# 1_5KW.net
KiCad netlist of a schematic drawn in Altium Designer
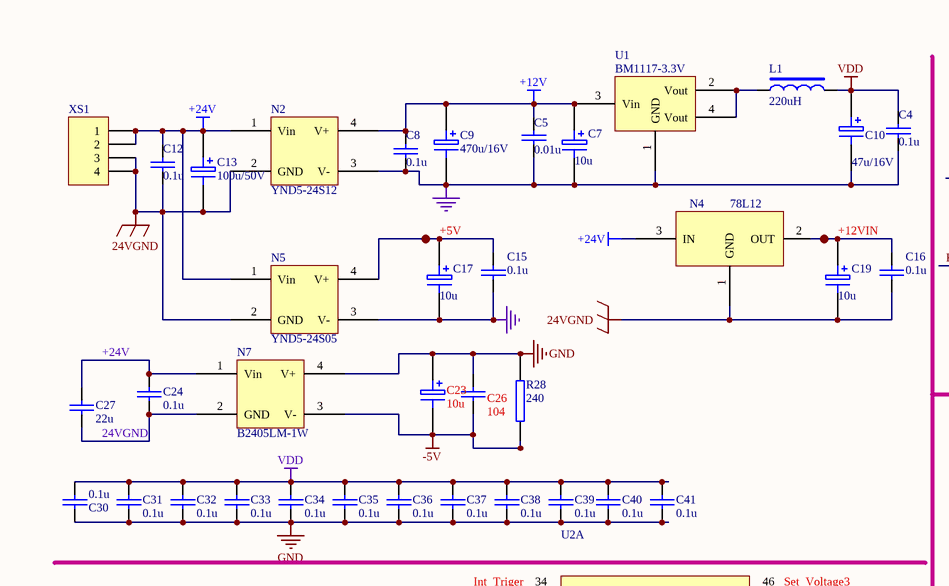
[diagram p0: 1.5KW总控制板.SchDoc, top left]
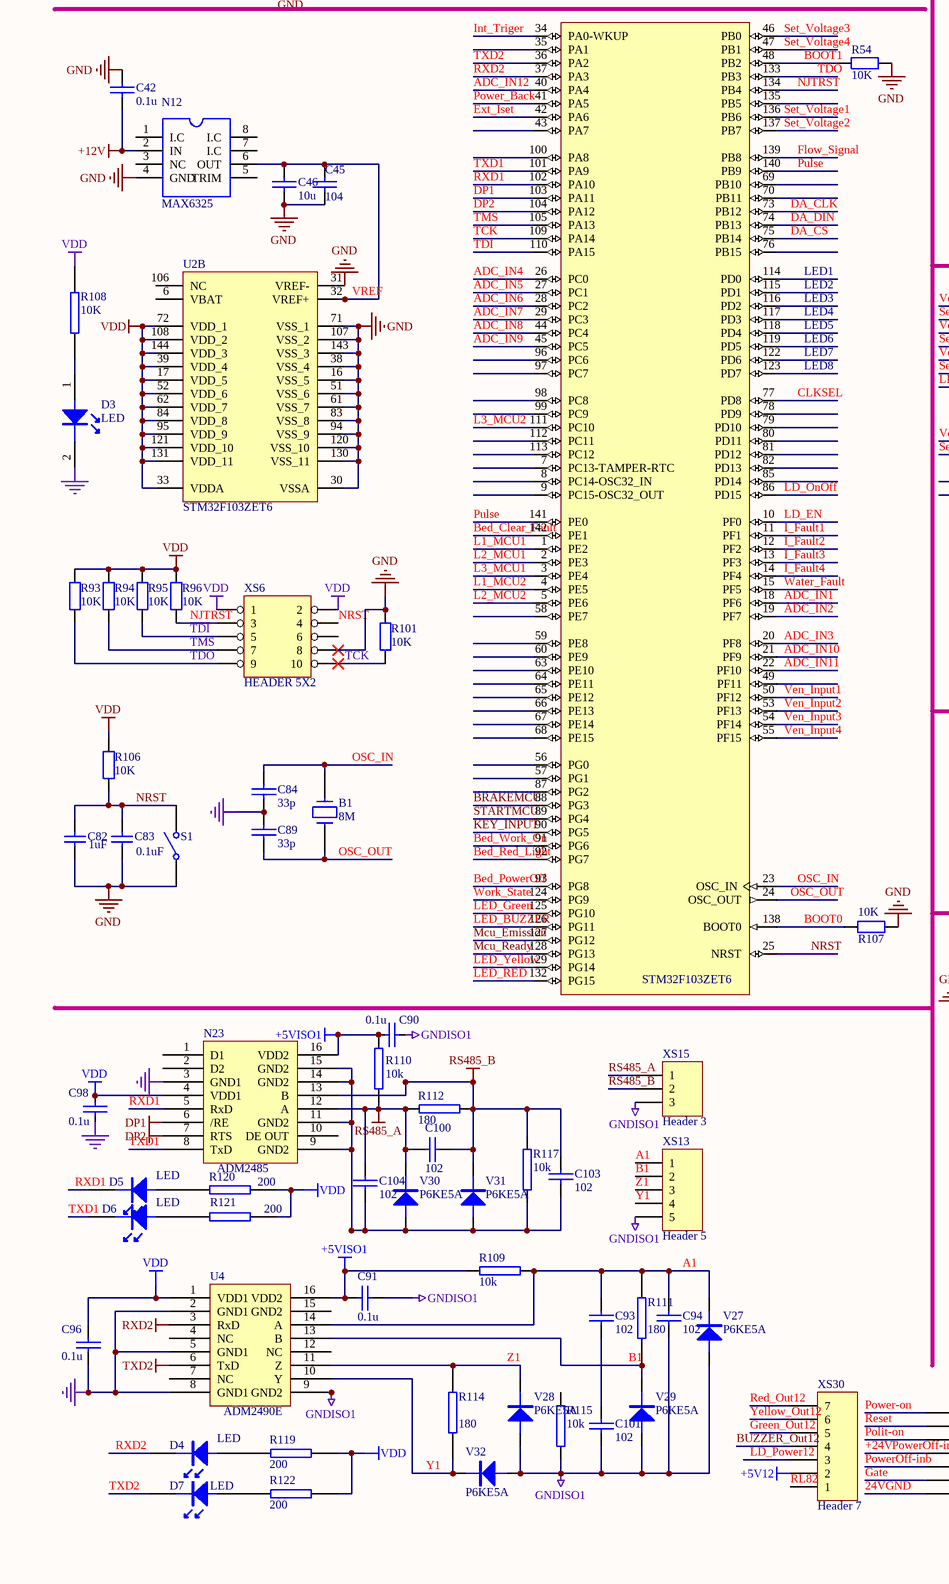
[diagram p1: 1.5KW总控制板.SchDoc, bottom left]
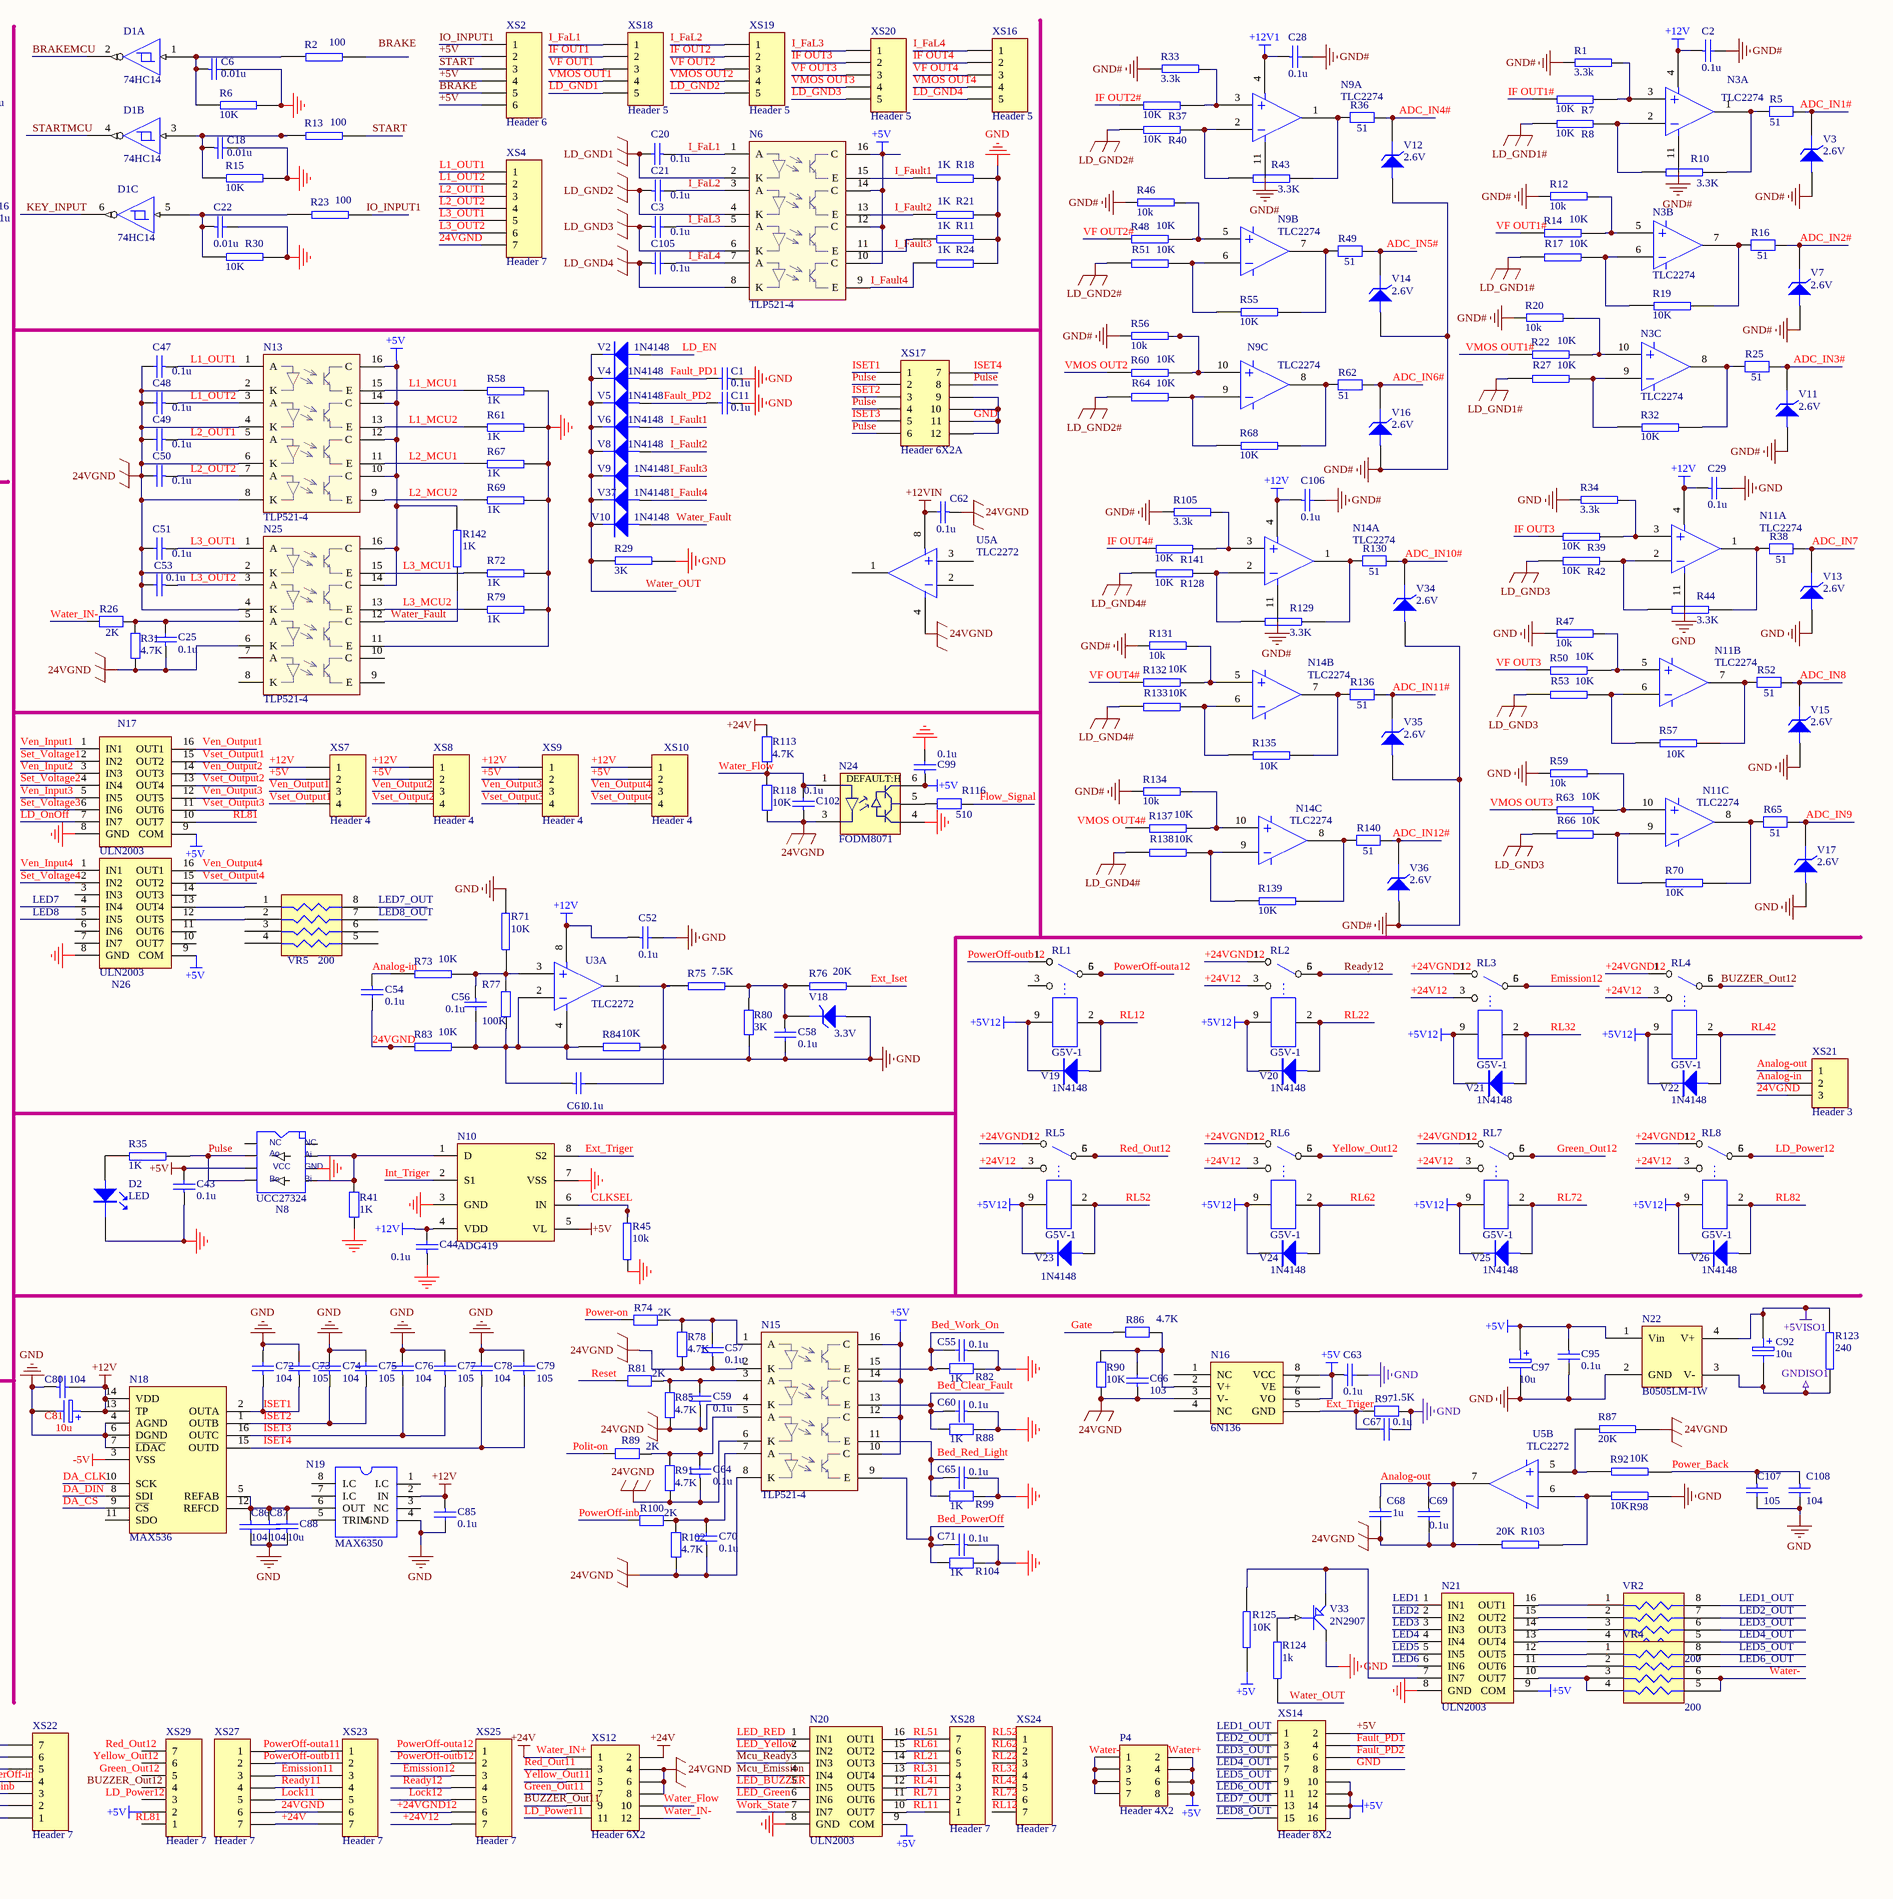
[diagram p2: 1.5KW总控制板.SchDoc, bottom right]

(export (version "E")
  (design (tool "Eeschema 10.0.6"))
  (components
    (comp (ref "B1")
      (value "8M")
      (footprint "CRY_SMB")
      (description "Crystal")
      (libsource (lib "*") (part "CRYSTAL"))
    )
    (comp (ref "C1") (value "0.1u") (footprint "0805") (libsource (lib "") (part "CAP_1")))
    (comp (ref "C2")
      (value "0.1u")
      (footprint "0805")
      (description "Capacitor")
      (libsource (lib "*") (part "CAP"))
    )
    (comp (ref "C3")
      (value "0.1u")
      (footprint "0805")
      (description "Capacitor")
      (libsource (lib "*") (part "CAP"))
    )
    (comp (ref "C4")
      (value "0.1u")
      (footprint "0805")
      (description "Capacitor")
      (libsource (lib "*") (part "CAP"))
    )
    (comp (ref "C5")
      (value "0.01u")
      (footprint "0805")
      (description "Capacitor")
      (libsource (lib "*") (part "CAP"))
    )
    (comp (ref "C6")
      (value "0.01u")
      (footprint "0805")
      (description "Capacitor")
      (libsource (lib "*") (part "CAP"))
    )
    (comp (ref "C7")
      (value "10u")
      (footprint "1206")
      (description "Electrolytic Capacitor")
      (libsource (lib "*") (part "ELECTRO1"))
    )
    (comp (ref "C8")
      (value "0.1u")
      (footprint "0805")
      (description "Capacitor")
      (libsource (lib "*") (part "CAP"))
    )
    (comp (ref "C9")
      (value "470u/16V")
      (footprint "3008")
      (description "Electrolytic Capacitor")
      (libsource (lib "*") (part "ELECTRO1"))
    )
    (comp (ref "C10")
      (value "47u/16V")
      (footprint "1206")
      (description "Electrolytic Capacitor")
      (libsource (lib "*") (part "ELECTRO1"))
    )
    (comp (ref "C11") (value "0.1u") (footprint "0805") (libsource (lib "") (part "CAP_1")))
    (comp (ref "C12")
      (value "0.1u")
      (footprint "0805")
      (description "Capacitor")
      (libsource (lib "*") (part "CAP"))
    )
    (comp (ref "C13")
      (value "100u/50V")
      (footprint "CD5-8")
      (description "Electrolytic Capacitor")
      (libsource (lib "*") (part "ELECTRO1"))
    )
    (comp (ref "C15") (value "0.1u") (footprint "0805") (libsource (lib "") (part "CAP_1")))
    (comp (ref "C16") (value "0.1u") (footprint "0805") (libsource (lib "") (part "CAP_1")))
    (comp (ref "C17")
      (value "10u")
      (footprint "1206")
      (description "Electrolytic Capacitor")
      (libsource (lib "*") (part "ELECTRO1"))
    )
    (comp (ref "C18")
      (value "0.01u")
      (footprint "0805")
      (description "Capacitor")
      (libsource (lib "*") (part "CAP"))
    )
    (comp (ref "C19")
      (value "10u")
      (footprint "1206")
      (description "Electrolytic Capacitor")
      (libsource (lib "*") (part "ELECTRO1"))
    )
    (comp (ref "C20")
      (value "0.1u")
      (footprint "0805")
      (description "Capacitor")
      (libsource (lib "*") (part "CAP"))
    )
    (comp (ref "C21")
      (value "0.1u")
      (footprint "0805")
      (description "Capacitor")
      (libsource (lib "*") (part "CAP"))
    )
    (comp (ref "C22")
      (value "0.01u")
      (footprint "0805")
      (description "Capacitor")
      (libsource (lib "*") (part "CAP"))
    )
    (comp (ref "C23")
      (value "10u")
      (footprint "1206")
      (description "Electrolytic Capacitor")
      (libsource (lib "*") (part "ELECTRO1"))
    )
    (comp (ref "C24")
      (value "0.1u")
      (footprint "0805")
      (description "Capacitor")
      (libsource (lib "*") (part "CAP"))
    )
    (comp (ref "C25") (value "0.1u") (footprint "0805") (libsource (lib "") (part "CAP_1")))
    (comp (ref "C26")
      (value "104")
      (footprint "0805")
      (description "Capacitor")
      (libsource (lib "*") (part "CAP"))
    )
    (comp (ref "C27")
      (value "22u")
      (footprint "1206")
      (description "Capacitor")
      (libsource (lib "*") (part "CAP"))
    )
    (comp (ref "C28")
      (value "0.1u")
      (footprint "0805")
      (description "Capacitor")
      (libsource (lib "*") (part "CAP"))
    )
    (comp (ref "C29")
      (value "0.1u")
      (footprint "0805")
      (description "Capacitor")
      (libsource (lib "*") (part "CAP"))
    )
    (comp (ref "C30")
      (value "0.1u")
      (footprint "0805")
      (description "Capacitor")
      (libsource (lib "*") (part "CAP"))
    )
    (comp (ref "C31")
      (value "0.1u")
      (footprint "0805")
      (description "Capacitor")
      (libsource (lib "*") (part "CAP"))
    )
    (comp (ref "C32")
      (value "0.1u")
      (footprint "0805")
      (description "Capacitor")
      (libsource (lib "*") (part "CAP"))
    )
    (comp (ref "C33")
      (value "0.1u")
      (footprint "0805")
      (description "Capacitor")
      (libsource (lib "*") (part "CAP"))
    )
    (comp (ref "C34")
      (value "0.1u")
      (footprint "0805")
      (description "Capacitor")
      (libsource (lib "*") (part "CAP"))
    )
    (comp (ref "C35")
      (value "0.1u")
      (footprint "0805")
      (description "Capacitor")
      (libsource (lib "*") (part "CAP"))
    )
    (comp (ref "C36")
      (value "0.1u")
      (footprint "0805")
      (description "Capacitor")
      (libsource (lib "*") (part "CAP"))
    )
    (comp (ref "C37")
      (value "0.1u")
      (footprint "0805")
      (description "Capacitor")
      (libsource (lib "*") (part "CAP"))
    )
    (comp (ref "C38")
      (value "0.1u")
      (footprint "0805")
      (description "Capacitor")
      (libsource (lib "*") (part "CAP"))
    )
    (comp (ref "C39")
      (value "0.1u")
      (footprint "0805")
      (description "Capacitor")
      (libsource (lib "*") (part "CAP"))
    )
    (comp (ref "C40")
      (value "0.1u")
      (footprint "0805")
      (description "Capacitor")
      (libsource (lib "*") (part "CAP"))
    )
    (comp (ref "C41")
      (value "0.1u")
      (footprint "0805")
      (description "Capacitor")
      (libsource (lib "*") (part "CAP"))
    )
    (comp (ref "C42") (value "0.1u") (footprint "0805") (libsource (lib "") (part "CAP_1")))
    (comp (ref "C43") (value "0.1u") (footprint "0805") (libsource (lib "") (part "CAP_1")))
    (comp (ref "C44") (value "0.1u") (footprint "0805") (libsource (lib "") (part "CAP_1")))
    (comp (ref "C45") (value "104") (footprint "0805") (libsource (lib "THT") (part "CAP")))
    (comp (ref "C46") (value "10u") (footprint "0805") (libsource (lib "") (part "CAP_1")))
    (comp (ref "C47")
      (value "0.1u")
      (footprint "0805")
      (description "Capacitor")
      (libsource (lib "*") (part "CAP"))
    )
    (comp (ref "C48")
      (value "0.1u")
      (footprint "0805")
      (description "Capacitor")
      (libsource (lib "*") (part "CAP"))
    )
    (comp (ref "C49")
      (value "0.1u")
      (footprint "0805")
      (description "Capacitor")
      (libsource (lib "*") (part "CAP"))
    )
    (comp (ref "C50")
      (value "0.1u")
      (footprint "0805")
      (description "Capacitor")
      (libsource (lib "*") (part "CAP"))
    )
    (comp (ref "C51")
      (value "0.1u")
      (footprint "0805")
      (description "Capacitor")
      (libsource (lib "*") (part "CAP"))
    )
    (comp (ref "C52")
      (value "0.1u")
      (footprint "0805")
      (description "Capacitor")
      (libsource (lib "*") (part "CAP"))
    )
    (comp (ref "C53")
      (value "0.1u")
      (footprint "0805")
      (description "Capacitor")
      (libsource (lib "*") (part "CAP"))
    )
    (comp (ref "C54")
      (value "0.1u")
      (footprint "0805")
      (description "Capacitor")
      (libsource (lib "*") (part "CAP"))
    )
    (comp (ref "C55") (value "0.1u") (footprint "0805") (libsource (lib "") (part "CAP_1")))
    (comp (ref "C56")
      (value "0.1u")
      (footprint "0805")
      (description "Capacitor")
      (libsource (lib "*") (part "CAP"))
    )
    (comp (ref "C57") (value "0.1u") (footprint "0805") (libsource (lib "") (part "CAP_1")))
    (comp (ref "C58")
      (value "0.1u")
      (footprint "0805")
      (description "Capacitor")
      (libsource (lib "*") (part "CAP"))
    )
    (comp (ref "C59") (value "0.1u") (footprint "0805") (libsource (lib "") (part "CAP_1")))
    (comp (ref "C60") (value "0.1u") (footprint "0805") (libsource (lib "") (part "CAP_1")))
    (comp (ref "C61")
      (value "0.1u")
      (footprint "0805")
      (description "Capacitor")
      (libsource (lib "*") (part "CAP"))
    )
    (comp (ref "C62")
      (value "0.1u")
      (footprint "0805")
      (description "Capacitor")
      (libsource (lib "*") (part "CAP"))
    )
    (comp (ref "C63")
      (value "0.1u")
      (footprint "0805")
      (description "Capacitor")
      (libsource (lib "*") (part "CAP"))
    )
    (comp (ref "C64") (value "0.1u") (footprint "0805") (libsource (lib "") (part "CAP_1")))
    (comp (ref "C65") (value "0.1u") (footprint "0805") (libsource (lib "") (part "CAP_1")))
    (comp (ref "C66") (value "103") (footprint "0805") (libsource (lib "") (part "CAP_1")))
    (comp (ref "C67") (value "0.1u") (footprint "0805") (libsource (lib "") (part "CAP_1")))
    (comp (ref "C68")
      (value "1u")
      (footprint "0805")
      (description "Capacitor")
      (libsource (lib "*") (part "CAP"))
    )
    (comp (ref "C69")
      (value "0.1u")
      (footprint "0805")
      (description "Capacitor")
      (libsource (lib "*") (part "CAP"))
    )
    (comp (ref "C70") (value "0.1u") (footprint "0805") (libsource (lib "") (part "CAP_1")))
    (comp (ref "C71") (value "0.1u") (footprint "0805") (libsource (lib "") (part "CAP_1")))
    (comp (ref "C72") (value "104") (footprint "0805") (libsource (lib "THT") (part "CAP")))
    (comp (ref "C73") (value "105") (footprint "0805") (libsource (lib "THT") (part "CAP")))
    (comp (ref "C74") (value "104") (footprint "0805") (libsource (lib "THT") (part "CAP")))
    (comp (ref "C75") (value "105") (footprint "0805") (libsource (lib "THT") (part "CAP")))
    (comp (ref "C76") (value "104") (footprint "0805") (libsource (lib "THT") (part "CAP")))
    (comp (ref "C77") (value "105") (footprint "0805") (libsource (lib "THT") (part "CAP")))
    (comp (ref "C78") (value "104") (footprint "0805") (libsource (lib "THT") (part "CAP")))
    (comp (ref "C79") (value "105") (footprint "0805") (libsource (lib "THT") (part "CAP")))
    (comp (ref "C80") (value "104") (footprint "0805") (libsource (lib "THT") (part "CAP")))
    (comp (ref "C81")
      (value "10u")
      (footprint "1206")
      (description "Electrolytic Capacitor")
      (libsource (lib "*") (part "ELECTRO1"))
    )
    (comp (ref "C82")
      (value "1uF")
      (footprint "0805")
      (description "Capacitor")
      (fields (field (name "PUBLISHER") "Altium Limited"))
      (libsource (lib "Miscellaneous Devices") (part "Cap"))
    )
    (comp (ref "C83")
      (value "0.1uF")
      (footprint "0805")
      (description "Capacitor")
      (fields (field (name "PUBLISHER") "Altium Limited"))
      (libsource (lib "Miscellaneous Devices") (part "Cap"))
    )
    (comp (ref "C84")
      (value "33p")
      (footprint "0805")
      (description "Capacitor")
      (libsource (lib "*") (part "CAP"))
    )
    (comp (ref "C85") (value "0.1u") (footprint "0805") (libsource (lib "") (part "CAP_1")))
    (comp (ref "C86") (value "104") (footprint "0805") (libsource (lib "THT") (part "CAP")))
    (comp (ref "C87") (value "104") (footprint "0805") (libsource (lib "THT") (part "CAP")))
    (comp (ref "C88") (value "10u") (footprint "0805") (libsource (lib "") (part "CAP_1")))
    (comp (ref "C89")
      (value "33p")
      (footprint "0805")
      (description "Capacitor")
      (libsource (lib "*") (part "CAP"))
    )
    (comp (ref "C90") (value "0.1u") (footprint "0805") (libsource (lib "") (part "CAP_2")))
    (comp (ref "C91")
      (value "0.1u")
      (footprint "0805")
      (description "Capacitor")
      (libsource (lib "*") (part "CAP"))
    )
    (comp (ref "C92")
      (value "10u")
      (footprint "1206")
      (description "Electrolytic Capacitor")
      (libsource (lib "*") (part "ELECTRO1"))
    )
    (comp (ref "C93")
      (value "102")
      (footprint "0805")
      (description "Capacitor")
      (libsource (lib "*") (part "CAP"))
    )
    (comp (ref "C94")
      (value "102")
      (footprint "0805")
      (description "Capacitor")
      (libsource (lib "*") (part "CAP"))
    )
    (comp (ref "C95")
      (value "0.1u")
      (footprint "0805")
      (description "Capacitor")
      (libsource (lib "*") (part "CAP"))
    )
    (comp (ref "C96")
      (value "0.1u")
      (footprint "0805")
      (description "Capacitor")
      (libsource (lib "*") (part "CAP"))
    )
    (comp (ref "C97")
      (value "10u")
      (footprint "1206")
      (description "Electrolytic Capacitor")
      (libsource (lib "*") (part "ELECTRO1"))
    )
    (comp (ref "C98") (value "0.1u") (footprint "0805") (libsource (lib "") (part "CAP_2")))
    (comp (ref "C99") (value "0.1u") (footprint "0805") (libsource (lib "") (part "CAP_1")))
    (comp (ref "C100")
      (value "102")
      (footprint "0805")
      (description "Capacitor")
      (libsource (lib "*") (part "CAP"))
    )
    (comp (ref "C101")
      (value "102")
      (footprint "0805")
      (description "Capacitor")
      (libsource (lib "*") (part "CAP"))
    )
    (comp (ref "C102") (value "0.1u") (footprint "0805") (libsource (lib "") (part "CAP_1")))
    (comp (ref "C103")
      (value "102")
      (footprint "0805")
      (description "Capacitor")
      (libsource (lib "*") (part "CAP"))
    )
    (comp (ref "C104")
      (value "102")
      (footprint "0805")
      (description "Capacitor")
      (libsource (lib "*") (part "CAP"))
    )
    (comp (ref "C105")
      (value "0.1u")
      (footprint "0805")
      (description "Capacitor")
      (libsource (lib "*") (part "CAP"))
    )
    (comp (ref "C106")
      (value "0.1u")
      (footprint "0805")
      (description "Capacitor")
      (libsource (lib "*") (part "CAP"))
    )
    (comp (ref "C107") (value "105") (footprint "0805") (libsource (lib "THT") (part "CAP")))
    (comp (ref "C108") (value "104") (footprint "0805") (libsource (lib "THT") (part "CAP")))
    (comp (ref "D1") (value "74HC14") (footprint "SO-14") (libsource (lib "*") (part "4584")))
    (comp (ref "D2") (value "LED") (footprint "1206A") (libsource (lib "*") (part "LED")))
    (comp (ref "D3") (value "LED") (footprint "1206A") (libsource (lib "") (part "LED_1")))
    (comp (ref "D4") (value "LED") (footprint "1206A") (libsource (lib "*") (part "LED")))
    (comp (ref "D5") (value "LED") (footprint "1206A") (libsource (lib "*") (part "LED")))
    (comp (ref "D6") (value "LED") (footprint "1206A") (libsource (lib "*") (part "LED")))
    (comp (ref "D7") (value "LED") (footprint "1206A") (libsource (lib "*") (part "LED")))
    (comp (ref "L1") (value "220uH") (footprint "1812") (libsource (lib "*") (part "L")))
    (comp (ref "N2") (value "YND5-24S12") (footprint "YND5") (libsource (lib "*") (part "B0505LM")))
    (comp (ref "N3") (value "TLC2274") (footprint "SO-14") (libsource (lib "*") (part "LM124")))
    (comp (ref "N4") (value "78L12") (footprint "TO-92_2") (libsource (lib "*") (part "VOL")))
    (comp (ref "N5") (value "YND5-24S05") (footprint "YND5") (libsource (lib "*") (part "B0505LM")))
    (comp (ref "N6")
      (value "TLP521-4")
      (footprint "ILEAD-16")
      (libsource (lib "work_ruilei") (part "TLP521-4"))
    )
    (comp (ref "N7") (value "B2405LM-1W") (footprint "B0505LM") (libsource (lib "*") (part "B0505LM")))
    (comp (ref "N8") (value "UCC27324") (footprint "SO-8") (libsource (lib "框图2") (part "UCC27324")))
    (comp (ref "N9") (value "TLC2274") (footprint "SO-14") (libsource (lib "*") (part "LM124")))
    (comp (ref "N10") (value "ADG419") (footprint "SO-8") (libsource (lib "40hz") (part "ADG419")))
    (comp (ref "N11") (value "TLC2274") (footprint "SO-14") (libsource (lib "*") (part "LM124")))
    (comp (ref "N12") (value "MAX6325") (footprint "SO-8") (libsource (lib "") (part "MAX6341_1")))
    (comp (ref "N13")
      (value "TLP521-4")
      (footprint "ILEAD-16")
      (libsource (lib "work_ruilei") (part "TLP521-4"))
    )
    (comp (ref "N14") (value "TLC2274") (footprint "SO-14") (libsource (lib "*") (part "LM124")))
    (comp (ref "N15")
      (value "TLP521-4")
      (footprint "ILEAD-16")
      (libsource (lib "work_ruilei") (part "TLP521-4"))
    )
    (comp (ref "N16") (value "6N136") (footprint "ILEAD-8") (libsource (lib "*") (part "HCPL2601")))
    (comp (ref "N17")
      (value "ULN2003")
      (footprint "SOIC127P600-16N")
      (libsource (lib "work_ruilei") (part "ULN2003A"))
    )
    (comp (ref "N18") (value "MAX536") (footprint "SOIC-16") (libsource (lib "work_ruilei") (part "MAX536")))
    (comp (ref "N19") (value "MAX6350") (footprint "SO-8") (libsource (lib "TH2") (part "MAX6341")))
    (comp (ref "N20")
      (value "ULN2003")
      (footprint "SOIC127P600-16N")
      (libsource (lib "work_ruilei") (part "ULN2003A"))
    )
    (comp (ref "N21")
      (value "ULN2003")
      (footprint "SOIC127P600-16N")
      (libsource (lib "work_ruilei") (part "ULN2003A"))
    )
    (comp (ref "N22") (value "B0505LM-1W") (footprint "B0505LM") (libsource (lib "*") (part "B0505LM")))
    (comp (ref "N23") (value "ADM2485") (footprint "SOIC-16") (libsource (lib "C8051F021") (part "ADM2485")))
    (comp (ref "N24") (value "FODM8071") (footprint "SO-8") (libsource (lib "work_ruilei") (part "FODM8071")))
    (comp (ref "N25")
      (value "TLP521-4")
      (footprint "ILEAD-16")
      (libsource (lib "work_ruilei") (part "TLP521-4"))
    )
    (comp (ref "N26")
      (value "ULN2003")
      (footprint "SOIC127P600-16N")
      (libsource (lib "work_ruilei") (part "ULN2003A"))
    )
    (comp (ref "P4")
      (value "Header 4X2")
      (footprint "HDR2X4")
      (description "Header, 4-Pin, Dual row")
      (fields (field (name "PUBLISHER") "Altium Limited"))
      (libsource (lib "Miscellaneous Connectors") (part "Header 4X2"))
    )
    (comp (ref "R1") (value "3.3k") (footprint "0805") (libsource (lib "") (part "R_1")))
    (comp (ref "R2") (value "100") (footprint "0805") (libsource (lib "*") (part "RES2")))
    (comp (ref "R5")
      (value "51")
      (footprint "0805")
      (description "Resistor")
      (fields (field (name "PUBLISHER") "Altium Limited"))
      (libsource (lib "Miscellaneous Devices") (part "Res2"))
    )
    (comp (ref "R6") (value "10K") (footprint "0805") (libsource (lib "*") (part "RES2")))
    (comp (ref "R7") (value "10K") (footprint "0805") (libsource (lib "*") (part "RES2")))
    (comp (ref "R8") (value "10K") (footprint "0805") (libsource (lib "*") (part "RES2")))
    (comp (ref "R10") (value "3.3K") (footprint "0805") (libsource (lib "*") (part "RES2")))
    (comp (ref "R11") (value "1K") (footprint "0805") (libsource (lib "*") (part "RES2")))
    (comp (ref "R12") (value "10k") (footprint "0805") (libsource (lib "") (part "R_1")))
    (comp (ref "R13") (value "100") (footprint "0805") (libsource (lib "*") (part "RES2")))
    (comp (ref "R14") (value "10K") (footprint "0805") (libsource (lib "*") (part "RES2")))
    (comp (ref "R15") (value "10K") (footprint "0805") (libsource (lib "*") (part "RES2")))
    (comp (ref "R16")
      (value "51")
      (footprint "0805")
      (description "Resistor")
      (fields (field (name "PUBLISHER") "Altium Limited"))
      (libsource (lib "Miscellaneous Devices") (part "Res2"))
    )
    (comp (ref "R17") (value "10K") (footprint "0805") (libsource (lib "*") (part "RES2")))
    (comp (ref "R18") (value "1K") (footprint "0805") (libsource (lib "*") (part "RES2")))
    (comp (ref "R19") (value "10K") (footprint "0805") (libsource (lib "*") (part "RES2")))
    (comp (ref "R20") (value "10k") (footprint "0805") (libsource (lib "") (part "R_1")))
    (comp (ref "R21") (value "1K") (footprint "0805") (libsource (lib "*") (part "RES2")))
    (comp (ref "R22") (value "10K") (footprint "0805") (libsource (lib "*") (part "RES2")))
    (comp (ref "R23") (value "100") (footprint "0805") (libsource (lib "*") (part "RES2")))
    (comp (ref "R24") (value "1K") (footprint "0805") (libsource (lib "*") (part "RES2")))
    (comp (ref "R25")
      (value "51")
      (footprint "0805")
      (description "Resistor")
      (fields (field (name "PUBLISHER") "Altium Limited"))
      (libsource (lib "Miscellaneous Devices") (part "Res2"))
    )
    (comp (ref "R26")
      (value "2K")
      (footprint "0805")
      (description "Resistor")
      (fields (field (name "PUBLISHER") "Altium Limited"))
      (libsource (lib "Miscellaneous Devices") (part "Res2"))
    )
    (comp (ref "R27") (value "10K") (footprint "0805") (libsource (lib "*") (part "RES2")))
    (comp (ref "R28") (value "240") (footprint "1206") (libsource (lib "*") (part "RES2")))
    (comp (ref "R29") (value "3K") (footprint "0805") (libsource (lib "*") (part "RES2")))
    (comp (ref "R30") (value "10K") (footprint "0805") (libsource (lib "*") (part "RES2")))
    (comp (ref "R31")
      (value "4.7K")
      (footprint "0805")
      (description "Resistor")
      (fields (field (name "PUBLISHER") "Altium Limited"))
      (libsource (lib "") (part "Res2_2"))
    )
    (comp (ref "R32") (value "10K") (footprint "0805") (libsource (lib "*") (part "RES2")))
    (comp (ref "R33") (value "3.3k") (footprint "0805") (libsource (lib "") (part "R_1")))
    (comp (ref "R34") (value "3.3k") (footprint "0805") (libsource (lib "") (part "R_1")))
    (comp (ref "R35") (value "1K") (footprint "0805") (libsource (lib "*") (part "RES2")))
    (comp (ref "R36")
      (value "51")
      (footprint "0805")
      (description "Resistor")
      (fields (field (name "PUBLISHER") "Altium Limited"))
      (libsource (lib "Miscellaneous Devices") (part "Res2"))
    )
    (comp (ref "R37") (value "10K") (footprint "0805") (libsource (lib "*") (part "RES2")))
    (comp (ref "R38")
      (value "51")
      (footprint "0805")
      (description "Resistor")
      (fields (field (name "PUBLISHER") "Altium Limited"))
      (libsource (lib "Miscellaneous Devices") (part "Res2"))
    )
    (comp (ref "R39") (value "10K") (footprint "0805") (libsource (lib "*") (part "RES2")))
    (comp (ref "R40") (value "10K") (footprint "0805") (libsource (lib "*") (part "RES2")))
    (comp (ref "R41")
      (value "1K")
      (footprint "0805")
      (description "Resistor")
      (fields (field (name "PUBLISHER") "Altium Limited"))
      (libsource (lib "") (part "Res2_2"))
    )
    (comp (ref "R42") (value "10K") (footprint "0805") (libsource (lib "*") (part "RES2")))
    (comp (ref "R43") (value "3.3K") (footprint "0805") (libsource (lib "*") (part "RES2")))
    (comp (ref "R44") (value "3.3K") (footprint "0805") (libsource (lib "*") (part "RES2")))
    (comp (ref "R45") (value "10k") (footprint "0805") (libsource (lib "*") (part "R")))
    (comp (ref "R46") (value "10k") (footprint "0805") (libsource (lib "") (part "R_1")))
    (comp (ref "R47") (value "10k") (footprint "0805") (libsource (lib "") (part "R_1")))
    (comp (ref "R48") (value "10K") (footprint "0805") (libsource (lib "*") (part "RES2")))
    (comp (ref "R49")
      (value "51")
      (footprint "0805")
      (description "Resistor")
      (fields (field (name "PUBLISHER") "Altium Limited"))
      (libsource (lib "Miscellaneous Devices") (part "Res2"))
    )
    (comp (ref "R50") (value "10K") (footprint "0805") (libsource (lib "*") (part "RES2")))
    (comp (ref "R51") (value "10K") (footprint "0805") (libsource (lib "*") (part "RES2")))
    (comp (ref "R52")
      (value "51")
      (footprint "0805")
      (description "Resistor")
      (fields (field (name "PUBLISHER") "Altium Limited"))
      (libsource (lib "Miscellaneous Devices") (part "Res2"))
    )
    (comp (ref "R53") (value "10K") (footprint "0805") (libsource (lib "*") (part "RES2")))
    (comp (ref "R54")
      (value "10K")
      (footprint "0805")
      (description "Resistor")
      (fields (field (name "PUBLISHER") "Altium Limited"))
      (libsource (lib "Miscellaneous Devices") (part "Res2"))
    )
    (comp (ref "R55") (value "10K") (footprint "0805") (libsource (lib "*") (part "RES2")))
    (comp (ref "R56") (value "10k") (footprint "0805") (libsource (lib "") (part "R_1")))
    (comp (ref "R57") (value "10K") (footprint "0805") (libsource (lib "*") (part "RES2")))
    (comp (ref "R58") (value "1K") (footprint "0805") (libsource (lib "*") (part "RES2")))
    (comp (ref "R59") (value "10k") (footprint "0805") (libsource (lib "") (part "R_1")))
    (comp (ref "R60") (value "10K") (footprint "0805") (libsource (lib "*") (part "RES2")))
    (comp (ref "R61") (value "1K") (footprint "0805") (libsource (lib "*") (part "RES2")))
    (comp (ref "R62")
      (value "51")
      (footprint "0805")
      (description "Resistor")
      (fields (field (name "PUBLISHER") "Altium Limited"))
      (libsource (lib "Miscellaneous Devices") (part "Res2"))
    )
    (comp (ref "R63") (value "10K") (footprint "0805") (libsource (lib "*") (part "RES2")))
    (comp (ref "R64") (value "10K") (footprint "0805") (libsource (lib "*") (part "RES2")))
    (comp (ref "R65")
      (value "51")
      (footprint "0805")
      (description "Resistor")
      (fields (field (name "PUBLISHER") "Altium Limited"))
      (libsource (lib "Miscellaneous Devices") (part "Res2"))
    )
    (comp (ref "R66") (value "10K") (footprint "0805") (libsource (lib "*") (part "RES2")))
    (comp (ref "R67") (value "1K") (footprint "0805") (libsource (lib "*") (part "RES2")))
    (comp (ref "R68") (value "10K") (footprint "0805") (libsource (lib "*") (part "RES2")))
    (comp (ref "R69") (value "1K") (footprint "0805") (libsource (lib "*") (part "RES2")))
    (comp (ref "R70") (value "10K") (footprint "0805") (libsource (lib "*") (part "RES2")))
    (comp (ref "R71") (value "10K") (footprint "0805") (libsource (lib "*") (part "RES2")))
    (comp (ref "R72") (value "1K") (footprint "0805") (libsource (lib "*") (part "RES2")))
    (comp (ref "R73") (value "10K") (footprint "0805") (libsource (lib "*") (part "RES2")))
    (comp (ref "R74")
      (value "2K")
      (footprint "0805")
      (description "Resistor")
      (fields (field (name "PUBLISHER") "Altium Limited"))
      (libsource (lib "Miscellaneous Devices") (part "Res2"))
    )
    (comp (ref "R75") (value "7.5K") (footprint "0805") (libsource (lib "*") (part "RES2")))
    (comp (ref "R76") (value "20K") (footprint "0805") (libsource (lib "*") (part "RES2")))
    (comp (ref "R77")
      (value "100K")
      (footprint "0805")
      (description "Resistor")
      (fields (field (name "PUBLISHER") "Altium Limited"))
      (libsource (lib "") (part "Res2_4"))
    )
    (comp (ref "R78")
      (value "4.7K")
      (footprint "0805")
      (description "Resistor")
      (fields (field (name "PUBLISHER") "Altium Limited"))
      (libsource (lib "") (part "Res2_2"))
    )
    (comp (ref "R79") (value "1K") (footprint "0805") (libsource (lib "*") (part "RES2")))
    (comp (ref "R80")
      (value "3K")
      (footprint "0805")
      (description "Resistor")
      (fields (field (name "PUBLISHER") "Altium Limited"))
      (libsource (lib "") (part "Res2_2"))
    )
    (comp (ref "R81")
      (value "2K")
      (footprint "0805")
      (description "Resistor")
      (fields (field (name "PUBLISHER") "Altium Limited"))
      (libsource (lib "Miscellaneous Devices") (part "Res2"))
    )
    (comp (ref "R82")
      (value "1K")
      (footprint "0805")
      (description "Resistor")
      (fields (field (name "PUBLISHER") "Altium Limited"))
      (libsource (lib "") (part "Res2_1"))
    )
    (comp (ref "R83") (value "10K") (footprint "0805") (libsource (lib "*") (part "RES2")))
    (comp (ref "R84") (value "10K") (footprint "0805") (libsource (lib "*") (part "RES2")))
    (comp (ref "R85")
      (value "4.7K")
      (footprint "0805")
      (description "Resistor")
      (fields (field (name "PUBLISHER") "Altium Limited"))
      (libsource (lib "") (part "Res2_2"))
    )
    (comp (ref "R86")
      (value "4.7K")
      (footprint "1206")
      (description "Resistor")
      (fields (field (name "PUBLISHER") "Altium Limited"))
      (libsource (lib "Miscellaneous Devices") (part "Res2"))
    )
    (comp (ref "R87") (value "20K") (footprint "0805") (libsource (lib "") (part "RES2_1")))
    (comp (ref "R88")
      (value "1K")
      (footprint "0805")
      (description "Resistor")
      (fields (field (name "PUBLISHER") "Altium Limited"))
      (libsource (lib "") (part "Res2_1"))
    )
    (comp (ref "R89")
      (value "2K")
      (footprint "0805")
      (description "Resistor")
      (fields (field (name "PUBLISHER") "Altium Limited"))
      (libsource (lib "Miscellaneous Devices") (part "Res2"))
    )
    (comp (ref "R90")
      (value "10K")
      (footprint "0805")
      (description "Resistor")
      (fields (field (name "PUBLISHER") "Altium Limited"))
      (libsource (lib "") (part "Res2_2"))
    )
    (comp (ref "R91")
      (value "4.7K")
      (footprint "0805")
      (description "Resistor")
      (fields (field (name "PUBLISHER") "Altium Limited"))
      (libsource (lib "") (part "Res2_2"))
    )
    (comp (ref "R92") (value "10K") (footprint "0805") (libsource (lib "*") (part "RES2")))
    (comp (ref "R93")
      (value "10K")
      (footprint "0805")
      (description "Resistor")
      (fields (field (name "PUBLISHER") "Altium Limited"))
      (libsource (lib "") (part "Res2_2"))
    )
    (comp (ref "R94")
      (value "10K")
      (footprint "0805")
      (description "Resistor")
      (fields (field (name "PUBLISHER") "Altium Limited"))
      (libsource (lib "") (part "Res2_2"))
    )
    (comp (ref "R95")
      (value "10K")
      (footprint "0805")
      (description "Resistor")
      (fields (field (name "PUBLISHER") "Altium Limited"))
      (libsource (lib "") (part "Res2_2"))
    )
    (comp (ref "R96")
      (value "10K")
      (footprint "0805")
      (description "Resistor")
      (fields (field (name "PUBLISHER") "Altium Limited"))
      (libsource (lib "") (part "Res2_2"))
    )
    (comp (ref "R97")
      (value "1.5K")
      (footprint "0805")
      (description "Resistor")
      (fields (field (name "PUBLISHER") "Altium Limited"))
      (libsource (lib "") (part "Res2_1"))
    )
    (comp (ref "R98") (value "10K") (footprint "0805") (libsource (lib "*") (part "RES2")))
    (comp (ref "R99")
      (value "1K")
      (footprint "0805")
      (description "Resistor")
      (fields (field (name "PUBLISHER") "Altium Limited"))
      (libsource (lib "") (part "Res2_1"))
    )
    (comp (ref "R100")
      (value "2K")
      (footprint "0805")
      (description "Resistor")
      (fields (field (name "PUBLISHER") "Altium Limited"))
      (libsource (lib "Miscellaneous Devices") (part "Res2"))
    )
    (comp (ref "R101")
      (value "10K")
      (footprint "0805")
      (description "Resistor")
      (fields (field (name "PUBLISHER") "Altium Limited"))
      (libsource (lib "") (part "Res2_2"))
    )
    (comp (ref "R102")
      (value "4.7K")
      (footprint "0805")
      (description "Resistor")
      (fields (field (name "PUBLISHER") "Altium Limited"))
      (libsource (lib "") (part "Res2_2"))
    )
    (comp (ref "R103") (value "20K") (footprint "0805") (libsource (lib "*") (part "RES2")))
    (comp (ref "R104")
      (value "1K")
      (footprint "0805")
      (description "Resistor")
      (fields (field (name "PUBLISHER") "Altium Limited"))
      (libsource (lib "") (part "Res2_1"))
    )
    (comp (ref "R105") (value "3.3k") (footprint "0805") (libsource (lib "") (part "R_1")))
    (comp (ref "R106")
      (value "10K")
      (footprint "0805")
      (description "Resistor")
      (fields (field (name "Comment") "Res2") (field (name "PUBLISHER") "Altium Limited"))
      (libsource (lib "") (part "Res2_4"))
    )
    (comp (ref "R107")
      (value "10K")
      (footprint "0805")
      (description "Resistor")
      (fields (field (name "PUBLISHER") "Altium Limited"))
      (libsource (lib "Miscellaneous Devices") (part "Res2"))
    )
    (comp (ref "R108") (value "10K") (footprint "0805") (libsource (lib "*") (part "RES2")))
    (comp (ref "R109") (value "10k") (footprint "0805") (libsource (lib "*") (part "R")))
    (comp (ref "R110") (value "10k") (footprint "0805") (libsource (lib "*") (part "R")))
    (comp (ref "R111") (value "180") (footprint "1206") (libsource (lib "*") (part "RES2")))
    (comp (ref "R112") (value "180") (footprint "1206") (libsource (lib "") (part "RES2_2")))
    (comp (ref "R113")
      (value "4.7K")
      (footprint "0805")
      (description "Resistor")
      (fields (field (name "PUBLISHER") "Altium Limited"))
      (libsource (lib "") (part "Res2_3"))
    )
    (comp (ref "R114") (value "180") (footprint "1206") (libsource (lib "*") (part "RES2")))
    (comp (ref "R115") (value "10k") (footprint "0805") (libsource (lib "*") (part "R")))
    (comp (ref "R116")
      (value "510")
      (footprint "0805")
      (description "Resistor")
      (fields (field (name "PUBLISHER") "Altium Limited"))
      (libsource (lib "Miscellaneous Devices") (part "Res2"))
    )
    (comp (ref "R117") (value "10k") (footprint "0805") (libsource (lib "*") (part "R")))
    (comp (ref "R118")
      (value "10K")
      (footprint "0805")
      (description "Resistor")
      (fields (field (name "PUBLISHER") "Altium Limited"))
      (libsource (lib "") (part "Res2_2"))
    )
    (comp (ref "R119") (value "200") (footprint "0805") (libsource (lib "*") (part "RES2")))
    (comp (ref "R120") (value "200") (footprint "0805") (libsource (lib "*") (part "RES2")))
    (comp (ref "R121") (value "200") (footprint "0805") (libsource (lib "*") (part "RES2")))
    (comp (ref "R122") (value "200") (footprint "0805") (libsource (lib "*") (part "RES2")))
    (comp (ref "R123") (value "240") (footprint "1206") (libsource (lib "*") (part "RES2")))
    (comp (ref "R124") (value "1k") (footprint "1206") (libsource (lib "*") (part "RES2")))
    (comp (ref "R125") (value "10K") (footprint "0805") (libsource (lib "") (part "RES2_1")))
    (comp (ref "R128") (value "10K") (footprint "0805") (libsource (lib "*") (part "RES2")))
    (comp (ref "R129") (value "3.3K") (footprint "0805") (libsource (lib "*") (part "RES2")))
    (comp (ref "R130")
      (value "51")
      (footprint "0805")
      (description "Resistor")
      (fields (field (name "PUBLISHER") "Altium Limited"))
      (libsource (lib "Miscellaneous Devices") (part "Res2"))
    )
    (comp (ref "R131") (value "10k") (footprint "0805") (libsource (lib "") (part "R_1")))
    (comp (ref "R132") (value "10K") (footprint "0805") (libsource (lib "*") (part "RES2")))
    (comp (ref "R133") (value "10K") (footprint "0805") (libsource (lib "*") (part "RES2")))
    (comp (ref "R134") (value "10k") (footprint "0805") (libsource (lib "") (part "R_1")))
    (comp (ref "R135") (value "10K") (footprint "0805") (libsource (lib "*") (part "RES2")))
    (comp (ref "R136")
      (value "51")
      (footprint "0805")
      (description "Resistor")
      (fields (field (name "PUBLISHER") "Altium Limited"))
      (libsource (lib "Miscellaneous Devices") (part "Res2"))
    )
    (comp (ref "R137") (value "10K") (footprint "0805") (libsource (lib "*") (part "RES2")))
    (comp (ref "R138") (value "10K") (footprint "0805") (libsource (lib "*") (part "RES2")))
    (comp (ref "R139") (value "10K") (footprint "0805") (libsource (lib "*") (part "RES2")))
    (comp (ref "R140")
      (value "51")
      (footprint "0805")
      (description "Resistor")
      (fields (field (name "PUBLISHER") "Altium Limited"))
      (libsource (lib "Miscellaneous Devices") (part "Res2"))
    )
    (comp (ref "R141") (value "10K") (footprint "0805") (libsource (lib "*") (part "RES2")))
    (comp (ref "R142") (value "1K") (footprint "0805") (libsource (lib "") (part "RES2_1")))
    (comp (ref "RL1") (value "G5V-1") (footprint "G5V-1") (libsource (lib "work_ruilei") (part "G5V-1")))
    (comp (ref "RL2") (value "G5V-1") (footprint "G5V-1") (libsource (lib "work_ruilei") (part "G5V-1")))
    (comp (ref "RL3") (value "G5V-1") (footprint "G5V-1") (libsource (lib "work_ruilei") (part "G5V-1")))
    (comp (ref "RL4") (value "G5V-1") (footprint "G5V-1") (libsource (lib "work_ruilei") (part "G5V-1")))
    (comp (ref "RL5") (value "G5V-1") (footprint "G5V-1") (libsource (lib "work_ruilei") (part "G5V-1")))
    (comp (ref "RL6") (value "G5V-1") (footprint "G5V-1") (libsource (lib "work_ruilei") (part "G5V-1")))
    (comp (ref "RL7") (value "G5V-1") (footprint "G5V-1") (libsource (lib "work_ruilei") (part "G5V-1")))
    (comp (ref "RL8") (value "G5V-1") (footprint "G5V-1") (libsource (lib "work_ruilei") (part "G5V-1")))
    (comp (ref "S1")
      (value "SW-SPST")
      (footprint "KEY_3*6*2.5")
      (description "Single-Pole, Single-Throw Switch")
      (fields (field (name "PUBLISHER") "Altium Limited"))
      (libsource (lib "Miscellaneous Devices") (part "SW-SPST"))
    )
    (comp (ref "U1") (value "BM1117-3.3V") (footprint "SOT-223") (libsource (lib "*") (part "BM1117")))
    (comp (ref "U2")
      (value "STM32F103ZET6")
      (footprint "LQFP144_N")
      (libsource (lib "STMicroelectronics STM32 F1") (part "STM32F103ZET6"))
    )
    (comp (ref "U3") (value "TLC2272") (footprint "SO-8") (libsource (lib "*") (part "1458")))
    (comp (ref "U4") (value "ADM2490E") (footprint "SOIC-16") (libsource (lib "*") (part "ADM2490E")))
    (comp (ref "U5") (value "TLC2272") (footprint "SO-8") (libsource (lib "*") (part "1458")))
    (comp (ref "V2") (value "1N4148") (footprint "1206A") (libsource (lib "*") (part "D")))
    (comp (ref "V3")
      (value "2.6V")
      (footprint "1206A")
      (description "Zener Diode")
      (libsource (lib "*") (part "ZENER3"))
    )
    (comp (ref "V4") (value "1N4148") (footprint "1206A") (libsource (lib "*") (part "D")))
    (comp (ref "V5") (value "1N4148") (footprint "1206A") (libsource (lib "*") (part "D")))
    (comp (ref "V6") (value "1N4148") (footprint "1206A") (libsource (lib "*") (part "D")))
    (comp (ref "V7")
      (value "2.6V")
      (footprint "1206A")
      (description "Zener Diode")
      (libsource (lib "*") (part "ZENER3"))
    )
    (comp (ref "V8") (value "1N4148") (footprint "1206A") (libsource (lib "*") (part "D")))
    (comp (ref "V9") (value "1N4148") (footprint "1206A") (libsource (lib "*") (part "D")))
    (comp (ref "V10") (value "1N4148") (footprint "1206A") (libsource (lib "*") (part "D")))
    (comp (ref "V11")
      (value "2.6V")
      (footprint "1206A")
      (description "Zener Diode")
      (libsource (lib "*") (part "ZENER3"))
    )
    (comp (ref "V12")
      (value "2.6V")
      (footprint "1206A")
      (description "Zener Diode")
      (libsource (lib "*") (part "ZENER3"))
    )
    (comp (ref "V13")
      (value "2.6V")
      (footprint "1206A")
      (description "Zener Diode")
      (libsource (lib "*") (part "ZENER3"))
    )
    (comp (ref "V14")
      (value "2.6V")
      (footprint "1206A")
      (description "Zener Diode")
      (libsource (lib "*") (part "ZENER3"))
    )
    (comp (ref "V15")
      (value "2.6V")
      (footprint "1206A")
      (description "Zener Diode")
      (libsource (lib "*") (part "ZENER3"))
    )
    (comp (ref "V16")
      (value "2.6V")
      (footprint "1206A")
      (description "Zener Diode")
      (libsource (lib "*") (part "ZENER3"))
    )
    (comp (ref "V17")
      (value "2.6V")
      (footprint "1206A")
      (description "Zener Diode")
      (libsource (lib "*") (part "ZENER3"))
    )
    (comp (ref "V18")
      (value "3.3V")
      (footprint "1206A")
      (description "Zener Diode")
      (libsource (lib "*") (part "ZENER3"))
    )
    (comp (ref "V19") (value "1N4148") (footprint "1206A") (libsource (lib "") (part "D_1")))
    (comp (ref "V20") (value "1N4148") (footprint "1206A") (libsource (lib "") (part "D_1")))
    (comp (ref "V21") (value "1N4148") (footprint "1206A") (libsource (lib "") (part "D_1")))
    (comp (ref "V22") (value "1N4148") (footprint "1206A") (libsource (lib "") (part "D_1")))
    (comp (ref "V23") (value "1N4148") (footprint "1206A") (libsource (lib "") (part "D_1")))
    (comp (ref "V24") (value "1N4148") (footprint "1206A") (libsource (lib "") (part "D_1")))
    (comp (ref "V25") (value "1N4148") (footprint "1206A") (libsource (lib "") (part "D_1")))
    (comp (ref "V26") (value "1N4148") (footprint "1206A") (libsource (lib "") (part "D_1")))
    (comp (ref "V27") (value "P6KE5A") (footprint "1206-D") (libsource (lib "*") (part "DIODE")))
    (comp (ref "V28") (value "P6KE5A") (footprint "1206-D") (libsource (lib "*") (part "DIODE")))
    (comp (ref "V29") (value "P6KE5A") (footprint "1206-D") (libsource (lib "*") (part "DIODE")))
    (comp (ref "V30") (value "P6KE5A") (footprint "1206-D") (libsource (lib "*") (part "DIODE")))
    (comp (ref "V31") (value "P6KE5A") (footprint "1206-D") (libsource (lib "*") (part "DIODE")))
    (comp (ref "V32") (value "P6KE5A") (footprint "1206-D") (libsource (lib "*") (part "DIODE")))
    (comp (ref "V33") (value "2N2907") (footprint "SOT-23") (libsource (lib "TH1") (part "PNP2")))
    (comp (ref "V34")
      (value "2.6V")
      (footprint "1206A")
      (description "Zener Diode")
      (libsource (lib "*") (part "ZENER3"))
    )
    (comp (ref "V35")
      (value "2.6V")
      (footprint "1206A")
      (description "Zener Diode")
      (libsource (lib "*") (part "ZENER3"))
    )
    (comp (ref "V36")
      (value "2.6V")
      (footprint "1206A")
      (description "Zener Diode")
      (libsource (lib "*") (part "ZENER3"))
    )
    (comp (ref "V37") (value "1N4148") (footprint "1206A") (libsource (lib "*") (part "D")))
    (comp (ref "VR2") (value "200") (footprint "MINZIP") (libsource (lib "bom9200") (part "RN-742")))
    (comp (ref "VR4") (value "200") (footprint "MINZIP") (libsource (lib "bom9200") (part "RN-742")))
    (comp (ref "VR5") (value "200") (footprint "MINZIP") (libsource (lib "bom9200") (part "RN-742")))
    (comp (ref "XS1")
      (value "Header 4")
      (footprint "SIP-4")
      (description "Header, 4-Pin")
      (fields (field (name "PUBLISHER") "Altium Limited"))
      (libsource (lib "") (part "Header 4_1"))
    )
    (comp (ref "XS2")
      (value "Header 6")
      (footprint "SIP-6")
      (description "Header, 6-Pin")
      (fields (field (name "PUBLISHER") "Altium Limited"))
      (libsource (lib "Miscellaneous Connectors") (part "Header 6"))
    )
    (comp (ref "XS4")
      (value "Header 7")
      (footprint "SIP-7")
      (description "Header, 7-Pin")
      (fields (field (name "PUBLISHER") "Altium Limited"))
      (libsource (lib "") (part "Header 7_2"))
    )
    (comp (ref "XS6") (value "HEADER 5X2") (footprint "PHD-2*5") (libsource (lib "*") (part "HEADER 5X2")))
    (comp (ref "XS7")
      (value "Header 4")
      (footprint "SIP-4")
      (description "Header, 4-Pin")
      (fields (field (name "PUBLISHER") "Altium Limited"))
      (libsource (lib "Miscellaneous Connectors") (part "Header 4"))
    )
    (comp (ref "XS8")
      (value "Header 4")
      (footprint "SIP-4")
      (description "Header, 4-Pin")
      (fields (field (name "PUBLISHER") "Altium Limited"))
      (libsource (lib "Miscellaneous Connectors") (part "Header 4"))
    )
    (comp (ref "XS9")
      (value "Header 4")
      (footprint "SIP-4")
      (description "Header, 4-Pin")
      (fields (field (name "PUBLISHER") "Altium Limited"))
      (libsource (lib "Miscellaneous Connectors") (part "Header 4"))
    )
    (comp (ref "XS10")
      (value "Header 4")
      (footprint "SIP-4")
      (description "Header, 4-Pin")
      (fields (field (name "PUBLISHER") "Altium Limited"))
      (libsource (lib "Miscellaneous Connectors") (part "Header 4"))
    )
    (comp (ref "XS12")
      (value "Header 6X2")
      (footprint "PHD-2*6")
      (description "Header, 6-Pin, Dual row")
      (fields (field (name "PUBLISHER") "Altium Limited"))
      (libsource (lib "Miscellaneous Connectors") (part "Header 6X2"))
    )
    (comp (ref "XS13")
      (value "Header 5")
      (footprint "SIP-5")
      (description "Header, 5-Pin")
      (fields (field (name "PUBLISHER") "Altium Limited"))
      (libsource (lib "Miscellaneous Connectors") (part "Header 5"))
    )
    (comp (ref "XS14")
      (value "Header 8X2")
      (footprint "HDR2X8")
      (description "Header, 8-Pin, Dual row")
      (fields (field (name "PUBLISHER") "Altium Limited"))
      (libsource (lib "Miscellaneous Connectors") (part "Header 8X2"))
    )
    (comp (ref "XS15")
      (value "Header 3")
      (footprint "SIP-3")
      (description "Header, 3-Pin")
      (fields (field (name "PUBLISHER") "Altium Limited"))
      (libsource (lib "Miscellaneous Connectors") (part "Header 3"))
    )
    (comp (ref "XS16")
      (value "Header 5")
      (footprint "SIP-5")
      (description "Header, 5-Pin")
      (fields (field (name "PUBLISHER") "Altium Limited"))
      (libsource (lib "Miscellaneous Connectors") (part "Header 5"))
    )
    (comp (ref "XS17")
      (value "Header 6X2A")
      (footprint "HDR2X6_CEN")
      (description "Header, 6-Pin, Dual row")
      (fields (field (name "PUBLISHER") "Altium Limited"))
      (libsource (lib "Miscellaneous Connectors") (part "Header 6X2A"))
    )
    (comp (ref "XS18")
      (value "Header 5")
      (footprint "SIP-5")
      (description "Header, 5-Pin")
      (fields (field (name "PUBLISHER") "Altium Limited"))
      (libsource (lib "Miscellaneous Connectors") (part "Header 5"))
    )
    (comp (ref "XS19")
      (value "Header 5")
      (footprint "SIP-5")
      (description "Header, 5-Pin")
      (fields (field (name "PUBLISHER") "Altium Limited"))
      (libsource (lib "Miscellaneous Connectors") (part "Header 5"))
    )
    (comp (ref "XS20")
      (value "Header 5")
      (footprint "SIP-5")
      (description "Header, 5-Pin")
      (fields (field (name "PUBLISHER") "Altium Limited"))
      (libsource (lib "Miscellaneous Connectors") (part "Header 5"))
    )
    (comp (ref "XS21")
      (value "Header 3")
      (footprint "sip-3")
      (description "Header, 3-Pin")
      (fields (field (name "PUBLISHER") "Altium Limited"))
      (libsource (lib "Miscellaneous Connectors") (part "Header 3"))
    )
    (comp (ref "XS22")
      (value "Header 7")
      (footprint "sip-7")
      (description "Header, 7-Pin")
      (fields (field (name "PUBLISHER") "Altium Limited"))
      (libsource (lib "Miscellaneous Connectors") (part "Header 7"))
    )
    (comp (ref "XS23")
      (value "Header 7")
      (footprint "sip-7")
      (description "Header, 7-Pin")
      (fields (field (name "PUBLISHER") "Altium Limited"))
      (libsource (lib "") (part "Header 7_2"))
    )
    (comp (ref "XS24")
      (value "Header 7")
      (footprint "HDR1X7")
      (description "Header, 7-Pin")
      (fields (field (name "PUBLISHER") "Altium Limited"))
      (libsource (lib "") (part "Header 7_2"))
    )
    (comp (ref "XS25")
      (value "Header 7")
      (footprint "HDR1X7")
      (description "Header, 7-Pin")
      (fields (field (name "PUBLISHER") "Altium Limited"))
      (libsource (lib "") (part "Header 7_2"))
    )
    (comp (ref "XS27")
      (value "Header 7")
      (footprint "HDR1X7")
      (description "Header, 7-Pin")
      (fields (field (name "PUBLISHER") "Altium Limited"))
      (libsource (lib "") (part "Header 7_1"))
    )
    (comp (ref "XS28")
      (value "Header 7")
      (footprint "HDR1X7")
      (description "Header, 7-Pin")
      (fields (field (name "PUBLISHER") "Altium Limited"))
      (libsource (lib "Miscellaneous Connectors") (part "Header 7"))
    )
    (comp (ref "XS29")
      (value "Header 7")
      (footprint "HDR1X7")
      (description "Header, 7-Pin")
      (fields (field (name "PUBLISHER") "Altium Limited"))
      (libsource (lib "Miscellaneous Connectors") (part "Header 7"))
    )
    (comp (ref "XS30")
      (value "Header 7")
      (footprint "HDR1X7")
      (description "Header, 7-Pin")
      (fields (field (name "PUBLISHER") "Altium Limited"))
      (libsource (lib "Miscellaneous Connectors") (part "Header 7"))
    )
  )
  (nets
    (net (code "1") (name "+5V") (class "Default")
      (node (ref "C15") (pin "1") (pinfunction "1_1") (pintype "passive"))
      (node (ref "C17") (pin "1") (pinfunction "1_1") (pintype "passive"))
      (node (ref "C43") (pin "2") (pinfunction "2_2") (pintype "passive"))
      (node (ref "C63") (pin "1") (pinfunction "1_1") (pintype "passive"))
      (node (ref "C95") (pin "1") (pinfunction "1_1") (pintype "passive"))
      (node (ref "C97") (pin "1") (pinfunction "1_1") (pintype "passive"))
      (node (ref "C99") (pin "1") (pinfunction "1_1") (pintype "passive"))
      (node (ref "D1") (pin "14") (pinfunction "+5V_14") (pintype "power_in"))
      (node (ref "N10") (pin "5") (pinfunction "VL_5") (pintype "passive"))
      (node (ref "N13") (pin "10") (pinfunction "C_10") (pintype "passive"))
      (node (ref "N13") (pin "12") (pinfunction "C_12") (pintype "passive"))
      (node (ref "N13") (pin "14") (pinfunction "C_14") (pintype "passive"))
      (node (ref "N13") (pin "16") (pinfunction "C_16") (pintype "passive"))
      (node (ref "N15") (pin "10") (pinfunction "C_10") (pintype "passive"))
      (node (ref "N15") (pin "12") (pinfunction "C_12") (pintype "passive"))
      (node (ref "N15") (pin "14") (pinfunction "C_14") (pintype "passive"))
      (node (ref "N15") (pin "16") (pinfunction "C_16") (pintype "passive"))
      (node (ref "N16") (pin "6") (pinfunction "VO_6") (pintype "passive"))
      (node (ref "N16") (pin "8") (pinfunction "VCC_8") (pintype "passive"))
      (node (ref "N17") (pin "9") (pinfunction "COM_9") (pintype "passive"))
      (node (ref "N20") (pin "9") (pinfunction "COM_9") (pintype "passive"))
      (node (ref "N21") (pin "9") (pinfunction "COM_9") (pintype "passive"))
      (node (ref "N22") (pin "1") (pinfunction "Vin_1") (pintype "passive"))
      (node (ref "N24") (pin "6") (pinfunction "VDD_6") (pintype "passive"))
      (node (ref "N25") (pin "14") (pinfunction "C_14") (pintype "passive"))
      (node (ref "N25") (pin "16") (pinfunction "C_16") (pintype "passive"))
      (node (ref "N26") (pin "9") (pinfunction "COM_9") (pintype "passive"))
      (node (ref "N5") (pin "4") (pinfunction "V+_4") (pintype "passive"))
      (node (ref "N6") (pin "10") (pinfunction "C_10") (pintype "passive"))
      (node (ref "N6") (pin "12") (pinfunction "C_12") (pintype "passive"))
      (node (ref "N6") (pin "14") (pinfunction "C_14") (pintype "passive"))
      (node (ref "N6") (pin "16") (pinfunction "C_16") (pintype "passive"))
      (node (ref "N8") (pin "6") (pinfunction "VCC_6") (pintype "passive"))
      (node (ref "P4") (pin "2") (pinfunction "2_2") (pintype "passive"))
      (node (ref "P4") (pin "4") (pinfunction "4_4") (pintype "passive"))
      (node (ref "P4") (pin "6") (pinfunction "6_6") (pintype "passive"))
      (node (ref "P4") (pin "8") (pinfunction "8_8") (pintype "passive"))
      (node (ref "R125") (pin "1") (pinfunction "1_1") (pintype "passive"))
      (node (ref "R142") (pin "2") (pinfunction "2_2") (pintype "passive"))
      (node (ref "XS10") (pin "2") (pinfunction "2_2") (pintype "passive"))
      (node (ref "XS14") (pin "10") (pinfunction "10_10") (pintype "passive"))
      (node (ref "XS14") (pin "12") (pinfunction "12_12") (pintype "passive"))
      (node (ref "XS14") (pin "14") (pinfunction "14_14") (pintype "passive"))
      (node (ref "XS14") (pin "16") (pinfunction "16_16") (pintype "passive"))
      (node (ref "XS14") (pin "2") (pinfunction "2_2") (pintype "passive"))
      (node (ref "XS2") (pin "2") (pinfunction "2_2") (pintype "passive"))
      (node (ref "XS2") (pin "4") (pinfunction "4_4") (pintype "passive"))
      (node (ref "XS2") (pin "6") (pinfunction "6_6") (pintype "passive"))
      (node (ref "XS29") (pin "2") (pinfunction "2_2") (pintype "passive"))
      (node (ref "XS7") (pin "2") (pinfunction "2_2") (pintype "passive"))
      (node (ref "XS8") (pin "2") (pinfunction "2_2") (pintype "passive"))
      (node (ref "XS9") (pin "2") (pinfunction "2_2") (pintype "passive"))
    )
    (net (code "2") (name "+5V12") (class "Default")
      (node (ref "RL1") (pin "9") (pinfunction "9_9") (pintype "passive"))
      (node (ref "RL2") (pin "9") (pinfunction "9_9") (pintype "passive"))
      (node (ref "RL3") (pin "9") (pinfunction "9_9") (pintype "passive"))
      (node (ref "RL4") (pin "9") (pinfunction "9_9") (pintype "passive"))
      (node (ref "RL5") (pin "9") (pinfunction "9_9") (pintype "passive"))
      (node (ref "RL6") (pin "9") (pinfunction "9_9") (pintype "passive"))
      (node (ref "RL7") (pin "9") (pinfunction "9_9") (pintype "passive"))
      (node (ref "RL8") (pin "9") (pinfunction "9_9") (pintype "passive"))
      (node (ref "V19") (pin "2") (pinfunction "K_2") (pintype "passive"))
      (node (ref "V20") (pin "2") (pinfunction "K_2") (pintype "passive"))
      (node (ref "V21") (pin "2") (pinfunction "K_2") (pintype "passive"))
      (node (ref "V22") (pin "2") (pinfunction "K_2") (pintype "passive"))
      (node (ref "V23") (pin "2") (pinfunction "K_2") (pintype "passive"))
      (node (ref "V24") (pin "2") (pinfunction "K_2") (pintype "passive"))
      (node (ref "V25") (pin "2") (pinfunction "K_2") (pintype "passive"))
      (node (ref "V26") (pin "2") (pinfunction "K_2") (pintype "passive"))
      (node (ref "XS30") (pin "2") (pinfunction "2_2") (pintype "passive"))
    )
    (net (code "3") (name "+5VISO1") (class "Default")
      (node (ref "C90") (pin "2") (pintype "passive"))
      (node (ref "C91") (pin "2") (pinfunction "2_2") (pintype "passive"))
      (node (ref "C92") (pin "1") (pinfunction "1_1") (pintype "passive"))
      (node (ref "N22") (pin "4") (pinfunction "V+_4") (pintype "passive"))
      (node (ref "N23") (pin "16") (pinfunction "VDD2_16") (pintype "passive"))
      (node (ref "R109") (pin "1") (pinfunction "1_1") (pintype "passive"))
      (node (ref "R110") (pin "1") (pinfunction "1_1") (pintype "passive"))
      (node (ref "R123") (pin "2") (pinfunction "2_2") (pintype "passive"))
      (node (ref "U4") (pin "16") (pinfunction "VDD2_16") (pintype "passive"))
    )
    (net (code "4") (name "+12V") (class "Default")
      (node (ref "C106") (pin "1") (pinfunction "1_1") (pintype "passive"))
      (node (ref "C2") (pin "1") (pinfunction "1_1") (pintype "passive"))
      (node (ref "C29") (pin "1") (pinfunction "1_1") (pintype "passive"))
      (node (ref "C42") (pin "1") (pinfunction "1_1") (pintype "passive"))
      (node (ref "C44") (pin "2") (pinfunction "2_2") (pintype "passive"))
      (node (ref "C5") (pin "1") (pinfunction "1_1") (pintype "passive"))
      (node (ref "C52") (pin "1") (pinfunction "1_1") (pintype "passive"))
      (node (ref "C7") (pin "1") (pinfunction "1_1") (pintype "passive"))
      (node (ref "C8") (pin "1") (pinfunction "1_1") (pintype "passive"))
      (node (ref "C80") (pin "2") (pintype "passive"))
      (node (ref "C81") (pin "1") (pinfunction "1_1") (pintype "passive"))
      (node (ref "C85") (pin "1") (pinfunction "1_1") (pintype "passive"))
      (node (ref "C9") (pin "1") (pinfunction "1_1") (pintype "passive"))
      (node (ref "N10") (pin "4") (pinfunction "VDD_4") (pintype "passive"))
      (node (ref "N11") (pin "4") (pintype "passive"))
      (node (ref "N12") (pin "2") (pinfunction "IN_2") (pintype "passive"))
      (node (ref "N14") (pin "4") (pintype "passive"))
      (node (ref "N18") (pin "13") (pinfunction "TP_13") (pintype "passive"))
      (node (ref "N18") (pin "14") (pinfunction "VDD_14") (pintype "passive"))
      (node (ref "N19") (pin "2") (pinfunction "IN_2") (pintype "passive"))
      (node (ref "N2") (pin "4") (pinfunction "V+_4") (pintype "passive"))
      (node (ref "N3") (pin "4") (pintype "passive"))
      (node (ref "U1") (pin "3") (pinfunction "Vin_3") (pintype "passive"))
      (node (ref "U3") (pin "8") (pintype "passive"))
      (node (ref "XS10") (pin "1") (pinfunction "1_1") (pintype "passive"))
      (node (ref "XS7") (pin "1") (pinfunction "1_1") (pintype "passive"))
      (node (ref "XS8") (pin "1") (pinfunction "1_1") (pintype "passive"))
      (node (ref "XS9") (pin "1") (pinfunction "1_1") (pintype "passive"))
    )
    (net (code "5") (name "+12V1") (class "Default")
      (node (ref "C28") (pin "1") (pinfunction "1_1") (pintype "passive"))
      (node (ref "N9") (pin "4") (pintype "passive"))
    )
    (net (code "6") (name "+12VIN") (class "Default")
      (node (ref "C16") (pin "1") (pinfunction "1_1") (pintype "passive"))
      (node (ref "C19") (pin "1") (pinfunction "1_1") (pintype "passive"))
      (node (ref "C62") (pin "2") (pinfunction "2_2") (pintype "passive"))
      (node (ref "N4") (pin "2") (pinfunction "OUT_2") (pintype "passive"))
      (node (ref "U5") (pin "8") (pintype "passive"))
    )
    (net (code "7") (name "+24V") (class "Default")
      (node (ref "C12") (pin "1") (pinfunction "1_1") (pintype "passive"))
      (node (ref "C13") (pin "1") (pinfunction "1_1") (pintype "passive"))
      (node (ref "C24") (pin "2") (pinfunction "2_2") (pintype "passive"))
      (node (ref "C27") (pin "2") (pinfunction "2_2") (pintype "passive"))
      (node (ref "N2") (pin "1") (pinfunction "Vin_1") (pintype "passive"))
      (node (ref "N4") (pin "3") (pinfunction "IN_3") (pintype "passive"))
      (node (ref "N5") (pin "1") (pinfunction "Vin_1") (pintype "passive"))
      (node (ref "N7") (pin "1") (pinfunction "Vin_1") (pintype "passive"))
      (node (ref "R113") (pin "2") (pinfunction "2_2") (pintype "passive"))
      (node (ref "XS1") (pin "1") (pinfunction "1_1") (pintype "passive"))
      (node (ref "XS1") (pin "2") (pinfunction "2_2") (pintype "passive"))
      (node (ref "XS12") (pin "1") (pinfunction "1_1") (pintype "passive"))
      (node (ref "XS12") (pin "2") (pinfunction "2_2") (pintype "passive"))
      (node (ref "XS22") (pin "4") (pinfunction "4_4") (pintype "passive"))
      (node (ref "XS23") (pin "7") (pinfunction "7_7") (pintype "passive"))
      (node (ref "XS27") (pin "7") (pinfunction "7_7") (pintype "passive"))
    )
    (net (code "8") (name "-5V") (class "Default")
      (node (ref "C23") (pin "2") (pinfunction "2_2") (pintype "passive"))
      (node (ref "C26") (pin "2") (pinfunction "2_2") (pintype "passive"))
      (node (ref "N18") (pin "3") (pinfunction "VSS_3") (pintype "passive"))
      (node (ref "N7") (pin "3") (pinfunction "V-_3") (pintype "passive"))
      (node (ref "R28") (pin "1") (pinfunction "1_1") (pintype "passive"))
    )
    (net (code "9") (name "/+24V12") (class "Default")
      (node (ref "RL2") (pin "3") (pinfunction "3_3") (pintype "passive"))
      (node (ref "RL3") (pin "3") (pinfunction "3_3") (pintype "passive"))
      (node (ref "RL4") (pin "3") (pinfunction "3_3") (pintype "passive"))
      (node (ref "RL5") (pin "3") (pinfunction "3_3") (pintype "passive"))
      (node (ref "RL6") (pin "3") (pinfunction "3_3") (pintype "passive"))
      (node (ref "RL7") (pin "3") (pinfunction "3_3") (pintype "passive"))
      (node (ref "RL8") (pin "3") (pinfunction "3_3") (pintype "passive"))
      (node (ref "XS25") (pin "7") (pinfunction "7_7") (pintype "passive"))
    )
    (net (code "10") (name "/+24VGND12") (class "Default")
      (node (ref "RL2") (pin "1") (pinfunction "5_1") (pintype "passive"))
      (node (ref "RL3") (pin "1") (pinfunction "5_1") (pintype "passive"))
      (node (ref "RL4") (pin "1") (pinfunction "5_1") (pintype "passive"))
      (node (ref "RL5") (pin "1") (pinfunction "5_1") (pintype "passive"))
      (node (ref "RL6") (pin "1") (pinfunction "5_1") (pintype "passive"))
      (node (ref "RL7") (pin "1") (pinfunction "5_1") (pintype "passive"))
      (node (ref "RL8") (pin "1") (pinfunction "5_1") (pintype "passive"))
      (node (ref "XS25") (pin "6") (pinfunction "6_6") (pintype "passive"))
    )
    (net (code "11") (name "/A1") (class "Default")
      (node (ref "C93") (pin "1") (pinfunction "1_1") (pintype "passive"))
      (node (ref "C94") (pin "1") (pinfunction "1_1") (pintype "passive"))
      (node (ref "R109") (pin "2") (pinfunction "2_2") (pintype "passive"))
      (node (ref "R111") (pin "1") (pinfunction "1_1") (pintype "passive"))
      (node (ref "U4") (pin "14") (pinfunction "A_14") (pintype "passive"))
      (node (ref "V27") (pin "K") (pintype "passive"))
      (node (ref "XS13") (pin "1") (pinfunction "1_1") (pintype "passive"))
    )
    (net (code "12") (name "/ADC_IN1") (class "Default")
      (node (ref "U2") (pin "18") (pinfunction "PF6_18") (pintype "bidirectional"))
    )
    (net (code "14") (name "/ADC_IN2") (class "Default")
      (node (ref "U2") (pin "19") (pinfunction "PF7_19") (pintype "bidirectional"))
    )
    (net (code "15") (name "/ADC_IN2#") (class "Default")
      (node (ref "R16") (pin "1") (pinfunction "1_1") (pintype "passive"))
      (node (ref "V7") (pin "2") (pinfunction "K_2") (pintype "passive"))
    )
    (net (code "16") (name "/ADC_IN3") (class "Default")
      (node (ref "U2") (pin "20") (pinfunction "PF8_20") (pintype "bidirectional"))
    )
    (net (code "17") (name "/ADC_IN3#") (class "Default")
      (node (ref "R25") (pin "1") (pinfunction "1_1") (pintype "passive"))
      (node (ref "V11") (pin "2") (pinfunction "K_2") (pintype "passive"))
    )
    (net (code "18") (name "/ADC_IN4") (class "Default")
      (node (ref "U2") (pin "26") (pinfunction "PC0_26") (pintype "bidirectional"))
    )
    (net (code "19") (name "/ADC_IN4#") (class "Default")
      (node (ref "R36") (pin "1") (pinfunction "1_1") (pintype "passive"))
      (node (ref "V12") (pin "2") (pinfunction "K_2") (pintype "passive"))
    )
    (net (code "20") (name "/ADC_IN5") (class "Default")
      (node (ref "U2") (pin "27") (pinfunction "PC1_27") (pintype "bidirectional"))
    )
    (net (code "21") (name "/ADC_IN5#") (class "Default")
      (node (ref "R49") (pin "1") (pinfunction "1_1") (pintype "passive"))
      (node (ref "V14") (pin "2") (pinfunction "K_2") (pintype "passive"))
    )
    (net (code "22") (name "/ADC_IN6") (class "Default")
      (node (ref "U2") (pin "28") (pinfunction "PC2_28") (pintype "bidirectional"))
    )
    (net (code "23") (name "/ADC_IN6#") (class "Default")
      (node (ref "R62") (pin "1") (pinfunction "1_1") (pintype "passive"))
      (node (ref "V16") (pin "2") (pinfunction "K_2") (pintype "passive"))
    )
    (net (code "24") (name "/ADC_IN7") (class "Default")
      (node (ref "R38") (pin "1") (pinfunction "1_1") (pintype "passive"))
      (node (ref "U2") (pin "29") (pinfunction "PC3_29") (pintype "bidirectional"))
      (node (ref "V13") (pin "2") (pinfunction "K_2") (pintype "passive"))
    )
    (net (code "25") (name "/ADC_IN8") (class "Default")
      (node (ref "R52") (pin "1") (pinfunction "1_1") (pintype "passive"))
      (node (ref "U2") (pin "44") (pinfunction "PC4_44") (pintype "bidirectional"))
      (node (ref "V15") (pin "2") (pinfunction "K_2") (pintype "passive"))
    )
    (net (code "26") (name "/ADC_IN9") (class "Default")
      (node (ref "R65") (pin "1") (pinfunction "1_1") (pintype "passive"))
      (node (ref "U2") (pin "45") (pinfunction "PC5_45") (pintype "bidirectional"))
      (node (ref "V17") (pin "2") (pinfunction "K_2") (pintype "passive"))
    )
    (net (code "27") (name "/ADC_IN10") (class "Default")
      (node (ref "U2") (pin "21") (pinfunction "PF9_21") (pintype "bidirectional"))
    )
    (net (code "28") (name "/ADC_IN10#") (class "Default")
      (node (ref "R130") (pin "1") (pinfunction "1_1") (pintype "passive"))
      (node (ref "V34") (pin "2") (pinfunction "K_2") (pintype "passive"))
    )
    (net (code "29") (name "/ADC_IN11") (class "Default")
      (node (ref "U2") (pin "22") (pinfunction "PF10_22") (pintype "bidirectional"))
    )
    (net (code "30") (name "/ADC_IN11#") (class "Default")
      (node (ref "R136") (pin "1") (pinfunction "1_1") (pintype "passive"))
      (node (ref "V35") (pin "2") (pinfunction "K_2") (pintype "passive"))
    )
    (net (code "31") (name "/ADC_IN12") (class "Default")
      (node (ref "U2") (pin "40") (pinfunction "PA4_40") (pintype "bidirectional"))
    )
    (net (code "32") (name "/ADC_IN12#") (class "Default")
      (node (ref "R140") (pin "1") (pinfunction "1_1") (pintype "passive"))
      (node (ref "V36") (pin "2") (pinfunction "K_2") (pintype "passive"))
    )
    (net (code "33") (name "/Analog-in") (class "Default")
      (node (ref "C54") (pin "1") (pinfunction "1_1") (pintype "passive"))
      (node (ref "R73") (pin "1") (pinfunction "1_1") (pintype "passive"))
      (node (ref "XS21") (pin "2") (pinfunction "2_2") (pintype "passive"))
    )
    (net (code "34") (name "/B1") (class "Default")
      (node (ref "R111") (pin "2") (pinfunction "2_2") (pintype "passive"))
      (node (ref "U4") (pin "13") (pinfunction "B_13") (pintype "passive"))
      (node (ref "V29") (pin "K") (pintype "passive"))
      (node (ref "XS13") (pin "2") (pinfunction "2_2") (pintype "passive"))
    )
    (net (code "35") (name "/BOOT0") (class "Default")
      (node (ref "R107") (pin "2") (pinfunction "2_2") (pintype "passive"))
      (node (ref "U2") (pin "138") (pinfunction "BOOT0_138") (pintype "input"))
    )
    (net (code "36") (name "/BOOT1") (class "Default")
      (node (ref "R54") (pin "2") (pinfunction "2_2") (pintype "passive"))
      (node (ref "U2") (pin "48") (pinfunction "PB2_48") (pintype "bidirectional"))
    )
    (net (code "37") (name "/BRAKE") (class "Default")
      (node (ref "XS2") (pin "5") (pinfunction "5_5") (pintype "passive"))
    )
    (net (code "38") (name "/BRAKEMCU") (class "Default")
      (node (ref "D1") (pin "2") (pintype "output"))
      (node (ref "U2") (pin "88") (pinfunction "PG3_88") (pintype "bidirectional"))
    )
    (net (code "39") (name "/BUZZER_Out11") (class "Default")
      (node (ref "XS12") (pin "9") (pinfunction "9_9") (pintype "passive"))
    )
    (net (code "40") (name "/BUZZER_Out12") (class "Default")
      (node (ref "RL4") (pin "5") (pinfunction "5_5") (pintype "passive"))
      (node (ref "RL4") (pin "6") (pinfunction "6_6") (pintype "passive"))
      (node (ref "XS30") (pin "4") (pinfunction "4_4") (pintype "passive"))
    )
    (net (code "41") (name "/Bed_Clear_Fault") (class "Default")
      (node (ref "C60") (pin "2") (pinfunction "2_2") (pintype "passive"))
      (node (ref "N15") (pin "13") (pinfunction "E_13") (pintype "passive"))
      (node (ref "R88") (pin "1") (pinfunction "1_1") (pintype "passive"))
      (node (ref "U2") (pin "142") (pinfunction "PE1_142") (pintype "bidirectional"))
    )
    (net (code "42") (name "/Bed_PowerOff") (class "Default")
      (node (ref "C71") (pin "2") (pinfunction "2_2") (pintype "passive"))
      (node (ref "N15") (pin "9") (pinfunction "E_9") (pintype "passive"))
      (node (ref "R104") (pin "1") (pinfunction "1_1") (pintype "passive"))
      (node (ref "U2") (pin "93") (pinfunction "PG8_93") (pintype "bidirectional"))
    )
    (net (code "43") (name "/Bed_Red_Light") (class "Default")
      (node (ref "C65") (pin "2") (pinfunction "2_2") (pintype "passive"))
      (node (ref "N15") (pin "11") (pinfunction "E_11") (pintype "passive"))
      (node (ref "R99") (pin "1") (pinfunction "1_1") (pintype "passive"))
      (node (ref "U2") (pin "92") (pinfunction "PG7_92") (pintype "bidirectional"))
    )
    (net (code "44") (name "/Bed_Work_On") (class "Default")
      (node (ref "C55") (pin "2") (pinfunction "2_2") (pintype "passive"))
      (node (ref "N15") (pin "15") (pinfunction "E_15") (pintype "passive"))
      (node (ref "R82") (pin "1") (pinfunction "1_1") (pintype "passive"))
      (node (ref "U2") (pin "91") (pinfunction "PG6_91") (pintype "bidirectional"))
    )
    (net (code "45") (name "/CLKSEL") (class "Default")
      (node (ref "N10") (pin "6") (pinfunction "IN_6") (pintype "passive"))
      (node (ref "R45") (pin "2") (pinfunction "2_2") (pintype "passive"))
      (node (ref "U2") (pin "77") (pinfunction "PD8_77") (pintype "bidirectional"))
    )
    (net (code "46") (name "/DA_CLK") (class "Default")
      (node (ref "N18") (pin "10") (pinfunction "SCK_10") (pintype "passive"))
      (node (ref "U2") (pin "73") (pinfunction "PB12_73") (pintype "bidirectional"))
    )
    (net (code "47") (name "/DA_CS") (class "Default")
      (node (ref "N18") (pin "9") (pinfunction "~{CS}_9") (pintype "passive"))
      (node (ref "U2") (pin "75") (pinfunction "PB14_75") (pintype "bidirectional"))
    )
    (net (code "48") (name "/DA_DIN") (class "Default")
      (node (ref "N18") (pin "8") (pinfunction "SDI_8") (pintype "passive"))
      (node (ref "U2") (pin "74") (pinfunction "PB13_74") (pintype "bidirectional"))
    )
    (net (code "49") (name "/Emission11") (class "Default")
      (node (ref "XS23") (pin "3") (pinfunction "3_3") (pintype "passive"))
      (node (ref "XS27") (pin "3") (pinfunction "3_3") (pintype "passive"))
    )
    (net (code "50") (name "/Emission12") (class "Default")
      (node (ref "RL3") (pin "5") (pinfunction "5_5") (pintype "passive"))
      (node (ref "RL3") (pin "6") (pinfunction "6_6") (pintype "passive"))
      (node (ref "XS25") (pin "3") (pinfunction "3_3") (pintype "passive"))
    )
    (net (code "51") (name "/Ext_Iset") (class "Default")
      (node (ref "R76") (pin "2") (pinfunction "2_2") (pintype "passive"))
      (node (ref "U2") (pin "42") (pinfunction "PA6_42") (pintype "bidirectional"))
    )
    (net (code "52") (name "/Ext_Triger") (class "Default")
      (node (ref "C67") (pin "2") (pinfunction "2_2") (pintype "passive"))
      (node (ref "N10") (pin "8") (pinfunction "S2_8") (pintype "passive"))
      (node (ref "N16") (pin "5") (pinfunction "GND_5") (pintype "passive"))
      (node (ref "R97") (pin "1") (pinfunction "1_1") (pintype "passive"))
    )
    (net (code "53") (name "/Fault_PD1") (class "Default")
      (node (ref "C1") (pin "2") (pinfunction "2_2") (pintype "passive"))
      (node (ref "V4") (pin "1") (pinfunction "A_1") (pintype "passive"))
      (node (ref "XS14") (pin "4") (pinfunction "4_4") (pintype "passive"))
    )
    (net (code "54") (name "/Fault_PD2") (class "Default")
      (node (ref "C11") (pin "2") (pinfunction "2_2") (pintype "passive"))
      (node (ref "V5") (pin "1") (pinfunction "A_1") (pintype "passive"))
      (node (ref "XS14") (pin "6") (pinfunction "6_6") (pintype "passive"))
    )
    (net (code "55") (name "/Flow_Signal") (class "Default")
      (node (ref "R116") (pin "1") (pinfunction "1_1") (pintype "passive"))
      (node (ref "U2") (pin "139") (pinfunction "PB8_139") (pintype "bidirectional"))
    )
    (net (code "56") (name "/Gate") (class "Default")
      (node (ref "R86") (pin "2") (pinfunction "2_2") (pintype "passive"))
      (node (ref "XS22") (pin "2") (pinfunction "2_2") (pintype "passive"))
    )
    (net (code "57") (name "/Green_Out11") (class "Default")
      (node (ref "XS12") (pin "7") (pinfunction "7_7") (pintype "passive"))
    )
    (net (code "58") (name "/Green_Out12") (class "Default")
      (node (ref "RL7") (pin "5") (pinfunction "5_5") (pintype "passive"))
      (node (ref "RL7") (pin "6") (pinfunction "6_6") (pintype "passive"))
      (node (ref "XS30") (pin "5") (pinfunction "5_5") (pintype "passive"))
    )
    (net (code "59") (name "/IF OUT1") (class "Default")
      (node (ref "XS18") (pin "2") (pinfunction "2_2") (pintype "passive"))
    )
    (net (code "60") (name "/IF OUT1#") (class "Default")
      (node (ref "R7") (pin "1") (pinfunction "1_1") (pintype "passive"))
    )
    (net (code "61") (name "/IF OUT2") (class "Default")
      (node (ref "XS19") (pin "2") (pinfunction "2_2") (pintype "passive"))
    )
    (net (code "62") (name "/IF OUT2#") (class "Default")
      (node (ref "R37") (pin "1") (pinfunction "1_1") (pintype "passive"))
    )
    (net (code "63") (name "/IF OUT3") (class "Default")
      (node (ref "R39") (pin "1") (pinfunction "1_1") (pintype "passive"))
      (node (ref "XS20") (pin "2") (pinfunction "2_2") (pintype "passive"))
    )
    (net (code "64") (name "/IF OUT4") (class "Default")
      (node (ref "XS16") (pin "2") (pinfunction "2_2") (pintype "passive"))
    )
    (net (code "65") (name "/IF OUT4#") (class "Default")
      (node (ref "R141") (pin "1") (pinfunction "1_1") (pintype "passive"))
    )
    (net (code "66") (name "/IO_INPUT1") (class "Default")
      (node (ref "XS2") (pin "1") (pinfunction "1_1") (pintype "passive"))
    )
    (net (code "67") (name "/ISET1") (class "Default")
      (node (ref "C72") (pin "1") (pintype "passive"))
      (node (ref "C73") (pin "1") (pintype "passive"))
      (node (ref "N18") (pin "2") (pinfunction "OUTA_2") (pintype "passive"))
      (node (ref "XS17") (pin "ISET1") (pinfunction "1_ISET1") (pintype "passive"))
    )
    (net (code "68") (name "/ISET2") (class "Default")
      (node (ref "C74") (pin "1") (pintype "passive"))
      (node (ref "C75") (pin "1") (pintype "passive"))
      (node (ref "N18") (pin "1") (pinfunction "OUTB_1") (pintype "passive"))
      (node (ref "XS17") (pin "3") (pinfunction "3_3") (pintype "passive"))
    )
    (net (code "69") (name "/ISET3") (class "Default")
      (node (ref "C76") (pin "1") (pintype "passive"))
      (node (ref "C77") (pin "1") (pintype "passive"))
      (node (ref "N18") (pin "16") (pinfunction "OUTC_16") (pintype "passive"))
      (node (ref "XS17") (pin "5") (pinfunction "5_5") (pintype "passive"))
    )
    (net (code "70") (name "/ISET4") (class "Default")
      (node (ref "C78") (pin "1") (pintype "passive"))
      (node (ref "C79") (pin "1") (pintype "passive"))
      (node (ref "N18") (pin "15") (pinfunction "OUTD_15") (pintype "passive"))
      (node (ref "XS17") (pin "7") (pinfunction "7_7") (pintype "passive"))
    )
    (net (code "71") (name "/I_FaL1") (class "Default")
      (node (ref "C20") (pin "1") (pinfunction "1_1") (pintype "passive"))
      (node (ref "N6") (pin "1") (pinfunction "A_1") (pintype "passive"))
      (node (ref "XS18") (pin "1") (pinfunction "1_1") (pintype "passive"))
    )
    (net (code "72") (name "/I_FaL2") (class "Default")
      (node (ref "C21") (pin "2") (pinfunction "2_2") (pintype "passive"))
      (node (ref "N6") (pin "3") (pinfunction "A_3") (pintype "passive"))
      (node (ref "XS19") (pin "1") (pinfunction "1_1") (pintype "passive"))
    )
    (net (code "73") (name "/I_FaL3") (class "Default")
      (node (ref "C3") (pin "2") (pinfunction "2_2") (pintype "passive"))
      (node (ref "N6") (pin "5") (pinfunction "A_5") (pintype "passive"))
      (node (ref "XS20") (pin "1") (pinfunction "1_1") (pintype "passive"))
    )
    (net (code "74") (name "/I_FaL4") (class "Default")
      (node (ref "C105") (pin "2") (pinfunction "2_2") (pintype "passive"))
      (node (ref "N6") (pin "7") (pinfunction "A_7") (pintype "passive"))
      (node (ref "XS16") (pin "1") (pinfunction "1_1") (pintype "passive"))
    )
    (net (code "75") (name "/I_Fault1") (class "Default")
      (node (ref "N6") (pin "15") (pinfunction "E_15") (pintype "passive"))
      (node (ref "R18") (pin "1") (pinfunction "1_1") (pintype "passive"))
      (node (ref "U2") (pin "11") (pinfunction "PF1_11") (pintype "bidirectional"))
      (node (ref "V6") (pin "1") (pinfunction "A_1") (pintype "passive"))
    )
    (net (code "76") (name "/I_Fault2") (class "Default")
      (node (ref "N6") (pin "13") (pinfunction "E_13") (pintype "passive"))
      (node (ref "R21") (pin "1") (pinfunction "1_1") (pintype "passive"))
      (node (ref "U2") (pin "12") (pinfunction "PF2_12") (pintype "bidirectional"))
      (node (ref "V8") (pin "1") (pinfunction "A_1") (pintype "passive"))
    )
    (net (code "77") (name "/I_Fault3") (class "Default")
      (node (ref "N6") (pin "11") (pinfunction "E_11") (pintype "passive"))
      (node (ref "R11") (pin "1") (pinfunction "1_1") (pintype "passive"))
      (node (ref "U2") (pin "13") (pinfunction "PF3_13") (pintype "bidirectional"))
      (node (ref "V9") (pin "1") (pinfunction "A_1") (pintype "passive"))
    )
    (net (code "78") (name "/I_Fault4") (class "Default")
      (node (ref "N6") (pin "9") (pinfunction "E_9") (pintype "passive"))
      (node (ref "R24") (pin "1") (pinfunction "1_1") (pintype "passive"))
      (node (ref "U2") (pin "14") (pinfunction "PF4_14") (pintype "bidirectional"))
      (node (ref "V37") (pin "1") (pinfunction "A_1") (pintype "passive"))
    )
    (net (code "79") (name "/Int_Triger") (class "Default")
      (node (ref "N10") (pin "2") (pinfunction "S1_2") (pintype "passive"))
      (node (ref "U2") (pin "34") (pinfunction "PA0-WKUP_34") (pintype "bidirectional"))
    )
    (net (code "80") (name "/KEY_INPUT") (class "Default")
      (node (ref "D1") (pin "6") (pintype "output"))
      (node (ref "U2") (pin "90") (pinfunction "PG5_90") (pintype "bidirectional"))
    )
    (net (code "81") (name "/L1_MCU1") (class "Default")
      (node (ref "N13") (pin "15") (pinfunction "E_15") (pintype "passive"))
      (node (ref "R58") (pin "1") (pinfunction "1_1") (pintype "passive"))
      (node (ref "U2") (pin "1") (pinfunction "PE2_1") (pintype "bidirectional"))
    )
    (net (code "82") (name "/L1_MCU2") (class "Default")
      (node (ref "N13") (pin "13") (pinfunction "E_13") (pintype "passive"))
      (node (ref "R61") (pin "1") (pinfunction "1_1") (pintype "passive"))
      (node (ref "U2") (pin "4") (pinfunction "PE5_4") (pintype "bidirectional"))
    )
    (net (code "83") (name "/L1_OUT1") (class "Default")
      (node (ref "C47") (pin "1") (pinfunction "1_1") (pintype "passive"))
      (node (ref "N13") (pin "1") (pinfunction "A_1") (pintype "passive"))
      (node (ref "XS4") (pin "1") (pinfunction "1_1") (pintype "passive"))
    )
    (net (code "84") (name "/L1_OUT2") (class "Default")
      (node (ref "C48") (pin "1") (pinfunction "1_1") (pintype "passive"))
      (node (ref "N13") (pin "3") (pinfunction "A_3") (pintype "passive"))
      (node (ref "XS4") (pin "2") (pinfunction "2_2") (pintype "passive"))
    )
    (net (code "85") (name "/L2_MCU1") (class "Default")
      (node (ref "N13") (pin "11") (pinfunction "E_11") (pintype "passive"))
      (node (ref "R67") (pin "1") (pinfunction "1_1") (pintype "passive"))
      (node (ref "U2") (pin "2") (pinfunction "PE3_2") (pintype "bidirectional"))
    )
    (net (code "86") (name "/L2_MCU2") (class "Default")
      (node (ref "N13") (pin "9") (pinfunction "E_9") (pintype "passive"))
      (node (ref "R69") (pin "1") (pinfunction "1_1") (pintype "passive"))
      (node (ref "U2") (pin "5") (pinfunction "PE6_5") (pintype "bidirectional"))
    )
    (net (code "87") (name "/L2_OUT1") (class "Default")
      (node (ref "C49") (pin "1") (pinfunction "1_1") (pintype "passive"))
      (node (ref "N13") (pin "5") (pinfunction "A_5") (pintype "passive"))
      (node (ref "XS4") (pin "3") (pinfunction "3_3") (pintype "passive"))
    )
    (net (code "88") (name "/L2_OUT2") (class "Default")
      (node (ref "C50") (pin "1") (pinfunction "1_1") (pintype "passive"))
      (node (ref "N13") (pin "7") (pinfunction "A_7") (pintype "passive"))
      (node (ref "XS4") (pin "4") (pinfunction "4_4") (pintype "passive"))
    )
    (net (code "89") (name "/L3_MCU1") (class "Default")
      (node (ref "N25") (pin "15") (pinfunction "E_15") (pintype "passive"))
      (node (ref "R72") (pin "1") (pinfunction "1_1") (pintype "passive"))
      (node (ref "U2") (pin "3") (pinfunction "PE4_3") (pintype "bidirectional"))
    )
    (net (code "90") (name "/L3_MCU2") (class "Default")
      (node (ref "N25") (pin "13") (pinfunction "E_13") (pintype "passive"))
      (node (ref "R79") (pin "1") (pinfunction "1_1") (pintype "passive"))
      (node (ref "U2") (pin "111") (pinfunction "PC10_111") (pintype "bidirectional"))
    )
    (net (code "91") (name "/L3_OUT1") (class "Default")
      (node (ref "C51") (pin "1") (pinfunction "1_1") (pintype "passive"))
      (node (ref "N25") (pin "1") (pinfunction "A_1") (pintype "passive"))
      (node (ref "XS4") (pin "5") (pinfunction "5_5") (pintype "passive"))
    )
    (net (code "92") (name "/L3_OUT2") (class "Default")
      (node (ref "C53") (pin "1") (pinfunction "1_1") (pintype "passive"))
      (node (ref "N25") (pin "3") (pinfunction "A_3") (pintype "passive"))
      (node (ref "XS4") (pin "6") (pinfunction "6_6") (pintype "passive"))
    )
    (net (code "93") (name "/LD_EN") (class "Default")
      (node (ref "U2") (pin "10") (pinfunction "PF0_10") (pintype "bidirectional"))
      (node (ref "V2") (pin "1") (pinfunction "A_1") (pintype "passive"))
    )
    (net (code "94") (name "/LD_OnOff") (class "Default")
      (node (ref "N17") (pin "7") (pinfunction "IN7_7") (pintype "passive"))
      (node (ref "U2") (pin "86") (pinfunction "PD15_86") (pintype "bidirectional"))
    )
    (net (code "95") (name "/LD_Power11") (class "Default")
      (node (ref "XS12") (pin "11") (pinfunction "11_11") (pintype "passive"))
    )
    (net (code "96") (name "/LD_Power12") (class "Default")
      (node (ref "RL8") (pin "5") (pinfunction "5_5") (pintype "passive"))
      (node (ref "RL8") (pin "6") (pinfunction "6_6") (pintype "passive"))
      (node (ref "XS30") (pin "3") (pinfunction "3_3") (pintype "passive"))
    )
    (net (code "97") (name "/LED1") (class "Default")
      (node (ref "N21") (pin "1") (pinfunction "IN1_1") (pintype "passive"))
      (node (ref "U2") (pin "114") (pinfunction "PD0_114") (pintype "bidirectional"))
    )
    (net (code "98") (name "/LED1_OUT") (class "Default")
      (node (ref "VR2") (pin "8") (pinfunction "8_8") (pintype "passive"))
      (node (ref "XS14") (pin "1") (pinfunction "1_1") (pintype "passive"))
    )
    (net (code "99") (name "/LED2") (class "Default")
      (node (ref "N21") (pin "2") (pinfunction "IN2_2") (pintype "passive"))
      (node (ref "U2") (pin "115") (pinfunction "PD1_115") (pintype "bidirectional"))
    )
    (net (code "100") (name "/LED2_OUT") (class "Default")
      (node (ref "VR2") (pin "7") (pinfunction "7_7") (pintype "passive"))
      (node (ref "XS14") (pin "3") (pinfunction "3_3") (pintype "passive"))
    )
    (net (code "101") (name "/LED3") (class "Default")
      (node (ref "N21") (pin "3") (pinfunction "IN3_3") (pintype "passive"))
      (node (ref "U2") (pin "116") (pinfunction "PD2_116") (pintype "bidirectional"))
    )
    (net (code "102") (name "/LED3_OUT") (class "Default")
      (node (ref "VR2") (pin "6") (pinfunction "6_6") (pintype "passive"))
      (node (ref "XS14") (pin "5") (pinfunction "5_5") (pintype "passive"))
    )
    (net (code "103") (name "/LED4") (class "Default")
      (node (ref "N21") (pin "4") (pinfunction "IN4_4") (pintype "passive"))
      (node (ref "U2") (pin "117") (pinfunction "PD3_117") (pintype "bidirectional"))
    )
    (net (code "104") (name "/LED4_OUT") (class "Default")
      (node (ref "VR2") (pin "5") (pinfunction "5_5") (pintype "passive"))
      (node (ref "XS14") (pin "7") (pinfunction "7_7") (pintype "passive"))
    )
    (net (code "105") (name "/LED5") (class "Default")
      (node (ref "N21") (pin "5") (pinfunction "IN5_5") (pintype "passive"))
      (node (ref "U2") (pin "118") (pinfunction "PD4_118") (pintype "bidirectional"))
    )
    (net (code "106") (name "/LED5_OUT") (class "Default")
      (node (ref "VR4") (pin "8") (pinfunction "8_8") (pintype "passive"))
      (node (ref "XS14") (pin "9") (pinfunction "9_9") (pintype "passive"))
    )
    (net (code "107") (name "/LED6") (class "Default")
      (node (ref "N21") (pin "6") (pinfunction "IN6_6") (pintype "passive"))
      (node (ref "U2") (pin "119") (pinfunction "PD5_119") (pintype "bidirectional"))
    )
    (net (code "108") (name "/LED6_OUT") (class "Default")
      (node (ref "VR4") (pin "7") (pinfunction "7_7") (pintype "passive"))
      (node (ref "XS14") (pin "11") (pinfunction "11_11") (pintype "passive"))
    )
    (net (code "109") (name "/LED7") (class "Default")
      (node (ref "N26") (pin "4") (pinfunction "IN4_4") (pintype "passive"))
      (node (ref "U2") (pin "122") (pinfunction "PD6_122") (pintype "bidirectional"))
    )
    (net (code "110") (name "/LED7_OUT") (class "Default")
      (node (ref "VR5") (pin "8") (pinfunction "8_8") (pintype "passive"))
      (node (ref "XS14") (pin "13") (pinfunction "13_13") (pintype "passive"))
    )
    (net (code "111") (name "/LED8") (class "Default")
      (node (ref "N26") (pin "5") (pinfunction "IN5_5") (pintype "passive"))
      (node (ref "U2") (pin "123") (pinfunction "PD7_123") (pintype "bidirectional"))
    )
    (net (code "112") (name "/LED8_OUT") (class "Default")
      (node (ref "VR5") (pin "7") (pinfunction "7_7") (pintype "passive"))
      (node (ref "XS14") (pin "15") (pinfunction "15_15") (pintype "passive"))
    )
    (net (code "113") (name "/LED_BUZZER") (class "Default")
      (node (ref "N20") (pin "5") (pinfunction "IN5_5") (pintype "passive"))
      (node (ref "U2") (pin "126") (pinfunction "PG11_126") (pintype "bidirectional"))
    )
    (net (code "114") (name "/LED_Green") (class "Default")
      (node (ref "N20") (pin "6") (pinfunction "IN6_6") (pintype "passive"))
      (node (ref "U2") (pin "125") (pinfunction "PG10_125") (pintype "bidirectional"))
    )
    (net (code "115") (name "/LED_RED") (class "Default")
      (node (ref "N20") (pin "1") (pinfunction "IN1_1") (pintype "passive"))
      (node (ref "U2") (pin "132") (pinfunction "PG15_132") (pintype "bidirectional"))
    )
    (net (code "116") (name "/LED_Yellow") (class "Default")
      (node (ref "N20") (pin "2") (pinfunction "IN2_2") (pintype "passive"))
      (node (ref "U2") (pin "129") (pinfunction "PG14_129") (pintype "bidirectional"))
    )
    (net (code "117") (name "/Lock11") (class "Default")
      (node (ref "XS23") (pin "5") (pinfunction "5_5") (pintype "passive"))
      (node (ref "XS27") (pin "5") (pinfunction "5_5") (pintype "passive"))
    )
    (net (code "118") (name "/Lock12") (class "Default")
      (node (ref "XS25") (pin "5") (pinfunction "5_5") (pintype "passive"))
    )
    (net (code "119") (name "/Mcu_Emission") (class "Default")
      (node (ref "N20") (pin "4") (pinfunction "IN4_4") (pintype "passive"))
      (node (ref "U2") (pin "127") (pinfunction "PG12_127") (pintype "bidirectional"))
    )
    (net (code "120") (name "/Mcu_Ready") (class "Default")
      (node (ref "N20") (pin "3") (pinfunction "IN3_3") (pintype "passive"))
      (node (ref "U2") (pin "128") (pinfunction "PG13_128") (pintype "bidirectional"))
    )
    (net (code "121") (name "/NJTRST") (class "Default")
      (node (ref "R96") (pin "2") (pinfunction "2_2") (pintype "passive"))
      (node (ref "U2") (pin "134") (pinfunction "PB4_134") (pintype "bidirectional"))
      (node (ref "XS6") (pin "3") (pinfunction "3_3") (pintype "passive"))
    )
    (net (code "122") (name "/NRST") (class "Default")
      (node (ref "C82") (pin "2") (pinfunction "2_2") (pintype "passive"))
      (node (ref "C83") (pin "2") (pinfunction "2_2") (pintype "passive"))
      (node (ref "R106") (pin "1") (pinfunction "1_1") (pintype "passive"))
      (node (ref "S1") (pin "2") (pinfunction "NO_2") (pintype "passive"))
      (node (ref "U2") (pin "25") (pinfunction "NRST_25") (pintype "bidirectional"))
      (node (ref "XS6") (pin "4") (pinfunction "4_4") (pintype "passive"))
    )
    (net (code "123") (name "/OSC_IN") (class "Default")
      (node (ref "B1") (pin "2") (pinfunction "2_2") (pintype "passive"))
      (node (ref "C84") (pin "1") (pinfunction "1_1") (pintype "passive"))
      (node (ref "U2") (pin "23") (pinfunction "OSC_IN_23") (pintype "input"))
    )
    (net (code "124") (name "/OSC_OUT") (class "Default")
      (node (ref "B1") (pin "1") (pinfunction "1_1") (pintype "passive"))
      (node (ref "C89") (pin "2") (pinfunction "2_2") (pintype "passive"))
      (node (ref "U2") (pin "24") (pinfunction "OSC_OUT_24") (pintype "output"))
    )
    (net (code "125") (name "/Polit-on") (class "Default")
      (node (ref "R89") (pin "2") (pinfunction "2_2") (pintype "passive"))
      (node (ref "XS22") (pin "5") (pinfunction "5_5") (pintype "passive"))
    )
    (net (code "126") (name "/Power-on") (class "Default")
      (node (ref "R74") (pin "2") (pinfunction "2_2") (pintype "passive"))
      (node (ref "XS22") (pin "7") (pinfunction "7_7") (pintype "passive"))
    )
    (net (code "127") (name "/PowerOff-inb") (class "Default")
      (node (ref "R100") (pin "2") (pinfunction "2_2") (pintype "passive"))
      (node (ref "XS22") (pin "3") (pinfunction "3_3") (pintype "passive"))
    )
    (net (code "129") (name "/PowerOff-outa12") (class "Default")
      (node (ref "RL1") (pin "5") (pinfunction "5_5") (pintype "passive"))
      (node (ref "RL1") (pin "6") (pinfunction "6_6") (pintype "passive"))
      (node (ref "XS25") (pin "1") (pinfunction "1_1") (pintype "passive"))
    )
    (net (code "131") (name "/PowerOff-outb12") (class "Default")
      (node (ref "RL1") (pin "1") (pinfunction "5_1") (pintype "passive"))
      (node (ref "XS25") (pin "2") (pinfunction "2_2") (pintype "passive"))
    )
    (net (code "132") (name "/Power_Back") (class "Default")
      (node (ref "C107") (pin "1") (pintype "passive"))
      (node (ref "C108") (pin "1") (pintype "passive"))
      (node (ref "R92") (pin "1") (pinfunction "1_1") (pintype "passive"))
      (node (ref "U2") (pin "41") (pinfunction "PA5_41") (pintype "bidirectional"))
    )
    (net (code "133") (name "/Pulse") (class "Default")
      (node (ref "N8") (pin "5") (pinfunction "Bout_5") (pintype "passive"))
      (node (ref "N8") (pin "7") (pinfunction "Aout_7") (pintype "passive"))
      (node (ref "R35") (pin "2") (pinfunction "2_2") (pintype "passive"))
      (node (ref "U2") (pin "140") (pinfunction "PB9_140") (pintype "bidirectional"))
      (node (ref "U2") (pin "141") (pinfunction "PE0_141") (pintype "bidirectional"))
      (node (ref "XS17") (pin "2") (pinfunction "2_2") (pintype "passive"))
      (node (ref "XS17") (pin "4") (pinfunction "4_4") (pintype "passive"))
      (node (ref "XS17") (pin "6") (pinfunction "6_6") (pintype "passive"))
      (node (ref "XS17") (pin "8") (pinfunction "8_8") (pintype "passive"))
    )
    (net (code "134") (name "/RL11") (class "Default")
      (node (ref "N20") (pin "10") (pinfunction "OUT7_10") (pintype "passive"))
      (node (ref "XS28") (pin "1") (pinfunction "1_1") (pintype "passive"))
    )
    (net (code "135") (name "/RL12") (class "Default")
      (node (ref "RL1") (pin "2") (pinfunction "2_2") (pintype "passive"))
      (node (ref "V19") (pin "1") (pinfunction "A_1") (pintype "passive"))
      (node (ref "XS24") (pin "7") (pinfunction "7_7") (pintype "passive"))
    )
    (net (code "136") (name "/RL21") (class "Default")
      (node (ref "N20") (pin "14") (pinfunction "OUT3_14") (pintype "passive"))
      (node (ref "XS28") (pin "5") (pinfunction "5_5") (pintype "passive"))
    )
    (net (code "137") (name "/RL22") (class "Default")
      (node (ref "RL2") (pin "2") (pinfunction "2_2") (pintype "passive"))
      (node (ref "V20") (pin "1") (pinfunction "A_1") (pintype "passive"))
      (node (ref "XS24") (pin "3") (pinfunction "3_3") (pintype "passive"))
    )
    (net (code "138") (name "/RL31") (class "Default")
      (node (ref "N20") (pin "13") (pinfunction "OUT4_13") (pintype "passive"))
      (node (ref "XS28") (pin "4") (pinfunction "4_4") (pintype "passive"))
    )
    (net (code "139") (name "/RL32") (class "Default")
      (node (ref "RL3") (pin "2") (pinfunction "2_2") (pintype "passive"))
      (node (ref "V21") (pin "1") (pinfunction "A_1") (pintype "passive"))
      (node (ref "XS24") (pin "4") (pinfunction "4_4") (pintype "passive"))
    )
    (net (code "140") (name "/RL41") (class "Default")
      (node (ref "N20") (pin "12") (pinfunction "OUT5_12") (pintype "passive"))
      (node (ref "XS28") (pin "3") (pinfunction "3_3") (pintype "passive"))
    )
    (net (code "141") (name "/RL42") (class "Default")
      (node (ref "RL4") (pin "2") (pinfunction "2_2") (pintype "passive"))
      (node (ref "V22") (pin "1") (pinfunction "A_1") (pintype "passive"))
      (node (ref "XS24") (pin "5") (pinfunction "5_5") (pintype "passive"))
    )
    (net (code "142") (name "/RL51") (class "Default")
      (node (ref "N20") (pin "16") (pinfunction "OUT1_16") (pintype "passive"))
      (node (ref "XS28") (pin "7") (pinfunction "7_7") (pintype "passive"))
    )
    (net (code "143") (name "/RL52") (class "Default")
      (node (ref "RL5") (pin "2") (pinfunction "2_2") (pintype "passive"))
      (node (ref "V23") (pin "1") (pinfunction "A_1") (pintype "passive"))
      (node (ref "XS24") (pin "1") (pinfunction "1_1") (pintype "passive"))
    )
    (net (code "144") (name "/RL61") (class "Default")
      (node (ref "N20") (pin "15") (pinfunction "OUT2_15") (pintype "passive"))
      (node (ref "XS28") (pin "6") (pinfunction "6_6") (pintype "passive"))
    )
    (net (code "145") (name "/RL62") (class "Default")
      (node (ref "RL6") (pin "2") (pinfunction "2_2") (pintype "passive"))
      (node (ref "V24") (pin "1") (pinfunction "A_1") (pintype "passive"))
      (node (ref "XS24") (pin "2") (pinfunction "2_2") (pintype "passive"))
    )
    (net (code "146") (name "/RL71") (class "Default")
      (node (ref "N20") (pin "11") (pinfunction "OUT6_11") (pintype "passive"))
      (node (ref "XS28") (pin "2") (pinfunction "2_2") (pintype "passive"))
    )
    (net (code "147") (name "/RL72") (class "Default")
      (node (ref "RL7") (pin "2") (pinfunction "2_2") (pintype "passive"))
      (node (ref "V25") (pin "1") (pinfunction "A_1") (pintype "passive"))
      (node (ref "XS24") (pin "6") (pinfunction "6_6") (pintype "passive"))
    )
    (net (code "148") (name "/RL81") (class "Default")
      (node (ref "N17") (pin "10") (pinfunction "OUT7_10") (pintype "passive"))
    )
    (net (code "149") (name "/RL82") (class "Default")
      (node (ref "RL8") (pin "2") (pinfunction "2_2") (pintype "passive"))
      (node (ref "V26") (pin "1") (pinfunction "A_1") (pintype "passive"))
      (node (ref "XS30") (pin "1") (pinfunction "1_1") (pintype "passive"))
    )
    (net (code "150") (name "/RXD1") (class "Default")
      (node (ref "D5") (pin "2") (pinfunction "2_2") (pintype "passive"))
      (node (ref "N23") (pin "5") (pinfunction "RxD_5") (pintype "passive"))
      (node (ref "U2") (pin "102") (pinfunction "PA10_102") (pintype "bidirectional"))
    )
    (net (code "151") (name "/Ready11") (class "Default")
      (node (ref "XS23") (pin "4") (pinfunction "4_4") (pintype "passive"))
      (node (ref "XS27") (pin "4") (pinfunction "4_4") (pintype "passive"))
    )
    (net (code "152") (name "/Ready12") (class "Default")
      (node (ref "RL2") (pin "5") (pinfunction "5_5") (pintype "passive"))
      (node (ref "RL2") (pin "6") (pinfunction "6_6") (pintype "passive"))
      (node (ref "XS25") (pin "4") (pinfunction "4_4") (pintype "passive"))
    )
    (net (code "153") (name "/Red_Out11") (class "Default")
      (node (ref "XS12") (pin "3") (pinfunction "3_3") (pintype "passive"))
    )
    (net (code "154") (name "/Red_Out12") (class "Default")
      (node (ref "RL5") (pin "5") (pinfunction "5_5") (pintype "passive"))
      (node (ref "RL5") (pin "6") (pinfunction "6_6") (pintype "passive"))
      (node (ref "XS30") (pin "7") (pinfunction "7_7") (pintype "passive"))
    )
    (net (code "155") (name "/Reset") (class "Default")
      (node (ref "R81") (pin "2") (pinfunction "2_2") (pintype "passive"))
      (node (ref "XS22") (pin "6") (pinfunction "6_6") (pintype "passive"))
    )
    (net (code "156") (name "/START") (class "Default")
      (node (ref "R13") (pin "2") (pinfunction "2_2") (pintype "passive"))
      (node (ref "XS2") (pin "3") (pinfunction "3_3") (pintype "passive"))
    )
    (net (code "157") (name "/STARTMCU") (class "Default")
      (node (ref "D1") (pin "4") (pintype "output"))
      (node (ref "U2") (pin "89") (pinfunction "PG4_89") (pintype "bidirectional"))
    )
    (net (code "158") (name "/Set_Voltage1") (class "Default")
      (node (ref "N17") (pin "2") (pinfunction "IN2_2") (pintype "passive"))
      (node (ref "U2") (pin "136") (pinfunction "PB6_136") (pintype "bidirectional"))
    )
    (net (code "159") (name "/Set_Voltage2") (class "Default")
      (node (ref "N17") (pin "4") (pinfunction "IN4_4") (pintype "passive"))
      (node (ref "U2") (pin "137") (pinfunction "PB7_137") (pintype "bidirectional"))
    )
    (net (code "160") (name "/Set_Voltage3") (class "Default")
      (node (ref "N17") (pin "6") (pinfunction "IN6_6") (pintype "passive"))
      (node (ref "U2") (pin "46") (pinfunction "PB0_46") (pintype "bidirectional"))
    )
    (net (code "161") (name "/Set_Voltage4") (class "Default")
      (node (ref "N26") (pin "2") (pinfunction "IN2_2") (pintype "passive"))
      (node (ref "U2") (pin "47") (pinfunction "PB1_47") (pintype "bidirectional"))
    )
    (net (code "162") (name "/TCK") (class "Default")
      (node (ref "R101") (pin "2") (pinfunction "2_2") (pintype "passive"))
      (node (ref "U2") (pin "109") (pinfunction "PA14_109") (pintype "bidirectional"))
      (node (ref "XS6") (pin "10") (pinfunction "10_10") (pintype "passive"))
    )
    (net (code "163") (name "/TDI") (class "Default")
      (node (ref "R95") (pin "2") (pinfunction "2_2") (pintype "passive"))
      (node (ref "U2") (pin "110") (pinfunction "PA15_110") (pintype "bidirectional"))
      (node (ref "XS6") (pin "5") (pinfunction "5_5") (pintype "passive"))
    )
    (net (code "164") (name "/TDO") (class "Default")
      (node (ref "R93") (pin "2") (pinfunction "2_2") (pintype "passive"))
      (node (ref "U2") (pin "133") (pinfunction "PB3_133") (pintype "bidirectional"))
      (node (ref "XS6") (pin "9") (pinfunction "9_9") (pintype "passive"))
    )
    (net (code "165") (name "/TMS") (class "Default")
      (node (ref "R94") (pin "2") (pinfunction "2_2") (pintype "passive"))
      (node (ref "U2") (pin "105") (pinfunction "PA13_105") (pintype "bidirectional"))
      (node (ref "XS6") (pin "7") (pinfunction "7_7") (pintype "passive"))
    )
    (net (code "166") (name "/TXD1") (class "Default")
      (node (ref "D6") (pin "2") (pinfunction "2_2") (pintype "passive"))
      (node (ref "N23") (pin "8") (pinfunction "TxD_8") (pintype "passive"))
      (node (ref "U2") (pin "101") (pinfunction "PA9_101") (pintype "bidirectional"))
    )
    (net (code "167") (name "/VF OUT1") (class "Default")
      (node (ref "XS18") (pin "3") (pinfunction "3_3") (pintype "passive"))
    )
    (net (code "168") (name "/VF OUT1#") (class "Default")
      (node (ref "R14") (pin "1") (pinfunction "1_1") (pintype "passive"))
    )
    (net (code "169") (name "/VF OUT2") (class "Default")
      (node (ref "XS19") (pin "3") (pinfunction "3_3") (pintype "passive"))
    )
    (net (code "170") (name "/VF OUT2#") (class "Default")
      (node (ref "R48") (pin "1") (pinfunction "1_1") (pintype "passive"))
    )
    (net (code "171") (name "/VF OUT3") (class "Default")
      (node (ref "R50") (pin "1") (pinfunction "1_1") (pintype "passive"))
      (node (ref "XS20") (pin "3") (pinfunction "3_3") (pintype "passive"))
    )
    (net (code "172") (name "/VF OUT4") (class "Default")
      (node (ref "XS16") (pin "3") (pinfunction "3_3") (pintype "passive"))
    )
    (net (code "173") (name "/VF OUT4#") (class "Default")
      (node (ref "R132") (pin "1") (pinfunction "1_1") (pintype "passive"))
    )
    (net (code "174") (name "/VMOS OUT1") (class "Default")
      (node (ref "XS18") (pin "4") (pinfunction "4_4") (pintype "passive"))
    )
    (net (code "175") (name "/VMOS OUT1#") (class "Default")
      (node (ref "R22") (pin "1") (pinfunction "1_1") (pintype "passive"))
    )
    (net (code "176") (name "/VMOS OUT2") (class "Default")
      (node (ref "R60") (pin "1") (pinfunction "1_1") (pintype "passive"))
      (node (ref "XS19") (pin "4") (pinfunction "4_4") (pintype "passive"))
    )
    (net (code "177") (name "/VMOS OUT3") (class "Default")
      (node (ref "R63") (pin "1") (pinfunction "1_1") (pintype "passive"))
      (node (ref "XS20") (pin "4") (pinfunction "4_4") (pintype "passive"))
    )
    (net (code "178") (name "/VMOS OUT4") (class "Default")
      (node (ref "XS16") (pin "4") (pinfunction "4_4") (pintype "passive"))
    )
    (net (code "180") (name "/VREF") (class "Default")
      (node (ref "C45") (pin "1") (pintype "passive"))
      (node (ref "C46") (pin "2") (pinfunction "2_2") (pintype "passive"))
      (node (ref "N12") (pin "6") (pinfunction "OUT_6") (pintype "passive"))
      (node (ref "U2") (pin "32") (pinfunction "VREF+_32") (pintype "power_in"))
    )
    (net (code "181") (name "/Ven_Input1") (class "Default")
      (node (ref "N17") (pin "1") (pinfunction "IN1_1") (pintype "passive"))
      (node (ref "U2") (pin "50") (pinfunction "PF12_50") (pintype "bidirectional"))
    )
    (net (code "182") (name "/Ven_Input2") (class "Default")
      (node (ref "N17") (pin "3") (pinfunction "IN3_3") (pintype "passive"))
      (node (ref "U2") (pin "53") (pinfunction "PF13_53") (pintype "bidirectional"))
    )
    (net (code "183") (name "/Ven_Input3") (class "Default")
      (node (ref "N17") (pin "5") (pinfunction "IN5_5") (pintype "passive"))
      (node (ref "U2") (pin "54") (pinfunction "PF14_54") (pintype "bidirectional"))
    )
    (net (code "184") (name "/Ven_Input4") (class "Default")
      (node (ref "N26") (pin "1") (pinfunction "IN1_1") (pintype "passive"))
      (node (ref "U2") (pin "55") (pinfunction "PF15_55") (pintype "bidirectional"))
    )
    (net (code "185") (name "/Ven_Output1") (class "Default")
      (node (ref "N17") (pin "16") (pinfunction "OUT1_16") (pintype "passive"))
      (node (ref "XS7") (pin "3") (pinfunction "3_3") (pintype "passive"))
    )
    (net (code "186") (name "/Ven_Output2") (class "Default")
      (node (ref "N17") (pin "14") (pinfunction "OUT3_14") (pintype "passive"))
      (node (ref "XS8") (pin "3") (pinfunction "3_3") (pintype "passive"))
    )
    (net (code "187") (name "/Ven_Output3") (class "Default")
      (node (ref "N17") (pin "12") (pinfunction "OUT5_12") (pintype "passive"))
      (node (ref "XS9") (pin "3") (pinfunction "3_3") (pintype "passive"))
    )
    (net (code "188") (name "/Ven_Output4") (class "Default")
      (node (ref "N26") (pin "16") (pinfunction "OUT1_16") (pintype "passive"))
      (node (ref "XS10") (pin "3") (pinfunction "3_3") (pintype "passive"))
    )
    (net (code "189") (name "/Vset_Output1") (class "Default")
      (node (ref "N17") (pin "15") (pinfunction "OUT2_15") (pintype "passive"))
      (node (ref "XS7") (pin "4") (pinfunction "4_4") (pintype "passive"))
    )
    (net (code "190") (name "/Vset_Output2") (class "Default")
      (node (ref "N17") (pin "13") (pinfunction "OUT4_13") (pintype "passive"))
      (node (ref "XS8") (pin "4") (pinfunction "4_4") (pintype "passive"))
    )
    (net (code "191") (name "/Vset_Output3") (class "Default")
      (node (ref "N17") (pin "11") (pinfunction "OUT6_11") (pintype "passive"))
      (node (ref "XS9") (pin "4") (pinfunction "4_4") (pintype "passive"))
    )
    (net (code "192") (name "/Vset_Output4") (class "Default")
      (node (ref "N26") (pin "15") (pinfunction "OUT2_15") (pintype "passive"))
      (node (ref "XS10") (pin "4") (pinfunction "4_4") (pintype "passive"))
    )
    (net (code "194") (name "/Water-") (class "Default")
      (node (ref "VR4") (pin "5") (pinfunction "5_5") (pintype "passive"))
      (node (ref "VR4") (pin "6") (pinfunction "6_6") (pintype "passive"))
    )
    (net (code "195") (name "/Water_Fault") (class "Default")
      (node (ref "N25") (pin "12") (pinfunction "C_12") (pintype "passive"))
      (node (ref "R142") (pin "1") (pinfunction "1_1") (pintype "passive"))
      (node (ref "U2") (pin "15") (pinfunction "PF5_15") (pintype "bidirectional"))
      (node (ref "V10") (pin "1") (pinfunction "A_1") (pintype "passive"))
    )
    (net (code "196") (name "/Water_Flow") (class "Default")
      (node (ref "C102") (pin "2") (pinfunction "2_2") (pintype "passive"))
      (node (ref "N24") (pin "1") (pinfunction "IN+_1") (pintype "passive"))
      (node (ref "R113") (pin "1") (pinfunction "1_1") (pintype "passive"))
      (node (ref "R118") (pin "1") (pinfunction "1_1") (pintype "passive"))
      (node (ref "XS12") (pin "10") (pinfunction "10_10") (pintype "passive"))
    )
    (net (code "197") (name "/Water_IN-") (class "Default")
      (node (ref "R26") (pin "2") (pinfunction "2_2") (pintype "passive"))
      (node (ref "XS12") (pin "12") (pinfunction "12_12") (pintype "passive"))
    )
    (net (code "198") (name "/Water_OUT") (class "Default")
      (node (ref "R124") (pin "2") (pinfunction "2_2") (pintype "passive"))
      (node (ref "R29") (pin "2") (pinfunction "2_2") (pintype "passive"))
      (node (ref "V10") (pin "2") (pinfunction "K_2") (pintype "passive"))
      (node (ref "V2") (pin "2") (pinfunction "K_2") (pintype "passive"))
      (node (ref "V37") (pin "2") (pinfunction "K_2") (pintype "passive"))
      (node (ref "V4") (pin "2") (pinfunction "K_2") (pintype "passive"))
      (node (ref "V5") (pin "2") (pinfunction "K_2") (pintype "passive"))
      (node (ref "V6") (pin "2") (pinfunction "K_2") (pintype "passive"))
      (node (ref "V8") (pin "2") (pinfunction "K_2") (pintype "passive"))
      (node (ref "V9") (pin "2") (pinfunction "K_2") (pintype "passive"))
    )
    (net (code "199") (name "/Work_State") (class "Default")
      (node (ref "N20") (pin "7") (pinfunction "IN7_7") (pintype "passive"))
      (node (ref "U2") (pin "124") (pinfunction "PG9_124") (pintype "bidirectional"))
    )
    (net (code "200") (name "/Y1") (class "Default")
      (node (ref "R114") (pin "2") (pinfunction "2_2") (pintype "passive"))
      (node (ref "U4") (pin "10") (pinfunction "Y_10") (pintype "passive"))
      (node (ref "V32") (pin "K") (pintype "passive"))
      (node (ref "XS13") (pin "4") (pinfunction "4_4") (pintype "passive"))
    )
    (net (code "201") (name "/Yellow_Out11") (class "Default")
      (node (ref "XS12") (pin "5") (pinfunction "5_5") (pintype "passive"))
    )
    (net (code "202") (name "/Yellow_Out12") (class "Default")
      (node (ref "RL6") (pin "5") (pinfunction "5_5") (pintype "passive"))
      (node (ref "RL6") (pin "6") (pinfunction "6_6") (pintype "passive"))
      (node (ref "XS30") (pin "6") (pinfunction "6_6") (pintype "passive"))
    )
    (net (code "203") (name "/Z1") (class "Default")
      (node (ref "R114") (pin "1") (pinfunction "1_1") (pintype "passive"))
      (node (ref "U4") (pin "11") (pinfunction "Z_11") (pintype "passive"))
      (node (ref "V28") (pin "K") (pintype "passive"))
      (node (ref "XS13") (pin "3") (pinfunction "3_3") (pintype "passive"))
    )
    (net (code "204") (name "24VGND") (class "Default")
      (node (ref "C102") (pin "1") (pinfunction "1_1") (pintype "passive"))
      (node (ref "C12") (pin "2") (pinfunction "2_2") (pintype "passive"))
      (node (ref "C13") (pin "2") (pinfunction "2_2") (pintype "passive"))
      (node (ref "C16") (pin "2") (pinfunction "2_2") (pintype "passive"))
      (node (ref "C19") (pin "2") (pinfunction "2_2") (pintype "passive"))
      (node (ref "C24") (pin "1") (pinfunction "1_1") (pintype "passive"))
      (node (ref "C25") (pin "1") (pinfunction "1_1") (pintype "passive"))
      (node (ref "C27") (pin "1") (pinfunction "1_1") (pintype "passive"))
      (node (ref "C47") (pin "2") (pinfunction "2_2") (pintype "passive"))
      (node (ref "C48") (pin "2") (pinfunction "2_2") (pintype "passive"))
      (node (ref "C49") (pin "2") (pinfunction "2_2") (pintype "passive"))
      (node (ref "C50") (pin "2") (pinfunction "2_2") (pintype "passive"))
      (node (ref "C51") (pin "2") (pinfunction "2_2") (pintype "passive"))
      (node (ref "C53") (pin "2") (pinfunction "2_2") (pintype "passive"))
      (node (ref "C54") (pin "2") (pinfunction "2_2") (pintype "passive"))
      (node (ref "C57") (pin "1") (pinfunction "1_1") (pintype "passive"))
      (node (ref "C59") (pin "1") (pinfunction "1_1") (pintype "passive"))
      (node (ref "C62") (pin "1") (pinfunction "1_1") (pintype "passive"))
      (node (ref "C64") (pin "1") (pinfunction "1_1") (pintype "passive"))
      (node (ref "C66") (pin "1") (pinfunction "1_1") (pintype "passive"))
      (node (ref "C68") (pin "1") (pinfunction "1_1") (pintype "passive"))
      (node (ref "C68") (pin "2") (pinfunction "2_2") (pintype "passive"))
      (node (ref "C69") (pin "1") (pinfunction "1_1") (pintype "passive"))
      (node (ref "C69") (pin "2") (pinfunction "2_2") (pintype "passive"))
      (node (ref "C70") (pin "1") (pinfunction "1_1") (pintype "passive"))
      (node (ref "N13") (pin "2") (pinfunction "K_2") (pintype "passive"))
      (node (ref "N13") (pin "4") (pinfunction "K_4") (pintype "passive"))
      (node (ref "N13") (pin "6") (pinfunction "K_6") (pintype "passive"))
      (node (ref "N13") (pin "8") (pinfunction "K_8") (pintype "passive"))
      (node (ref "N15") (pin "2") (pinfunction "K_2") (pintype "passive"))
      (node (ref "N15") (pin "4") (pinfunction "K_4") (pintype "passive"))
      (node (ref "N15") (pin "6") (pinfunction "K_6") (pintype "passive"))
      (node (ref "N15") (pin "8") (pinfunction "K_8") (pintype "passive"))
      (node (ref "N16") (pin "3") (pinfunction "V-_3") (pintype "passive"))
      (node (ref "N2") (pin "2") (pinfunction "GND_2") (pintype "passive"))
      (node (ref "N24") (pin "3") (pinfunction "IN-_3") (pintype "passive"))
      (node (ref "N25") (pin "2") (pinfunction "K_2") (pintype "passive"))
      (node (ref "N25") (pin "4") (pinfunction "K_4") (pintype "passive"))
      (node (ref "N25") (pin "6") (pinfunction "K_6") (pintype "passive"))
      (node (ref "N4") (pin "1") (pinfunction "GND_1") (pintype "passive"))
      (node (ref "N5") (pin "2") (pinfunction "GND_2") (pintype "passive"))
      (node (ref "N7") (pin "2") (pinfunction "GND_2") (pintype "passive"))
      (node (ref "R102") (pin "2") (pinfunction "2_2") (pintype "passive"))
      (node (ref "R103") (pin "2") (pinfunction "2_2") (pintype "passive"))
      (node (ref "R118") (pin "2") (pinfunction "2_2") (pintype "passive"))
      (node (ref "R31") (pin "2") (pinfunction "2_2") (pintype "passive"))
      (node (ref "R78") (pin "2") (pinfunction "2_2") (pintype "passive"))
      (node (ref "R83") (pin "1") (pinfunction "1_1") (pintype "passive"))
      (node (ref "R85") (pin "2") (pinfunction "2_2") (pintype "passive"))
      (node (ref "R87") (pin "1") (pinfunction "1_1") (pintype "passive"))
      (node (ref "R90") (pin "2") (pinfunction "2_2") (pintype "passive"))
      (node (ref "R91") (pin "2") (pinfunction "2_2") (pintype "passive"))
      (node (ref "U5") (pin "4") (pintype "passive"))
      (node (ref "U5") (pin "7") (pintype "passive"))
      (node (ref "XS1") (pin "3") (pinfunction "3_3") (pintype "passive"))
      (node (ref "XS1") (pin "4") (pinfunction "4_4") (pintype "passive"))
      (node (ref "XS12") (pin "4") (pinfunction "4_4") (pintype "passive"))
      (node (ref "XS12") (pin "6") (pinfunction "6_6") (pintype "passive"))
      (node (ref "XS12") (pin "8") (pinfunction "8_8") (pintype "passive"))
      (node (ref "XS21") (pin "1") (pinfunction "1_1") (pintype "passive"))
      (node (ref "XS21") (pin "3") (pinfunction "3_3") (pintype "passive"))
      (node (ref "XS22") (pin "1") (pinfunction "1_1") (pintype "passive"))
      (node (ref "XS23") (pin "6") (pinfunction "6_6") (pintype "passive"))
      (node (ref "XS27") (pin "6") (pinfunction "6_6") (pintype "passive"))
      (node (ref "XS4") (pin "7") (pinfunction "7_7") (pintype "passive"))
    )
    (net (code "205") (name "DP1") (class "Default")
      (node (ref "N23") (pin "6") (pinfunction "/RE_6") (pintype "passive"))
      (node (ref "U2") (pin "103") (pinfunction "PA11_103") (pintype "bidirectional"))
    )
    (net (code "206") (name "DP2") (class "Default")
      (node (ref "N23") (pin "7") (pinfunction "RTS_7") (pintype "passive"))
      (node (ref "U2") (pin "104") (pinfunction "PA12_104") (pintype "bidirectional"))
    )
    (net (code "207") (name "GND") (class "Default")
      (node (ref "C1") (pin "1") (pinfunction "1_1") (pintype "passive"))
      (node (ref "C10") (pin "2") (pinfunction "2_2") (pintype "passive"))
      (node (ref "C107") (pin "2") (pintype "passive"))
      (node (ref "C108") (pin "2") (pintype "passive"))
      (node (ref "C11") (pin "1") (pinfunction "1_1") (pintype "passive"))
      (node (ref "C15") (pin "2") (pinfunction "2_2") (pintype "passive"))
      (node (ref "C17") (pin "2") (pinfunction "2_2") (pintype "passive"))
      (node (ref "C18") (pin "2") (pinfunction "2_2") (pintype "passive"))
      (node (ref "C22") (pin "2") (pinfunction "2_2") (pintype "passive"))
      (node (ref "C23") (pin "1") (pinfunction "1_1") (pintype "passive"))
      (node (ref "C26") (pin "1") (pinfunction "1_1") (pintype "passive"))
      (node (ref "C29") (pin "2") (pinfunction "2_2") (pintype "passive"))
      (node (ref "C30") (pin "2") (pinfunction "2_2") (pintype "passive"))
      (node (ref "C31") (pin "2") (pinfunction "2_2") (pintype "passive"))
      (node (ref "C32") (pin "2") (pinfunction "2_2") (pintype "passive"))
      (node (ref "C33") (pin "2") (pinfunction "2_2") (pintype "passive"))
      (node (ref "C34") (pin "2") (pinfunction "2_2") (pintype "passive"))
      (node (ref "C35") (pin "2") (pinfunction "2_2") (pintype "passive"))
      (node (ref "C36") (pin "2") (pinfunction "2_2") (pintype "passive"))
      (node (ref "C37") (pin "2") (pinfunction "2_2") (pintype "passive"))
      (node (ref "C38") (pin "2") (pinfunction "2_2") (pintype "passive"))
      (node (ref "C39") (pin "2") (pinfunction "2_2") (pintype "passive"))
      (node (ref "C4") (pin "2") (pinfunction "2_2") (pintype "passive"))
      (node (ref "C40") (pin "2") (pinfunction "2_2") (pintype "passive"))
      (node (ref "C41") (pin "2") (pinfunction "2_2") (pintype "passive"))
      (node (ref "C42") (pin "2") (pinfunction "2_2") (pintype "passive"))
      (node (ref "C43") (pin "1") (pinfunction "1_1") (pintype "passive"))
      (node (ref "C44") (pin "1") (pinfunction "1_1") (pintype "passive"))
      (node (ref "C45") (pin "2") (pintype "passive"))
      (node (ref "C46") (pin "1") (pinfunction "1_1") (pintype "passive"))
      (node (ref "C5") (pin "2") (pinfunction "2_2") (pintype "passive"))
      (node (ref "C52") (pin "2") (pinfunction "2_2") (pintype "passive"))
      (node (ref "C55") (pin "1") (pinfunction "1_1") (pintype "passive"))
      (node (ref "C56") (pin "2") (pinfunction "2_2") (pintype "passive"))
      (node (ref "C58") (pin "2") (pinfunction "2_2") (pintype "passive"))
      (node (ref "C6") (pin "2") (pinfunction "2_2") (pintype "passive"))
      (node (ref "C60") (pin "1") (pinfunction "1_1") (pintype "passive"))
      (node (ref "C61") (pin "1") (pinfunction "1_1") (pintype "passive"))
      (node (ref "C63") (pin "2") (pinfunction "2_2") (pintype "passive"))
      (node (ref "C65") (pin "1") (pinfunction "1_1") (pintype "passive"))
      (node (ref "C67") (pin "1") (pinfunction "1_1") (pintype "passive"))
      (node (ref "C7") (pin "2") (pinfunction "2_2") (pintype "passive"))
      (node (ref "C71") (pin "1") (pinfunction "1_1") (pintype "passive"))
      (node (ref "C72") (pin "2") (pintype "passive"))
      (node (ref "C73") (pin "2") (pintype "passive"))
      (node (ref "C74") (pin "2") (pintype "passive"))
      (node (ref "C75") (pin "2") (pintype "passive"))
      (node (ref "C76") (pin "2") (pintype "passive"))
      (node (ref "C77") (pin "2") (pintype "passive"))
      (node (ref "C78") (pin "2") (pintype "passive"))
      (node (ref "C79") (pin "2") (pintype "passive"))
      (node (ref "C8") (pin "2") (pinfunction "2_2") (pintype "passive"))
      (node (ref "C80") (pin "1") (pintype "passive"))
      (node (ref "C81") (pin "2") (pinfunction "2_2") (pintype "passive"))
      (node (ref "C82") (pin "1") (pinfunction "1_1") (pintype "passive"))
      (node (ref "C83") (pin "1") (pinfunction "1_1") (pintype "passive"))
      (node (ref "C84") (pin "2") (pinfunction "2_2") (pintype "passive"))
      (node (ref "C85") (pin "2") (pinfunction "2_2") (pintype "passive"))
      (node (ref "C86") (pin "2") (pintype "passive"))
      (node (ref "C87") (pin "2") (pintype "passive"))
      (node (ref "C88") (pin "1") (pinfunction "1_1") (pintype "passive"))
      (node (ref "C89") (pin "1") (pinfunction "1_1") (pintype "passive"))
      (node (ref "C9") (pin "2") (pinfunction "2_2") (pintype "passive"))
      (node (ref "C95") (pin "2") (pinfunction "2_2") (pintype "passive"))
      (node (ref "C96") (pin "2") (pinfunction "2_2") (pintype "passive"))
      (node (ref "C97") (pin "2") (pinfunction "2_2") (pintype "passive"))
      (node (ref "C98") (pin "2") (pintype "passive"))
      (node (ref "C99") (pin "2") (pinfunction "2_2") (pintype "passive"))
      (node (ref "D1") (pin "7") (pinfunction "GND_7") (pintype "power_in"))
      (node (ref "D2") (pin "2") (pinfunction "2_2") (pintype "passive"))
      (node (ref "D3") (pin "2") (pinfunction "2_2") (pintype "passive"))
      (node (ref "N10") (pin "3") (pinfunction "GND_3") (pintype "passive"))
      (node (ref "N10") (pin "7") (pinfunction "VSS_7") (pintype "passive"))
      (node (ref "N11") (pin "11") (pintype "passive"))
      (node (ref "N12") (pin "4") (pinfunction "GND_4") (pintype "passive"))
      (node (ref "N17") (pin "8") (pinfunction "GND_8") (pintype "passive"))
      (node (ref "N18") (pin "4") (pinfunction "AGND_4") (pintype "passive"))
      (node (ref "N18") (pin "6") (pinfunction "DGND_6") (pintype "passive"))
      (node (ref "N18") (pin "7") (pinfunction "~{LDAC}_7") (pintype "passive"))
      (node (ref "N19") (pin "4") (pinfunction "GND_4") (pintype "passive"))
      (node (ref "N2") (pin "3") (pinfunction "V-_3") (pintype "passive"))
      (node (ref "N20") (pin "8") (pinfunction "GND_8") (pintype "passive"))
      (node (ref "N21") (pin "8") (pinfunction "GND_8") (pintype "passive"))
      (node (ref "N22") (pin "2") (pinfunction "GND_2") (pintype "passive"))
      (node (ref "N23") (pin "3") (pinfunction "GND1_3") (pintype "passive"))
      (node (ref "N24") (pin "4") (pinfunction "GND_4") (pintype "passive"))
      (node (ref "N25") (pin "11") (pinfunction "E_11") (pintype "passive"))
      (node (ref "N26") (pin "8") (pinfunction "GND_8") (pintype "passive"))
      (node (ref "N5") (pin "3") (pinfunction "V-_3") (pintype "passive"))
      (node (ref "N7") (pin "4") (pinfunction "V+_4") (pintype "passive"))
      (node (ref "N8") (pin "3") (pinfunction "GND_3") (pintype "passive"))
      (node (ref "R101") (pin "1") (pinfunction "1_1") (pintype "passive"))
      (node (ref "R104") (pin "2") (pinfunction "2_2") (pintype "passive"))
      (node (ref "R107") (pin "1") (pinfunction "1_1") (pintype "passive"))
      (node (ref "R11") (pin "2") (pinfunction "2_2") (pintype "passive"))
      (node (ref "R15") (pin "1") (pinfunction "1_1") (pintype "passive"))
      (node (ref "R18") (pin "2") (pinfunction "2_2") (pintype "passive"))
      (node (ref "R21") (pin "2") (pinfunction "2_2") (pintype "passive"))
      (node (ref "R24") (pin "2") (pinfunction "2_2") (pintype "passive"))
      (node (ref "R28") (pin "2") (pinfunction "2_2") (pintype "passive"))
      (node (ref "R29") (pin "1") (pinfunction "1_1") (pintype "passive"))
      (node (ref "R30") (pin "1") (pinfunction "1_1") (pintype "passive"))
      (node (ref "R34") (pin "2") (pinfunction "2_2") (pintype "passive"))
      (node (ref "R41") (pin "2") (pinfunction "2_2") (pintype "passive"))
      (node (ref "R45") (pin "1") (pinfunction "1_1") (pintype "passive"))
      (node (ref "R47") (pin "2") (pinfunction "2_2") (pintype "passive"))
      (node (ref "R54") (pin "1") (pinfunction "1_1") (pintype "passive"))
      (node (ref "R58") (pin "2") (pinfunction "2_2") (pintype "passive"))
      (node (ref "R59") (pin "2") (pinfunction "2_2") (pintype "passive"))
      (node (ref "R6") (pin "1") (pinfunction "1_1") (pintype "passive"))
      (node (ref "R61") (pin "2") (pinfunction "2_2") (pintype "passive"))
      (node (ref "R67") (pin "2") (pinfunction "2_2") (pintype "passive"))
      (node (ref "R69") (pin "2") (pinfunction "2_2") (pintype "passive"))
      (node (ref "R71") (pin "2") (pinfunction "2_2") (pintype "passive"))
      (node (ref "R72") (pin "2") (pinfunction "2_2") (pintype "passive"))
      (node (ref "R77") (pin "1") (pinfunction "1_1") (pintype "passive"))
      (node (ref "R79") (pin "2") (pinfunction "2_2") (pintype "passive"))
      (node (ref "R80") (pin "2") (pinfunction "2_2") (pintype "passive"))
      (node (ref "R82") (pin "2") (pinfunction "2_2") (pintype "passive"))
      (node (ref "R83") (pin "2") (pinfunction "2_2") (pintype "passive"))
      (node (ref "R84") (pin "1") (pinfunction "1_1") (pintype "passive"))
      (node (ref "R88") (pin "2") (pinfunction "2_2") (pintype "passive"))
      (node (ref "R97") (pin "2") (pinfunction "2_2") (pintype "passive"))
      (node (ref "R98") (pin "1") (pinfunction "1_1") (pintype "passive"))
      (node (ref "R99") (pin "2") (pinfunction "2_2") (pintype "passive"))
      (node (ref "S1") (pin "1") (pinfunction "COMMON_1") (pintype "passive"))
      (node (ref "U1") (pin "1") (pinfunction "GND_1") (pintype "passive"))
      (node (ref "U2") (pin "107") (pinfunction "VSS_2_107") (pintype "power_in"))
      (node (ref "U2") (pin "120") (pinfunction "VSS_10_120") (pintype "power_in"))
      (node (ref "U2") (pin "130") (pinfunction "VSS_11_130") (pintype "power_in"))
      (node (ref "U2") (pin "143") (pinfunction "VSS_3_143") (pintype "power_in"))
      (node (ref "U2") (pin "16") (pinfunction "VSS_5_16") (pintype "power_in"))
      (node (ref "U2") (pin "30") (pinfunction "VSSA_30") (pintype "power_in"))
      (node (ref "U2") (pin "31") (pinfunction "VREF-_31") (pintype "power_in"))
      (node (ref "U2") (pin "38") (pinfunction "VSS_4_38") (pintype "power_in"))
      (node (ref "U2") (pin "51") (pinfunction "VSS_6_51") (pintype "power_in"))
      (node (ref "U2") (pin "61") (pinfunction "VSS_7_61") (pintype "power_in"))
      (node (ref "U2") (pin "71") (pinfunction "VSS_1_71") (pintype "power_in"))
      (node (ref "U2") (pin "83") (pinfunction "VSS_8_83") (pintype "power_in"))
      (node (ref "U2") (pin "94") (pinfunction "VSS_9_94") (pintype "power_in"))
      (node (ref "U3") (pin "2") (pintype "passive"))
      (node (ref "U3") (pin "4") (pintype "passive"))
      (node (ref "U4") (pin "2") (pinfunction "GND1_2") (pintype "passive"))
      (node (ref "U4") (pin "5") (pinfunction "GND1_5") (pintype "passive"))
      (node (ref "U4") (pin "8") (pinfunction "GND1_8") (pintype "passive"))
      (node (ref "V13") (pin "1") (pinfunction "A_1") (pintype "passive"))
      (node (ref "V15") (pin "1") (pinfunction "A_1") (pintype "passive"))
      (node (ref "V17") (pin "1") (pinfunction "A_1") (pintype "passive"))
      (node (ref "V18") (pin "1") (pinfunction "A_1") (pintype "passive"))
      (node (ref "V33") (pin "C") (pinfunction "C_C") (pintype "passive"))
      (node (ref "XS14") (pin "8") (pinfunction "8_8") (pintype "passive"))
      (node (ref "XS17") (pin "10") (pinfunction "10_10") (pintype "passive"))
      (node (ref "XS17") (pin "11") (pinfunction "11_11") (pintype "passive"))
      (node (ref "XS17") (pin "12") (pinfunction "12_12") (pintype "passive"))
      (node (ref "XS17") (pin "9") (pinfunction "9_9") (pintype "passive"))
      (node (ref "XS6") (pin "8") (pinfunction "8_8") (pintype "passive"))
    )
    (net (code "208") (name "GND#") (class "Default")
      (node (ref "C106") (pin "2") (pinfunction "2_2") (pintype "passive"))
      (node (ref "C2") (pin "2") (pinfunction "2_2") (pintype "passive"))
      (node (ref "C28") (pin "2") (pinfunction "2_2") (pintype "passive"))
      (node (ref "N14") (pin "11") (pintype "passive"))
      (node (ref "N3") (pin "11") (pintype "passive"))
      (node (ref "N9") (pin "11") (pintype "passive"))
      (node (ref "R1") (pin "2") (pinfunction "2_2") (pintype "passive"))
      (node (ref "R105") (pin "2") (pinfunction "2_2") (pintype "passive"))
      (node (ref "R12") (pin "2") (pinfunction "2_2") (pintype "passive"))
      (node (ref "R131") (pin "2") (pinfunction "2_2") (pintype "passive"))
      (node (ref "R134") (pin "2") (pinfunction "2_2") (pintype "passive"))
      (node (ref "R20") (pin "2") (pinfunction "2_2") (pintype "passive"))
      (node (ref "R33") (pin "2") (pinfunction "2_2") (pintype "passive"))
      (node (ref "R46") (pin "2") (pinfunction "2_2") (pintype "passive"))
      (node (ref "R56") (pin "2") (pinfunction "2_2") (pintype "passive"))
      (node (ref "V11") (pin "1") (pinfunction "A_1") (pintype "passive"))
      (node (ref "V12") (pin "1") (pinfunction "A_1") (pintype "passive"))
      (node (ref "V14") (pin "1") (pinfunction "A_1") (pintype "passive"))
      (node (ref "V16") (pin "1") (pinfunction "A_1") (pintype "passive"))
      (node (ref "V3") (pin "1") (pinfunction "A_1") (pintype "passive"))
      (node (ref "V34") (pin "1") (pinfunction "A_1") (pintype "passive"))
      (node (ref "V35") (pin "1") (pinfunction "A_1") (pintype "passive"))
      (node (ref "V36") (pin "1") (pinfunction "A_1") (pintype "passive"))
      (node (ref "V7") (pin "1") (pinfunction "A_1") (pintype "passive"))
    )
    (net (code "209") (name "GNDISO1") (class "Default")
      (node (ref "C101") (pin "2") (pinfunction "2_2") (pintype "passive"))
      (node (ref "C90") (pin "1") (pintype "passive"))
      (node (ref "C91") (pin "1") (pinfunction "1_1") (pintype "passive"))
      (node (ref "C92") (pin "2") (pinfunction "2_2") (pintype "passive"))
      (node (ref "C94") (pin "2") (pinfunction "2_2") (pintype "passive"))
      (node (ref "N22") (pin "3") (pinfunction "V-_3") (pintype "passive"))
      (node (ref "R115") (pin "2") (pinfunction "2_2") (pintype "passive"))
      (node (ref "R123") (pin "1") (pinfunction "1_1") (pintype "passive"))
      (node (ref "U4") (pin "9") (pinfunction "GND2_9") (pintype "passive"))
      (node (ref "V27") (pin "A") (pintype "passive"))
      (node (ref "V28") (pin "A") (pintype "passive"))
      (node (ref "V29") (pin "A") (pintype "passive"))
      (node (ref "V32") (pin "A") (pintype "passive"))
      (node (ref "XS13") (pin "5") (pinfunction "5_5") (pintype "passive"))
      (node (ref "XS15") (pin "3") (pinfunction "3_3") (pintype "passive"))
    )
    (net (code "210") (name "LD_GND1") (class "Default")
      (node (ref "C20") (pin "2") (pinfunction "2_2") (pintype "passive"))
      (node (ref "N6") (pin "2") (pinfunction "K_2") (pintype "passive"))
      (node (ref "XS18") (pin "5") (pinfunction "5_5") (pintype "passive"))
    )
    (net (code "211") (name "LD_GND1#") (class "Default")
      (node (ref "R17") (pin "1") (pinfunction "1_1") (pintype "passive"))
      (node (ref "R27") (pin "1") (pinfunction "1_1") (pintype "passive"))
      (node (ref "R8") (pin "1") (pinfunction "1_1") (pintype "passive"))
    )
    (net (code "212") (name "LD_GND2") (class "Default")
      (node (ref "C21") (pin "1") (pinfunction "1_1") (pintype "passive"))
      (node (ref "N6") (pin "4") (pinfunction "K_4") (pintype "passive"))
      (node (ref "XS19") (pin "5") (pinfunction "5_5") (pintype "passive"))
    )
    (net (code "213") (name "LD_GND2#") (class "Default")
      (node (ref "R40") (pin "1") (pinfunction "1_1") (pintype "passive"))
      (node (ref "R51") (pin "1") (pinfunction "1_1") (pintype "passive"))
      (node (ref "R64") (pin "1") (pinfunction "1_1") (pintype "passive"))
    )
    (net (code "214") (name "LD_GND3") (class "Default")
      (node (ref "C3") (pin "1") (pinfunction "1_1") (pintype "passive"))
      (node (ref "N6") (pin "6") (pinfunction "K_6") (pintype "passive"))
      (node (ref "R42") (pin "1") (pinfunction "1_1") (pintype "passive"))
      (node (ref "R53") (pin "1") (pinfunction "1_1") (pintype "passive"))
      (node (ref "R66") (pin "1") (pinfunction "1_1") (pintype "passive"))
      (node (ref "XS20") (pin "5") (pinfunction "5_5") (pintype "passive"))
    )
    (net (code "215") (name "LD_GND4") (class "Default")
      (node (ref "C105") (pin "1") (pinfunction "1_1") (pintype "passive"))
      (node (ref "N6") (pin "8") (pinfunction "K_8") (pintype "passive"))
      (node (ref "XS16") (pin "5") (pinfunction "5_5") (pintype "passive"))
    )
    (net (code "216") (name "LD_GND4#") (class "Default")
      (node (ref "R128") (pin "1") (pinfunction "1_1") (pintype "passive"))
      (node (ref "R133") (pin "1") (pinfunction "1_1") (pintype "passive"))
      (node (ref "R138") (pin "1") (pinfunction "1_1") (pintype "passive"))
    )
    (net (code "217") (name "Net-(C6-Pad1)") (class "Default")
      (node (ref "C6") (pin "1") (pinfunction "1_1") (pintype "passive"))
      (node (ref "D1") (pin "1") (pintype "input"))
      (node (ref "R2") (pin "1") (pinfunction "1_1") (pintype "passive"))
      (node (ref "R6") (pin "2") (pinfunction "2_2") (pintype "passive"))
    )
    (net (code "218") (name "Net-(C18-Pad1)") (class "Default")
      (node (ref "C18") (pin "1") (pinfunction "1_1") (pintype "passive"))
      (node (ref "D1") (pin "3") (pintype "input"))
      (node (ref "R13") (pin "1") (pinfunction "1_1") (pintype "passive"))
      (node (ref "R15") (pin "2") (pinfunction "2_2") (pintype "passive"))
    )
    (net (code "219") (name "Net-(C22-Pad1)") (class "Default")
      (node (ref "C22") (pin "1") (pinfunction "1_1") (pintype "passive"))
      (node (ref "D1") (pin "5") (pintype "input"))
      (node (ref "R23") (pin "1") (pinfunction "1_1") (pintype "passive"))
      (node (ref "R30") (pin "2") (pinfunction "2_2") (pintype "passive"))
    )
    (net (code "220") (name "Net-(C25-Pad2)") (class "Default")
      (node (ref "C25") (pin "2") (pinfunction "2_2") (pintype "passive"))
      (node (ref "N25") (pin "5") (pinfunction "A_5") (pintype "passive"))
      (node (ref "R26") (pin "1") (pinfunction "1_1") (pintype "passive"))
      (node (ref "R31") (pin "1") (pinfunction "1_1") (pintype "passive"))
    )
    (net (code "221") (name "Net-(C56-Pad1)") (class "Default")
      (node (ref "C56") (pin "1") (pinfunction "1_1") (pintype "passive"))
      (node (ref "R71") (pin "1") (pinfunction "1_1") (pintype "passive"))
      (node (ref "R73") (pin "2") (pinfunction "2_2") (pintype "passive"))
      (node (ref "R77") (pin "2") (pinfunction "2_2") (pintype "passive"))
      (node (ref "U3") (pin "3") (pintype "passive"))
    )
    (net (code "222") (name "Net-(C57-Pad2)") (class "Default")
      (node (ref "C57") (pin "2") (pinfunction "2_2") (pintype "passive"))
      (node (ref "N15") (pin "1") (pinfunction "A_1") (pintype "passive"))
      (node (ref "R74") (pin "1") (pinfunction "1_1") (pintype "passive"))
      (node (ref "R78") (pin "1") (pinfunction "1_1") (pintype "passive"))
    )
    (net (code "223") (name "Net-(C59-Pad2)") (class "Default")
      (node (ref "C59") (pin "2") (pinfunction "2_2") (pintype "passive"))
      (node (ref "N15") (pin "3") (pinfunction "A_3") (pintype "passive"))
      (node (ref "R81") (pin "1") (pinfunction "1_1") (pintype "passive"))
      (node (ref "R85") (pin "1") (pinfunction "1_1") (pintype "passive"))
    )
    (net (code "224") (name "Net-(C61-Pad2)") (class "Default")
      (node (ref "C61") (pin "2") (pinfunction "2_2") (pintype "passive"))
      (node (ref "R75") (pin "1") (pinfunction "1_1") (pintype "passive"))
      (node (ref "R84") (pin "2") (pinfunction "2_2") (pintype "passive"))
      (node (ref "U3") (pin "1") (pintype "passive"))
    )
    (net (code "225") (name "Net-(C64-Pad2)") (class "Default")
      (node (ref "C64") (pin "2") (pinfunction "2_2") (pintype "passive"))
      (node (ref "N15") (pin "5") (pinfunction "A_5") (pintype "passive"))
      (node (ref "R89") (pin "1") (pinfunction "1_1") (pintype "passive"))
      (node (ref "R91") (pin "1") (pinfunction "1_1") (pintype "passive"))
    )
    (net (code "226") (name "Net-(C70-Pad2)") (class "Default")
      (node (ref "C70") (pin "2") (pinfunction "2_2") (pintype "passive"))
      (node (ref "N15") (pin "7") (pinfunction "A_7") (pintype "passive"))
      (node (ref "R100") (pin "1") (pinfunction "1_1") (pintype "passive"))
      (node (ref "R102") (pin "1") (pinfunction "1_1") (pintype "passive"))
    )
    (net (code "227") (name "Net-(C101-Pad1)") (class "Default")
      (node (ref "C101") (pin "1") (pinfunction "1_1") (pintype "passive"))
      (node (ref "C93") (pin "2") (pinfunction "2_2") (pintype "passive"))
    )
    (net (code "228") (name "Net-(C103-Pad2)") (class "Default")
      (node (ref "C103") (pin "2") (pinfunction "2_2") (pintype "passive"))
      (node (ref "C104") (pin "2") (pinfunction "2_2") (pintype "passive"))
      (node (ref "N23") (pin "11") (pinfunction "GND2_11") (pintype "passive"))
      (node (ref "N23") (pin "14") (pinfunction "GND2_14") (pintype "passive"))
      (node (ref "N23") (pin "15") (pinfunction "GND2_15") (pintype "passive"))
      (node (ref "N23") (pin "9") (pinfunction "GND2_9") (pintype "passive"))
      (node (ref "R117") (pin "2") (pinfunction "2_2") (pintype "passive"))
      (node (ref "V30") (pin "A") (pintype "passive"))
      (node (ref "V31") (pin "A") (pintype "passive"))
    )
    (net (code "229") (name "Net-(D2-Pad1)") (class "Default")
      (node (ref "D2") (pin "1") (pinfunction "1_1") (pintype "passive"))
      (node (ref "R35") (pin "1") (pinfunction "1_1") (pintype "passive"))
    )
    (net (code "230") (name "Net-(D3-Pad1)") (class "Default")
      (node (ref "D3") (pin "1") (pinfunction "1_1") (pintype "passive"))
      (node (ref "R108") (pin "2") (pinfunction "2_2") (pintype "passive"))
    )
    (net (code "231") (name "Net-(D4-Pad1)") (class "Default")
      (node (ref "D4") (pin "1") (pinfunction "1_1") (pintype "passive"))
      (node (ref "R119") (pin "1") (pinfunction "1_1") (pintype "passive"))
    )
    (net (code "232") (name "Net-(D5-Pad1)") (class "Default")
      (node (ref "D5") (pin "1") (pinfunction "1_1") (pintype "passive"))
      (node (ref "R120") (pin "1") (pinfunction "1_1") (pintype "passive"))
    )
    (net (code "233") (name "Net-(D6-Pad1)") (class "Default")
      (node (ref "D6") (pin "1") (pinfunction "1_1") (pintype "passive"))
      (node (ref "R121") (pin "1") (pinfunction "1_1") (pintype "passive"))
    )
    (net (code "234") (name "Net-(D7-Pad1)") (class "Default")
      (node (ref "D7") (pin "1") (pinfunction "1_1") (pintype "passive"))
      (node (ref "R122") (pin "1") (pinfunction "1_1") (pintype "passive"))
    )
    (net (code "235") (name "Net-(L1-Pad1)") (class "Default")
      (node (ref "L1") (pin "1") (pinfunction "1_1") (pintype "passive"))
      (node (ref "U1") (pin "2") (pinfunction "Vout_2") (pintype "passive"))
      (node (ref "U1") (pin "4") (pinfunction "Vout_4") (pintype "passive"))
    )
    (net (code "236") (name "Net-(N3-Pad1)") (class "Default")
      (node (ref "N3") (pin "1") (pintype "passive"))
      (node (ref "R10") (pin "2") (pinfunction "2_2") (pintype "passive"))
      (node (ref "R5") (pin "2") (pinfunction "2_2") (pintype "passive"))
    )
    (net (code "237") (name "Net-(N3-Pad2)") (class "Default")
      (node (ref "N3") (pin "2") (pintype "passive"))
      (node (ref "R10") (pin "1") (pinfunction "1_1") (pintype "passive"))
      (node (ref "R8") (pin "2") (pinfunction "2_2") (pintype "passive"))
    )
    (net (code "238") (name "Net-(N3-Pad3)") (class "Default")
      (node (ref "N3") (pin "3") (pintype "passive"))
      (node (ref "R1") (pin "1") (pinfunction "1_1") (pintype "passive"))
      (node (ref "R7") (pin "2") (pinfunction "2_2") (pintype "passive"))
    )
    (net (code "239") (name "Net-(N3-Pad5)") (class "Default")
      (node (ref "N3") (pin "5") (pintype "passive"))
      (node (ref "R12") (pin "1") (pinfunction "1_1") (pintype "passive"))
      (node (ref "R14") (pin "2") (pinfunction "2_2") (pintype "passive"))
    )
    (net (code "240") (name "Net-(N3-Pad6)") (class "Default")
      (node (ref "N3") (pin "6") (pintype "passive"))
      (node (ref "R17") (pin "2") (pinfunction "2_2") (pintype "passive"))
      (node (ref "R19") (pin "1") (pinfunction "1_1") (pintype "passive"))
    )
    (net (code "241") (name "Net-(N3-Pad7)") (class "Default")
      (node (ref "N3") (pin "7") (pintype "passive"))
      (node (ref "R16") (pin "2") (pinfunction "2_2") (pintype "passive"))
      (node (ref "R19") (pin "2") (pinfunction "2_2") (pintype "passive"))
    )
    (net (code "242") (name "Net-(N3-Pad8)") (class "Default")
      (node (ref "N3") (pin "8") (pintype "passive"))
      (node (ref "R25") (pin "2") (pinfunction "2_2") (pintype "passive"))
      (node (ref "R32") (pin "2") (pinfunction "2_2") (pintype "passive"))
    )
    (net (code "243") (name "Net-(N3-Pad9)") (class "Default")
      (node (ref "N3") (pin "9") (pintype "passive"))
      (node (ref "R27") (pin "2") (pinfunction "2_2") (pintype "passive"))
      (node (ref "R32") (pin "1") (pinfunction "1_1") (pintype "passive"))
    )
    (net (code "244") (name "Net-(N3-Pad10)") (class "Default")
      (node (ref "N3") (pin "10") (pintype "passive"))
      (node (ref "R20") (pin "1") (pinfunction "1_1") (pintype "passive"))
      (node (ref "R22") (pin "2") (pinfunction "2_2") (pintype "passive"))
    )
    (net (code "245") (name "Net-(N9-Pad1)") (class "Default")
      (node (ref "N9") (pin "1") (pintype "passive"))
      (node (ref "R36") (pin "2") (pinfunction "2_2") (pintype "passive"))
      (node (ref "R43") (pin "2") (pinfunction "2_2") (pintype "passive"))
    )
    (net (code "246") (name "Net-(N9-Pad2)") (class "Default")
      (node (ref "N9") (pin "2") (pintype "passive"))
      (node (ref "R40") (pin "2") (pinfunction "2_2") (pintype "passive"))
      (node (ref "R43") (pin "1") (pinfunction "1_1") (pintype "passive"))
    )
    (net (code "247") (name "Net-(N9-Pad3)") (class "Default")
      (node (ref "N9") (pin "3") (pintype "passive"))
      (node (ref "R33") (pin "1") (pinfunction "1_1") (pintype "passive"))
      (node (ref "R37") (pin "2") (pinfunction "2_2") (pintype "passive"))
    )
    (net (code "248") (name "Net-(N9-Pad5)") (class "Default")
      (node (ref "N9") (pin "5") (pintype "passive"))
      (node (ref "R46") (pin "1") (pinfunction "1_1") (pintype "passive"))
      (node (ref "R48") (pin "2") (pinfunction "2_2") (pintype "passive"))
    )
    (net (code "249") (name "Net-(N9-Pad6)") (class "Default")
      (node (ref "N9") (pin "6") (pintype "passive"))
      (node (ref "R51") (pin "2") (pinfunction "2_2") (pintype "passive"))
      (node (ref "R55") (pin "1") (pinfunction "1_1") (pintype "passive"))
    )
    (net (code "250") (name "Net-(N9-Pad7)") (class "Default")
      (node (ref "N9") (pin "7") (pintype "passive"))
      (node (ref "R49") (pin "2") (pinfunction "2_2") (pintype "passive"))
      (node (ref "R55") (pin "2") (pinfunction "2_2") (pintype "passive"))
    )
    (net (code "251") (name "Net-(N9-Pad8)") (class "Default")
      (node (ref "N9") (pin "8") (pintype "passive"))
      (node (ref "R62") (pin "2") (pinfunction "2_2") (pintype "passive"))
      (node (ref "R68") (pin "2") (pinfunction "2_2") (pintype "passive"))
    )
    (net (code "252") (name "Net-(N9-Pad9)") (class "Default")
      (node (ref "N9") (pin "9") (pintype "passive"))
      (node (ref "R64") (pin "2") (pinfunction "2_2") (pintype "passive"))
      (node (ref "R68") (pin "1") (pinfunction "1_1") (pintype "passive"))
    )
    (net (code "253") (name "Net-(N9-Pad10)") (class "Default")
      (node (ref "N9") (pin "10") (pintype "passive"))
      (node (ref "R56") (pin "1") (pinfunction "1_1") (pintype "passive"))
      (node (ref "R60") (pin "2") (pinfunction "2_2") (pintype "passive"))
    )
    (net (code "254") (name "Net-(N10-D)") (class "Default")
      (node (ref "N10") (pin "1") (pinfunction "D_1") (pintype "passive"))
      (node (ref "N8") (pin "2") (pinfunction "Ain_2") (pintype "passive"))
      (node (ref "N8") (pin "4") (pinfunction "Bin_4") (pintype "passive"))
      (node (ref "R41") (pin "1") (pinfunction "1_1") (pintype "passive"))
    )
    (net (code "255") (name "Net-(N11-Pad1)") (class "Default")
      (node (ref "N11") (pin "1") (pintype "passive"))
      (node (ref "R38") (pin "2") (pinfunction "2_2") (pintype "passive"))
      (node (ref "R44") (pin "2") (pinfunction "2_2") (pintype "passive"))
    )
    (net (code "256") (name "Net-(N11-Pad2)") (class "Default")
      (node (ref "N11") (pin "2") (pintype "passive"))
      (node (ref "R42") (pin "2") (pinfunction "2_2") (pintype "passive"))
      (node (ref "R44") (pin "1") (pinfunction "1_1") (pintype "passive"))
    )
    (net (code "257") (name "Net-(N11-Pad3)") (class "Default")
      (node (ref "N11") (pin "3") (pintype "passive"))
      (node (ref "R34") (pin "1") (pinfunction "1_1") (pintype "passive"))
      (node (ref "R39") (pin "2") (pinfunction "2_2") (pintype "passive"))
    )
    (net (code "258") (name "Net-(N11-Pad5)") (class "Default")
      (node (ref "N11") (pin "5") (pintype "passive"))
      (node (ref "R47") (pin "1") (pinfunction "1_1") (pintype "passive"))
      (node (ref "R50") (pin "2") (pinfunction "2_2") (pintype "passive"))
    )
    (net (code "259") (name "Net-(N11-Pad6)") (class "Default")
      (node (ref "N11") (pin "6") (pintype "passive"))
      (node (ref "R53") (pin "2") (pinfunction "2_2") (pintype "passive"))
      (node (ref "R57") (pin "1") (pinfunction "1_1") (pintype "passive"))
    )
    (net (code "260") (name "Net-(N11-Pad7)") (class "Default")
      (node (ref "N11") (pin "7") (pintype "passive"))
      (node (ref "R52") (pin "2") (pinfunction "2_2") (pintype "passive"))
      (node (ref "R57") (pin "2") (pinfunction "2_2") (pintype "passive"))
    )
    (net (code "261") (name "Net-(N11-Pad8)") (class "Default")
      (node (ref "N11") (pin "8") (pintype "passive"))
      (node (ref "R65") (pin "2") (pinfunction "2_2") (pintype "passive"))
      (node (ref "R70") (pin "2") (pinfunction "2_2") (pintype "passive"))
    )
    (net (code "262") (name "Net-(N11-Pad9)") (class "Default")
      (node (ref "N11") (pin "9") (pintype "passive"))
      (node (ref "R66") (pin "2") (pinfunction "2_2") (pintype "passive"))
      (node (ref "R70") (pin "1") (pinfunction "1_1") (pintype "passive"))
    )
    (net (code "263") (name "Net-(N11-Pad10)") (class "Default")
      (node (ref "N11") (pin "10") (pintype "passive"))
      (node (ref "R59") (pin "1") (pinfunction "1_1") (pintype "passive"))
      (node (ref "R63") (pin "2") (pinfunction "2_2") (pintype "passive"))
    )
    (net (code "264") (name "Net-(N14-Pad1)") (class "Default")
      (node (ref "N14") (pin "1") (pintype "passive"))
      (node (ref "R129") (pin "2") (pinfunction "2_2") (pintype "passive"))
      (node (ref "R130") (pin "2") (pinfunction "2_2") (pintype "passive"))
    )
    (net (code "265") (name "Net-(N14-Pad2)") (class "Default")
      (node (ref "N14") (pin "2") (pintype "passive"))
      (node (ref "R128") (pin "2") (pinfunction "2_2") (pintype "passive"))
      (node (ref "R129") (pin "1") (pinfunction "1_1") (pintype "passive"))
    )
    (net (code "266") (name "Net-(N14-Pad3)") (class "Default")
      (node (ref "N14") (pin "3") (pintype "passive"))
      (node (ref "R105") (pin "1") (pinfunction "1_1") (pintype "passive"))
      (node (ref "R141") (pin "2") (pinfunction "2_2") (pintype "passive"))
    )
    (net (code "267") (name "Net-(N14-Pad5)") (class "Default")
      (node (ref "N14") (pin "5") (pintype "passive"))
      (node (ref "R131") (pin "1") (pinfunction "1_1") (pintype "passive"))
      (node (ref "R132") (pin "2") (pinfunction "2_2") (pintype "passive"))
    )
    (net (code "268") (name "Net-(N14-Pad6)") (class "Default")
      (node (ref "N14") (pin "6") (pintype "passive"))
      (node (ref "R133") (pin "2") (pinfunction "2_2") (pintype "passive"))
      (node (ref "R135") (pin "1") (pinfunction "1_1") (pintype "passive"))
    )
    (net (code "269") (name "Net-(N14-Pad7)") (class "Default")
      (node (ref "N14") (pin "7") (pintype "passive"))
      (node (ref "R135") (pin "2") (pinfunction "2_2") (pintype "passive"))
      (node (ref "R136") (pin "2") (pinfunction "2_2") (pintype "passive"))
    )
    (net (code "270") (name "Net-(N14-Pad8)") (class "Default")
      (node (ref "N14") (pin "8") (pintype "passive"))
      (node (ref "R139") (pin "2") (pinfunction "2_2") (pintype "passive"))
      (node (ref "R140") (pin "2") (pinfunction "2_2") (pintype "passive"))
    )
    (net (code "271") (name "Net-(N14-Pad9)") (class "Default")
      (node (ref "N14") (pin "9") (pintype "passive"))
      (node (ref "R138") (pin "2") (pinfunction "2_2") (pintype "passive"))
      (node (ref "R139") (pin "1") (pinfunction "1_1") (pintype "passive"))
    )
    (net (code "272") (name "Net-(N14-Pad10)") (class "Default")
      (node (ref "N14") (pin "10") (pintype "passive"))
      (node (ref "R134") (pin "1") (pinfunction "1_1") (pintype "passive"))
      (node (ref "R137") (pin "2") (pinfunction "2_2") (pintype "passive"))
    )
    (net (code "273") (name "Net-(N16-V+)") (class "Default")
      (node (ref "C66") (pin "2") (pinfunction "2_2") (pintype "passive"))
      (node (ref "N16") (pin "2") (pinfunction "V+_2") (pintype "passive"))
      (node (ref "R86") (pin "1") (pinfunction "1_1") (pintype "passive"))
      (node (ref "R90") (pin "1") (pinfunction "1_1") (pintype "passive"))
    )
    (net (code "274") (name "Net-(N18-REFAB)") (class "Default")
      (node (ref "C86") (pin "1") (pintype "passive"))
      (node (ref "C87") (pin "1") (pintype "passive"))
      (node (ref "C88") (pin "2") (pinfunction "2_2") (pintype "passive"))
      (node (ref "N18") (pin "12") (pinfunction "REFCD_12") (pintype "passive"))
      (node (ref "N18") (pin "5") (pinfunction "REFAB_5") (pintype "passive"))
      (node (ref "N19") (pin "6") (pinfunction "OUT_6") (pintype "passive"))
    )
    (net (code "275") (name "Net-(N21-IN7)") (class "Default")
      (node (ref "N21") (pin "7") (pinfunction "IN7_7") (pintype "passive"))
      (node (ref "R125") (pin "2") (pinfunction "2_2") (pintype "passive"))
      (node (ref "V33") (pin "E") (pinfunction "E_E") (pintype "passive"))
    )
    (net (code "276") (name "Net-(N21-OUT1)") (class "Default")
      (node (ref "N21") (pin "16") (pinfunction "OUT1_16") (pintype "passive"))
      (node (ref "VR2") (pin "1") (pinfunction "1_1") (pintype "passive"))
    )
    (net (code "277") (name "Net-(N21-OUT2)") (class "Default")
      (node (ref "N21") (pin "15") (pinfunction "OUT2_15") (pintype "passive"))
      (node (ref "VR2") (pin "2") (pinfunction "2_2") (pintype "passive"))
    )
    (net (code "278") (name "Net-(N21-OUT3)") (class "Default")
      (node (ref "N21") (pin "14") (pinfunction "OUT3_14") (pintype "passive"))
      (node (ref "VR2") (pin "3") (pinfunction "3_3") (pintype "passive"))
    )
    (net (code "279") (name "Net-(N21-OUT4)") (class "Default")
      (node (ref "N21") (pin "13") (pinfunction "OUT4_13") (pintype "passive"))
      (node (ref "VR2") (pin "4") (pinfunction "4_4") (pintype "passive"))
    )
    (net (code "280") (name "Net-(N21-OUT5)") (class "Default")
      (node (ref "N21") (pin "12") (pinfunction "OUT5_12") (pintype "passive"))
      (node (ref "VR4") (pin "1") (pinfunction "1_1") (pintype "passive"))
    )
    (net (code "281") (name "Net-(N21-OUT6)") (class "Default")
      (node (ref "N21") (pin "11") (pinfunction "OUT6_11") (pintype "passive"))
      (node (ref "VR4") (pin "2") (pinfunction "2_2") (pintype "passive"))
    )
    (net (code "282") (name "Net-(N21-OUT7)") (class "Default")
      (node (ref "N21") (pin "10") (pinfunction "OUT7_10") (pintype "passive"))
      (node (ref "VR4") (pin "3") (pinfunction "3_3") (pintype "passive"))
      (node (ref "VR4") (pin "4") (pinfunction "4_4") (pintype "passive"))
    )
    (net (code "283") (name "Net-(N24-VO)") (class "Default")
      (node (ref "N24") (pin "5") (pinfunction "VO_5") (pintype "passive"))
      (node (ref "R116") (pin "2") (pinfunction "2_2") (pintype "passive"))
    )
    (net (code "284") (name "Net-(N26-OUT4)") (class "Default")
      (node (ref "N26") (pin "13") (pinfunction "OUT4_13") (pintype "passive"))
      (node (ref "VR5") (pin "1") (pinfunction "1_1") (pintype "passive"))
    )
    (net (code "285") (name "Net-(N26-OUT5)") (class "Default")
      (node (ref "N26") (pin "12") (pinfunction "OUT5_12") (pintype "passive"))
      (node (ref "VR5") (pin "2") (pinfunction "2_2") (pintype "passive"))
    )
    (net (code "286") (name "Net-(P4-Pad1)") (class "Default")
      (node (ref "P4") (pin "1") (pinfunction "1_1") (pintype "passive"))
      (node (ref "P4") (pin "3") (pinfunction "3_3") (pintype "passive"))
      (node (ref "P4") (pin "5") (pinfunction "5_5") (pintype "passive"))
      (node (ref "P4") (pin "7") (pinfunction "7_7") (pintype "passive"))
    )
    (net (code "287") (name "Net-(R87-Pad2)") (class "Default")
      (node (ref "R87") (pin "2") (pinfunction "2_2") (pintype "passive"))
      (node (ref "R92") (pin "2") (pinfunction "2_2") (pintype "passive"))
      (node (ref "U5") (pin "5") (pintype "passive"))
    )
    (net (code "288") (name "Net-(R103-Pad1)") (class "Default")
      (node (ref "R103") (pin "1") (pinfunction "1_1") (pintype "passive"))
      (node (ref "R98") (pin "2") (pinfunction "2_2") (pintype "passive"))
      (node (ref "U5") (pin "6") (pintype "passive"))
    )
    (net (code "289") (name "Net-(R124-Pad1)") (class "Default")
      (node (ref "R124") (pin "1") (pinfunction "1_1") (pintype "passive"))
      (node (ref "V33") (pin "B") (pinfunction "B_B") (pintype "input"))
    )
    (net (code "290") (name "Net-(V3-K)") (class "Default")
      (node (ref "R5") (pin "1") (pinfunction "1_1") (pintype "passive"))
      (node (ref "V3") (pin "2") (pinfunction "K_2") (pintype "passive"))
    )
    (net (code "291") (name "Net-(V18-K)") (class "Default")
      (node (ref "C58") (pin "1") (pinfunction "1_1") (pintype "passive"))
      (node (ref "R75") (pin "2") (pinfunction "2_2") (pintype "passive"))
      (node (ref "R76") (pin "1") (pinfunction "1_1") (pintype "passive"))
      (node (ref "R80") (pin "1") (pinfunction "1_1") (pintype "passive"))
      (node (ref "V18") (pin "2") (pinfunction "K_2") (pintype "passive"))
    )
    (net (code "292") (name "Net-(XS23-Pad1)") (class "Default")
      (node (ref "XS23") (pin "1") (pinfunction "1_1") (pintype "passive"))
      (node (ref "XS27") (pin "1") (pinfunction "1_1") (pintype "passive"))
    )
    (net (code "293") (name "Net-(XS23-Pad2)") (class "Default")
      (node (ref "XS23") (pin "2") (pinfunction "2_2") (pintype "passive"))
      (node (ref "XS27") (pin "2") (pinfunction "2_2") (pintype "passive"))
    )
    (net (code "294") (name "RS485_A") (class "Default")
      (node (ref "C100") (pin "1") (pinfunction "1_1") (pintype "passive"))
      (node (ref "C104") (pin "1") (pinfunction "1_1") (pintype "passive"))
      (node (ref "N23") (pin "12") (pinfunction "A_12") (pintype "passive"))
      (node (ref "R110") (pin "2") (pinfunction "2_2") (pintype "passive"))
      (node (ref "R112") (pin "1") (pintype "passive"))
      (node (ref "V30") (pin "K") (pintype "passive"))
      (node (ref "XS15") (pin "1") (pinfunction "1_1") (pintype "passive"))
    )
    (net (code "295") (name "RS485_B") (class "Default")
      (node (ref "C100") (pin "2") (pinfunction "2_2") (pintype "passive"))
      (node (ref "C103") (pin "1") (pinfunction "1_1") (pintype "passive"))
      (node (ref "N23") (pin "13") (pinfunction "B_13") (pintype "passive"))
      (node (ref "R112") (pin "2") (pintype "passive"))
      (node (ref "R117") (pin "1") (pinfunction "1_1") (pintype "passive"))
      (node (ref "V31") (pin "K") (pintype "passive"))
      (node (ref "XS15") (pin "2") (pinfunction "2_2") (pintype "passive"))
    )
    (net (code "296") (name "RXD2") (class "Default")
      (node (ref "D4") (pin "2") (pinfunction "2_2") (pintype "passive"))
      (node (ref "U2") (pin "37") (pinfunction "PA3_37") (pintype "bidirectional"))
      (node (ref "U4") (pin "3") (pinfunction "RxD_3") (pintype "passive"))
    )
    (net (code "297") (name "TXD2") (class "Default")
      (node (ref "D7") (pin "2") (pinfunction "2_2") (pintype "passive"))
      (node (ref "U2") (pin "36") (pinfunction "PA2_36") (pintype "bidirectional"))
      (node (ref "U4") (pin "6") (pinfunction "TxD_6") (pintype "passive"))
    )
    (net (code "298") (name "VDD") (class "Default")
      (node (ref "C10") (pin "1") (pinfunction "1_1") (pintype "passive"))
      (node (ref "C30") (pin "1") (pinfunction "1_1") (pintype "passive"))
      (node (ref "C31") (pin "1") (pinfunction "1_1") (pintype "passive"))
      (node (ref "C32") (pin "1") (pinfunction "1_1") (pintype "passive"))
      (node (ref "C33") (pin "1") (pinfunction "1_1") (pintype "passive"))
      (node (ref "C34") (pin "1") (pinfunction "1_1") (pintype "passive"))
      (node (ref "C35") (pin "1") (pinfunction "1_1") (pintype "passive"))
      (node (ref "C36") (pin "1") (pinfunction "1_1") (pintype "passive"))
      (node (ref "C37") (pin "1") (pinfunction "1_1") (pintype "passive"))
      (node (ref "C38") (pin "1") (pinfunction "1_1") (pintype "passive"))
      (node (ref "C39") (pin "1") (pinfunction "1_1") (pintype "passive"))
      (node (ref "C4") (pin "1") (pinfunction "1_1") (pintype "passive"))
      (node (ref "C40") (pin "1") (pinfunction "1_1") (pintype "passive"))
      (node (ref "C41") (pin "1") (pinfunction "1_1") (pintype "passive"))
      (node (ref "C96") (pin "1") (pinfunction "1_1") (pintype "passive"))
      (node (ref "C98") (pin "1") (pintype "passive"))
      (node (ref "L1") (pin "2") (pinfunction "2_2") (pintype "passive"))
      (node (ref "N23") (pin "4") (pinfunction "VDD1_4") (pintype "passive"))
      (node (ref "R106") (pin "2") (pinfunction "2_2") (pintype "passive"))
      (node (ref "R108") (pin "1") (pinfunction "1_1") (pintype "passive"))
      (node (ref "R119") (pin "2") (pinfunction "2_2") (pintype "passive"))
      (node (ref "R120") (pin "2") (pinfunction "2_2") (pintype "passive"))
      (node (ref "R121") (pin "2") (pinfunction "2_2") (pintype "passive"))
      (node (ref "R122") (pin "2") (pinfunction "2_2") (pintype "passive"))
      (node (ref "R93") (pin "1") (pinfunction "1_1") (pintype "passive"))
      (node (ref "R94") (pin "1") (pinfunction "1_1") (pintype "passive"))
      (node (ref "R95") (pin "1") (pinfunction "1_1") (pintype "passive"))
      (node (ref "R96") (pin "1") (pinfunction "1_1") (pintype "passive"))
      (node (ref "U2") (pin "108") (pinfunction "VDD_2_108") (pintype "power_in"))
      (node (ref "U2") (pin "121") (pinfunction "VDD_10_121") (pintype "power_in"))
      (node (ref "U2") (pin "131") (pinfunction "VDD_11_131") (pintype "power_in"))
      (node (ref "U2") (pin "144") (pinfunction "VDD_3_144") (pintype "power_in"))
      (node (ref "U2") (pin "17") (pinfunction "VDD_5_17") (pintype "power_in"))
      (node (ref "U2") (pin "33") (pinfunction "VDDA_33") (pintype "power_in"))
      (node (ref "U2") (pin "39") (pinfunction "VDD_4_39") (pintype "power_in"))
      (node (ref "U2") (pin "52") (pinfunction "VDD_6_52") (pintype "power_in"))
      (node (ref "U2") (pin "62") (pinfunction "VDD_7_62") (pintype "power_in"))
      (node (ref "U2") (pin "72") (pinfunction "VDD_1_72") (pintype "power_in"))
      (node (ref "U2") (pin "84") (pinfunction "VDD_8_84") (pintype "power_in"))
      (node (ref "U2") (pin "95") (pinfunction "VDD_9_95") (pintype "power_in"))
      (node (ref "U4") (pin "1") (pinfunction "VDD1_1") (pintype "passive"))
      (node (ref "XS6") (pin "1") (pinfunction "1_1") (pintype "passive"))
      (node (ref "XS6") (pin "2") (pinfunction "2_2") (pintype "passive"))
    )
    (net (code "299") (name "unconnected-(N8-NC-Pad1)") (class "Default")
      (node (ref "N8") (pin "1") (pinfunction "NC_1") (pintype "passive"))
    )
    (net (code "300") (name "unconnected-(N8-NC-Pad8)") (class "Default")
      (node (ref "N8") (pin "8") (pinfunction "NC_8") (pintype "passive"))
    )
    (net (code "301") (name "unconnected-(N12-I.C-Pad1)") (class "Default")
      (node (ref "N12") (pin "1") (pinfunction "I.C_1") (pintype "passive"))
    )
    (net (code "302") (name "unconnected-(N12-I.C-Pad7)") (class "Default")
      (node (ref "N12") (pin "7") (pinfunction "I.C_7") (pintype "passive"))
    )
    (net (code "303") (name "unconnected-(N12-I.C-Pad8)") (class "Default")
      (node (ref "N12") (pin "8") (pinfunction "I.C_8") (pintype "passive"))
    )
    (net (code "304") (name "unconnected-(N12-NC-Pad3)") (class "Default")
      (node (ref "N12") (pin "3") (pinfunction "NC_3") (pintype "passive"))
    )
    (net (code "305") (name "unconnected-(N12-TRIM-Pad5)") (class "Default")
      (node (ref "N12") (pin "5") (pinfunction "TRIM_5") (pintype "passive"))
    )
    (net (code "306") (name "unconnected-(N16-NC-Pad1)") (class "Default")
      (node (ref "N16") (pin "1") (pinfunction "NC_1") (pintype "passive"))
    )
    (net (code "307") (name "unconnected-(N16-NC-Pad4)") (class "Default")
      (node (ref "N16") (pin "4") (pinfunction "NC_4") (pintype "passive"))
    )
    (net (code "308") (name "unconnected-(N16-VE-Pad7)") (class "Default")
      (node (ref "N16") (pin "7") (pinfunction "VE_7") (pintype "passive"))
    )
    (net (code "309") (name "unconnected-(N18-SDO-Pad11)") (class "Default")
      (node (ref "N18") (pin "11") (pinfunction "SDO_11") (pintype "passive"))
    )
    (net (code "310") (name "unconnected-(N19-I.C-Pad1)") (class "Default")
      (node (ref "N19") (pin "1") (pinfunction "I.C_1") (pintype "passive"))
    )
    (net (code "311") (name "unconnected-(N19-I.C-Pad7)") (class "Default")
      (node (ref "N19") (pin "7") (pinfunction "I.C_7") (pintype "passive"))
    )
    (net (code "312") (name "unconnected-(N19-I.C-Pad8)") (class "Default")
      (node (ref "N19") (pin "8") (pinfunction "I.C_8") (pintype "passive"))
    )
    (net (code "313") (name "unconnected-(N19-NC-Pad3)") (class "Default")
      (node (ref "N19") (pin "3") (pinfunction "NC_3") (pintype "passive"))
    )
    (net (code "314") (name "unconnected-(N19-TRIM-Pad5)") (class "Default")
      (node (ref "N19") (pin "5") (pinfunction "TRIM_5") (pintype "passive"))
    )
    (net (code "315") (name "unconnected-(N23-D1-Pad1)") (class "Default")
      (node (ref "N23") (pin "1") (pinfunction "D1_1") (pintype "passive"))
    )
    (net (code "316") (name "unconnected-(N23-D2-Pad2)") (class "Default")
      (node (ref "N23") (pin "2") (pinfunction "D2_2") (pintype "passive"))
    )
    (net (code "317") (name "unconnected-(N23-DE_OUT-Pad10)") (class "Default")
      (node (ref "N23") (pin "10") (pinfunction "DE_OUT_10") (pintype "passive"))
    )
    (net (code "318") (name "unconnected-(N24-NC-Pad2)") (class "Default")
      (node (ref "N24") (pin "2") (pinfunction "NC_2") (pintype "passive"))
    )
    (net (code "319") (name "unconnected-(N25-A-Pad7)") (class "Default")
      (node (ref "N25") (pin "7") (pinfunction "A_7") (pintype "passive"))
    )
    (net (code "320") (name "unconnected-(N25-C-Pad10)") (class "Default")
      (node (ref "N25") (pin "10") (pinfunction "C_10") (pintype "passive"))
    )
    (net (code "321") (name "unconnected-(N25-E-Pad9)") (class "Default")
      (node (ref "N25") (pin "9") (pinfunction "E_9") (pintype "passive"))
    )
    (net (code "322") (name "unconnected-(N25-K-Pad8)") (class "Default")
      (node (ref "N25") (pin "8") (pinfunction "K_8") (pintype "passive"))
    )
    (net (code "323") (name "unconnected-(N26-IN3-Pad3)") (class "Default")
      (node (ref "N26") (pin "3") (pinfunction "IN3_3") (pintype "passive"))
    )
    (net (code "324") (name "unconnected-(N26-IN6-Pad6)") (class "Default")
      (node (ref "N26") (pin "6") (pinfunction "IN6_6") (pintype "passive"))
    )
    (net (code "325") (name "unconnected-(N26-IN7-Pad7)") (class "Default")
      (node (ref "N26") (pin "7") (pinfunction "IN7_7") (pintype "passive"))
    )
    (net (code "326") (name "unconnected-(N26-OUT3-Pad14)") (class "Default")
      (node (ref "N26") (pin "14") (pinfunction "OUT3_14") (pintype "passive"))
    )
    (net (code "327") (name "unconnected-(N26-OUT6-Pad11)") (class "Default")
      (node (ref "N26") (pin "11") (pinfunction "OUT6_11") (pintype "passive"))
    )
    (net (code "328") (name "unconnected-(N26-OUT7-Pad10)") (class "Default")
      (node (ref "N26") (pin "10") (pinfunction "OUT7_10") (pintype "passive"))
    )
    (net (code "329") (name "unconnected-(R2-Pad2)") (class "Default")
      (node (ref "R2") (pin "2") (pinfunction "2_2") (pintype "passive"))
    )
    (net (code "330") (name "unconnected-(R23-Pad2)") (class "Default")
      (node (ref "R23") (pin "2") (pinfunction "2_2") (pintype "passive"))
    )
    (net (code "331") (name "unconnected-(R115-Pad1)") (class "Default")
      (node (ref "R115") (pin "1") (pinfunction "1_1") (pintype "passive"))
    )
    (net (code "332") (name "unconnected-(R137-Pad1)") (class "Default")
      (node (ref "R137") (pin "1") (pinfunction "1_1") (pintype "passive"))
    )
    (net (code "333") (name "unconnected-(RL1-Pad3)") (class "Default")
      (node (ref "RL1") (pin "3") (pinfunction "3_3") (pintype "passive"))
    )
    (net (code "334") (name "unconnected-(U2A-PA1-Pad35)") (class "Default")
      (node (ref "U2") (pin "35") (pinfunction "PA1_35") (pintype "bidirectional"))
    )
    (net (code "335") (name "unconnected-(U2A-PA7-Pad43)") (class "Default")
      (node (ref "U2") (pin "43") (pinfunction "PA7_43") (pintype "bidirectional"))
    )
    (net (code "336") (name "unconnected-(U2A-PA8-Pad100)") (class "Default")
      (node (ref "U2") (pin "100") (pinfunction "PA8_100") (pintype "bidirectional"))
    )
    (net (code "337") (name "unconnected-(U2A-PB5-Pad135)") (class "Default")
      (node (ref "U2") (pin "135") (pinfunction "PB5_135") (pintype "bidirectional"))
    )
    (net (code "338") (name "unconnected-(U2A-PB10-Pad69)") (class "Default")
      (node (ref "U2") (pin "69") (pinfunction "PB10_69") (pintype "bidirectional"))
    )
    (net (code "339") (name "unconnected-(U2A-PB11-Pad70)") (class "Default")
      (node (ref "U2") (pin "70") (pinfunction "PB11_70") (pintype "bidirectional"))
    )
    (net (code "340") (name "unconnected-(U2A-PB15-Pad76)") (class "Default")
      (node (ref "U2") (pin "76") (pinfunction "PB15_76") (pintype "bidirectional"))
    )
    (net (code "341") (name "unconnected-(U2A-PC6-Pad96)") (class "Default")
      (node (ref "U2") (pin "96") (pinfunction "PC6_96") (pintype "bidirectional"))
    )
    (net (code "342") (name "unconnected-(U2A-PC7-Pad97)") (class "Default")
      (node (ref "U2") (pin "97") (pinfunction "PC7_97") (pintype "bidirectional"))
    )
    (net (code "343") (name "unconnected-(U2A-PC8-Pad98)") (class "Default")
      (node (ref "U2") (pin "98") (pinfunction "PC8_98") (pintype "bidirectional"))
    )
    (net (code "344") (name "unconnected-(U2A-PC9-Pad99)") (class "Default")
      (node (ref "U2") (pin "99") (pinfunction "PC9_99") (pintype "bidirectional"))
    )
    (net (code "345") (name "unconnected-(U2A-PC11-Pad112)") (class "Default")
      (node (ref "U2") (pin "112") (pinfunction "PC11_112") (pintype "bidirectional"))
    )
    (net (code "346") (name "unconnected-(U2A-PC12-Pad113)") (class "Default")
      (node (ref "U2") (pin "113") (pinfunction "PC12_113") (pintype "bidirectional"))
    )
    (net (code "347") (name "unconnected-(U2A-PC13-TAMPER-RTC-Pad7)") (class "Default")
      (node (ref "U2") (pin "7") (pinfunction "PC13-TAMPER-RTC_7") (pintype "bidirectional"))
    )
    (net (code "348") (name "unconnected-(U2A-PC14-OSC32_IN-Pad8)") (class "Default")
      (node (ref "U2") (pin "8") (pinfunction "PC14-OSC32_IN_8") (pintype "bidirectional"))
    )
    (net (code "349") (name "unconnected-(U2A-PC15-OSC32_OUT-Pad9)") (class "Default")
      (node (ref "U2") (pin "9") (pinfunction "PC15-OSC32_OUT_9") (pintype "bidirectional"))
    )
    (net (code "350") (name "unconnected-(U2A-PD9-Pad78)") (class "Default")
      (node (ref "U2") (pin "78") (pinfunction "PD9_78") (pintype "bidirectional"))
    )
    (net (code "351") (name "unconnected-(U2A-PD10-Pad79)") (class "Default")
      (node (ref "U2") (pin "79") (pinfunction "PD10_79") (pintype "bidirectional"))
    )
    (net (code "352") (name "unconnected-(U2A-PD11-Pad80)") (class "Default")
      (node (ref "U2") (pin "80") (pinfunction "PD11_80") (pintype "bidirectional"))
    )
    (net (code "353") (name "unconnected-(U2A-PD12-Pad81)") (class "Default")
      (node (ref "U2") (pin "81") (pinfunction "PD12_81") (pintype "bidirectional"))
    )
    (net (code "354") (name "unconnected-(U2A-PD13-Pad82)") (class "Default")
      (node (ref "U2") (pin "82") (pinfunction "PD13_82") (pintype "bidirectional"))
    )
    (net (code "355") (name "unconnected-(U2A-PD14-Pad85)") (class "Default")
      (node (ref "U2") (pin "85") (pinfunction "PD14_85") (pintype "bidirectional"))
    )
    (net (code "356") (name "unconnected-(U2A-PE7-Pad58)") (class "Default")
      (node (ref "U2") (pin "58") (pinfunction "PE7_58") (pintype "bidirectional"))
    )
    (net (code "357") (name "unconnected-(U2A-PE8-Pad59)") (class "Default")
      (node (ref "U2") (pin "59") (pinfunction "PE8_59") (pintype "bidirectional"))
    )
    (net (code "358") (name "unconnected-(U2A-PE9-Pad60)") (class "Default")
      (node (ref "U2") (pin "60") (pinfunction "PE9_60") (pintype "bidirectional"))
    )
    (net (code "359") (name "unconnected-(U2A-PE10-Pad63)") (class "Default")
      (node (ref "U2") (pin "63") (pinfunction "PE10_63") (pintype "bidirectional"))
    )
    (net (code "360") (name "unconnected-(U2A-PE11-Pad64)") (class "Default")
      (node (ref "U2") (pin "64") (pinfunction "PE11_64") (pintype "bidirectional"))
    )
    (net (code "361") (name "unconnected-(U2A-PE12-Pad65)") (class "Default")
      (node (ref "U2") (pin "65") (pinfunction "PE12_65") (pintype "bidirectional"))
    )
    (net (code "362") (name "unconnected-(U2A-PE13-Pad66)") (class "Default")
      (node (ref "U2") (pin "66") (pinfunction "PE13_66") (pintype "bidirectional"))
    )
    (net (code "363") (name "unconnected-(U2A-PE14-Pad67)") (class "Default")
      (node (ref "U2") (pin "67") (pinfunction "PE14_67") (pintype "bidirectional"))
    )
    (net (code "364") (name "unconnected-(U2A-PE15-Pad68)") (class "Default")
      (node (ref "U2") (pin "68") (pinfunction "PE15_68") (pintype "bidirectional"))
    )
    (net (code "365") (name "unconnected-(U2A-PF11-Pad49)") (class "Default")
      (node (ref "U2") (pin "49") (pinfunction "PF11_49") (pintype "bidirectional"))
    )
    (net (code "366") (name "unconnected-(U2A-PG0-Pad56)") (class "Default")
      (node (ref "U2") (pin "56") (pinfunction "PG0_56") (pintype "bidirectional"))
    )
    (net (code "367") (name "unconnected-(U2A-PG1-Pad57)") (class "Default")
      (node (ref "U2") (pin "57") (pinfunction "PG1_57") (pintype "bidirectional"))
    )
    (net (code "368") (name "unconnected-(U2A-PG2-Pad87)") (class "Default")
      (node (ref "U2") (pin "87") (pinfunction "PG2_87") (pintype "bidirectional"))
    )
    (net (code "369") (name "unconnected-(U2B-NC-Pad106)") (class "Default")
      (node (ref "U2") (pin "106") (pinfunction "NC_106") (pintype "passive"))
    )
    (net (code "370") (name "unconnected-(U2B-VBAT-Pad6)") (class "Default")
      (node (ref "U2") (pin "6") (pinfunction "VBAT_6") (pintype "power_in"))
    )
    (net (code "371") (name "unconnected-(U4-GND2-Pad15)") (class "Default")
      (node (ref "U4") (pin "15") (pinfunction "GND2_15") (pintype "passive"))
    )
    (net (code "372") (name "unconnected-(U4-NC-Pad4)") (class "Default")
      (node (ref "U4") (pin "4") (pinfunction "NC_4") (pintype "passive"))
    )
    (net (code "373") (name "unconnected-(U4-NC-Pad7)") (class "Default")
      (node (ref "U4") (pin "7") (pinfunction "NC_7") (pintype "passive"))
    )
    (net (code "374") (name "unconnected-(U4-NC-Pad12)") (class "Default")
      (node (ref "U4") (pin "12") (pinfunction "NC_12") (pintype "passive"))
    )
    (net (code "375") (name "unconnected-(U5-Pad1)") (class "Default")
      (node (ref "U5") (pin "1") (pintype "passive"))
    )
    (net (code "376") (name "unconnected-(U5-Pad2)") (class "Default")
      (node (ref "U5") (pin "2") (pintype "passive"))
    )
    (net (code "377") (name "unconnected-(U5-Pad3)") (class "Default")
      (node (ref "U5") (pin "3") (pintype "passive"))
    )
    (net (code "378") (name "unconnected-(VR5-Pad3)") (class "Default")
      (node (ref "VR5") (pin "3") (pinfunction "3_3") (pintype "passive"))
    )
    (net (code "379") (name "unconnected-(VR5-Pad4)") (class "Default")
      (node (ref "VR5") (pin "4") (pinfunction "4_4") (pintype "passive"))
    )
    (net (code "380") (name "unconnected-(VR5-Pad5)") (class "Default")
      (node (ref "VR5") (pin "5") (pinfunction "5_5") (pintype "passive"))
    )
    (net (code "381") (name "unconnected-(VR5-Pad6)") (class "Default")
      (node (ref "VR5") (pin "6") (pinfunction "6_6") (pintype "passive"))
    )
    (net (code "382") (name "unconnected-(XS6-Pad6)") (class "Default")
      (node (ref "XS6") (pin "6") (pinfunction "6_6") (pintype "passive"))
    )
    (net (code "383") (name "unconnected-(XS29-Pad1)") (class "Default")
      (node (ref "XS29") (pin "1") (pinfunction "1_1") (pintype "passive"))
    )
    (net (code "384") (name "unconnected-(XS29-Pad3)") (class "Default")
      (node (ref "XS29") (pin "3") (pinfunction "3_3") (pintype "passive"))
    )
    (net (code "385") (name "unconnected-(XS29-Pad4)") (class "Default")
      (node (ref "XS29") (pin "4") (pinfunction "4_4") (pintype "passive"))
    )
    (net (code "386") (name "unconnected-(XS29-Pad5)") (class "Default")
      (node (ref "XS29") (pin "5") (pinfunction "5_5") (pintype "passive"))
    )
    (net (code "387") (name "unconnected-(XS29-Pad6)") (class "Default")
      (node (ref "XS29") (pin "6") (pinfunction "6_6") (pintype "passive"))
    )
    (net (code "388") (name "unconnected-(XS29-Pad7)") (class "Default")
      (node (ref "XS29") (pin "7") (pinfunction "7_7") (pintype "passive"))
    )
  )
)
